# Private_CPU_DDR4.net
KiCad netlist of a schematic drawn in Altium Designer
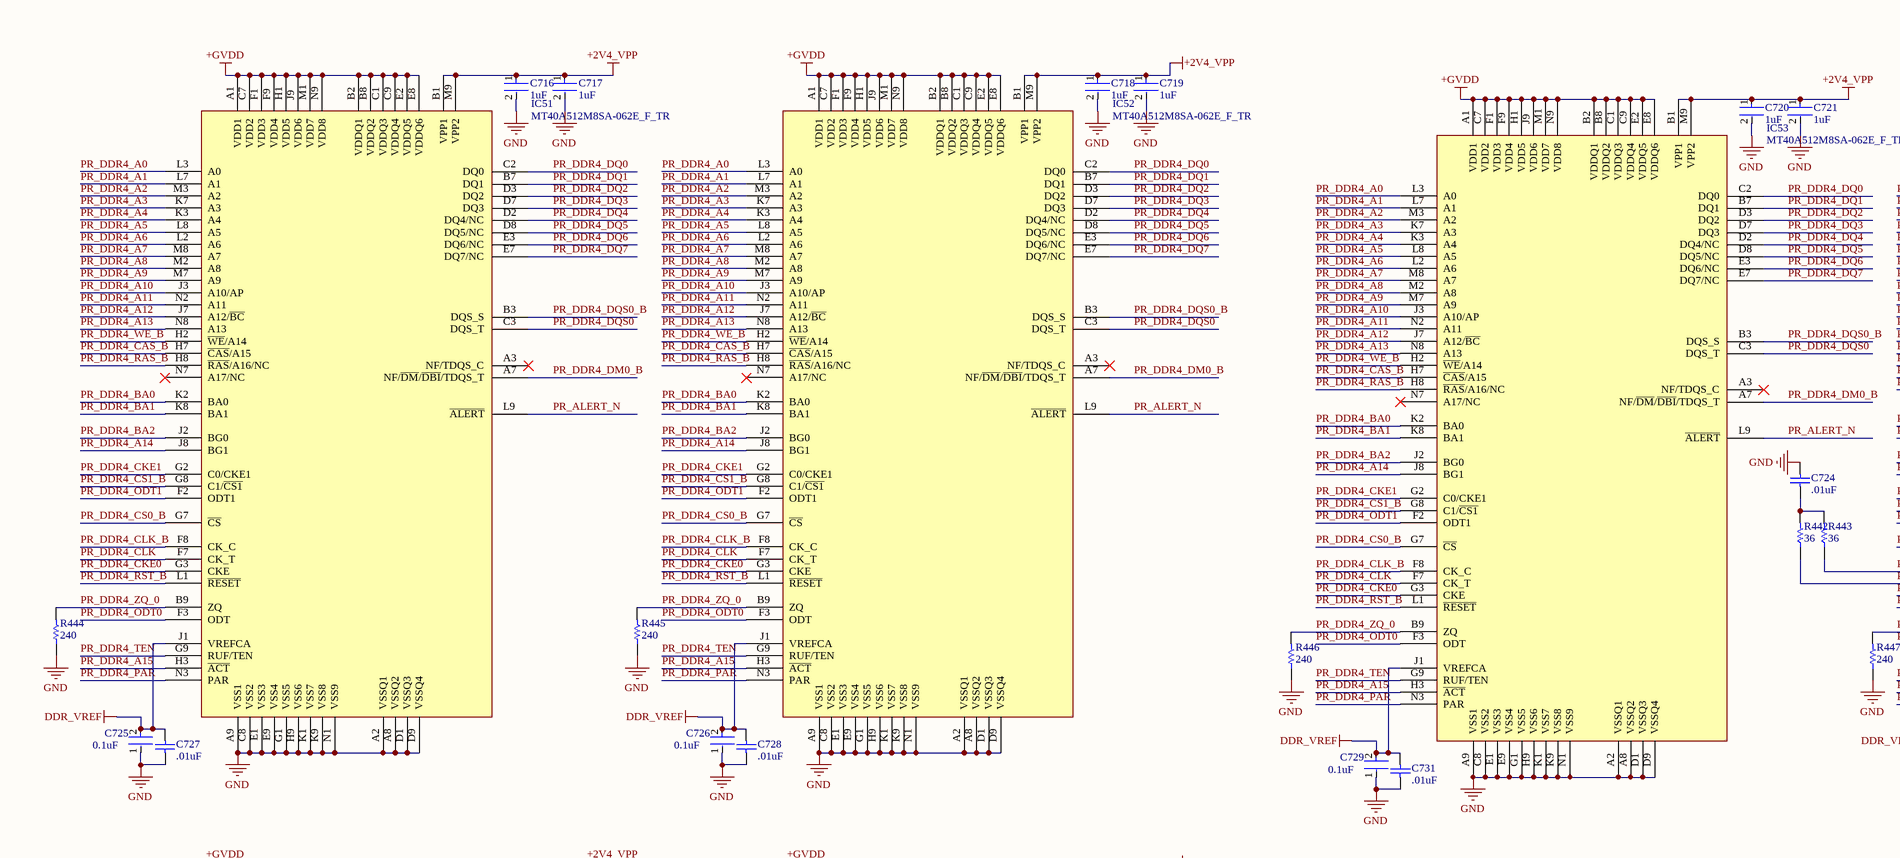
[diagram p0: Private_CPU_DDR4.SchDoc, top left]
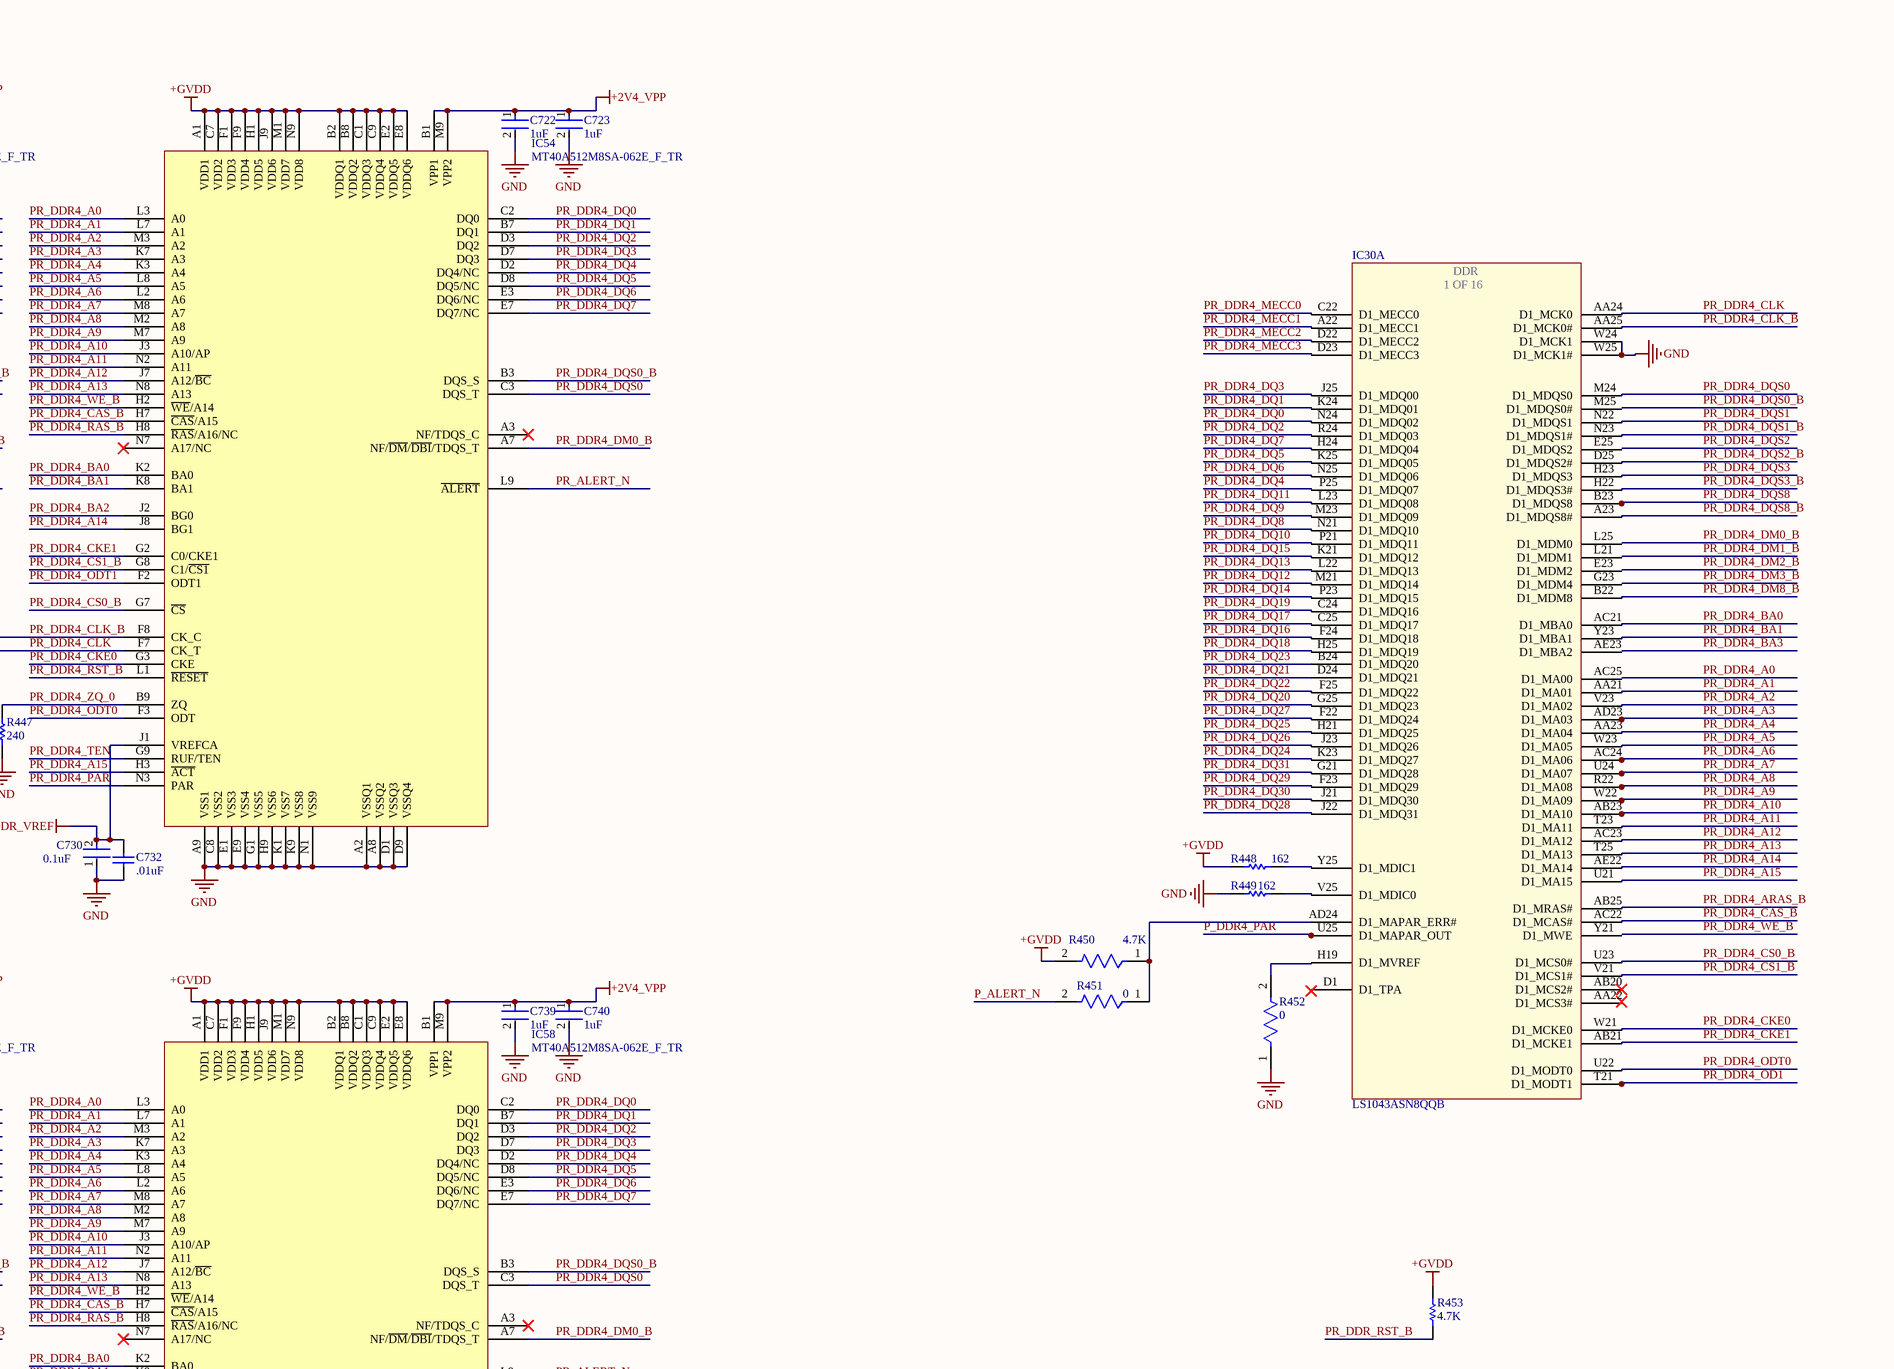
[diagram p1: Private_CPU_DDR4.SchDoc, top right]
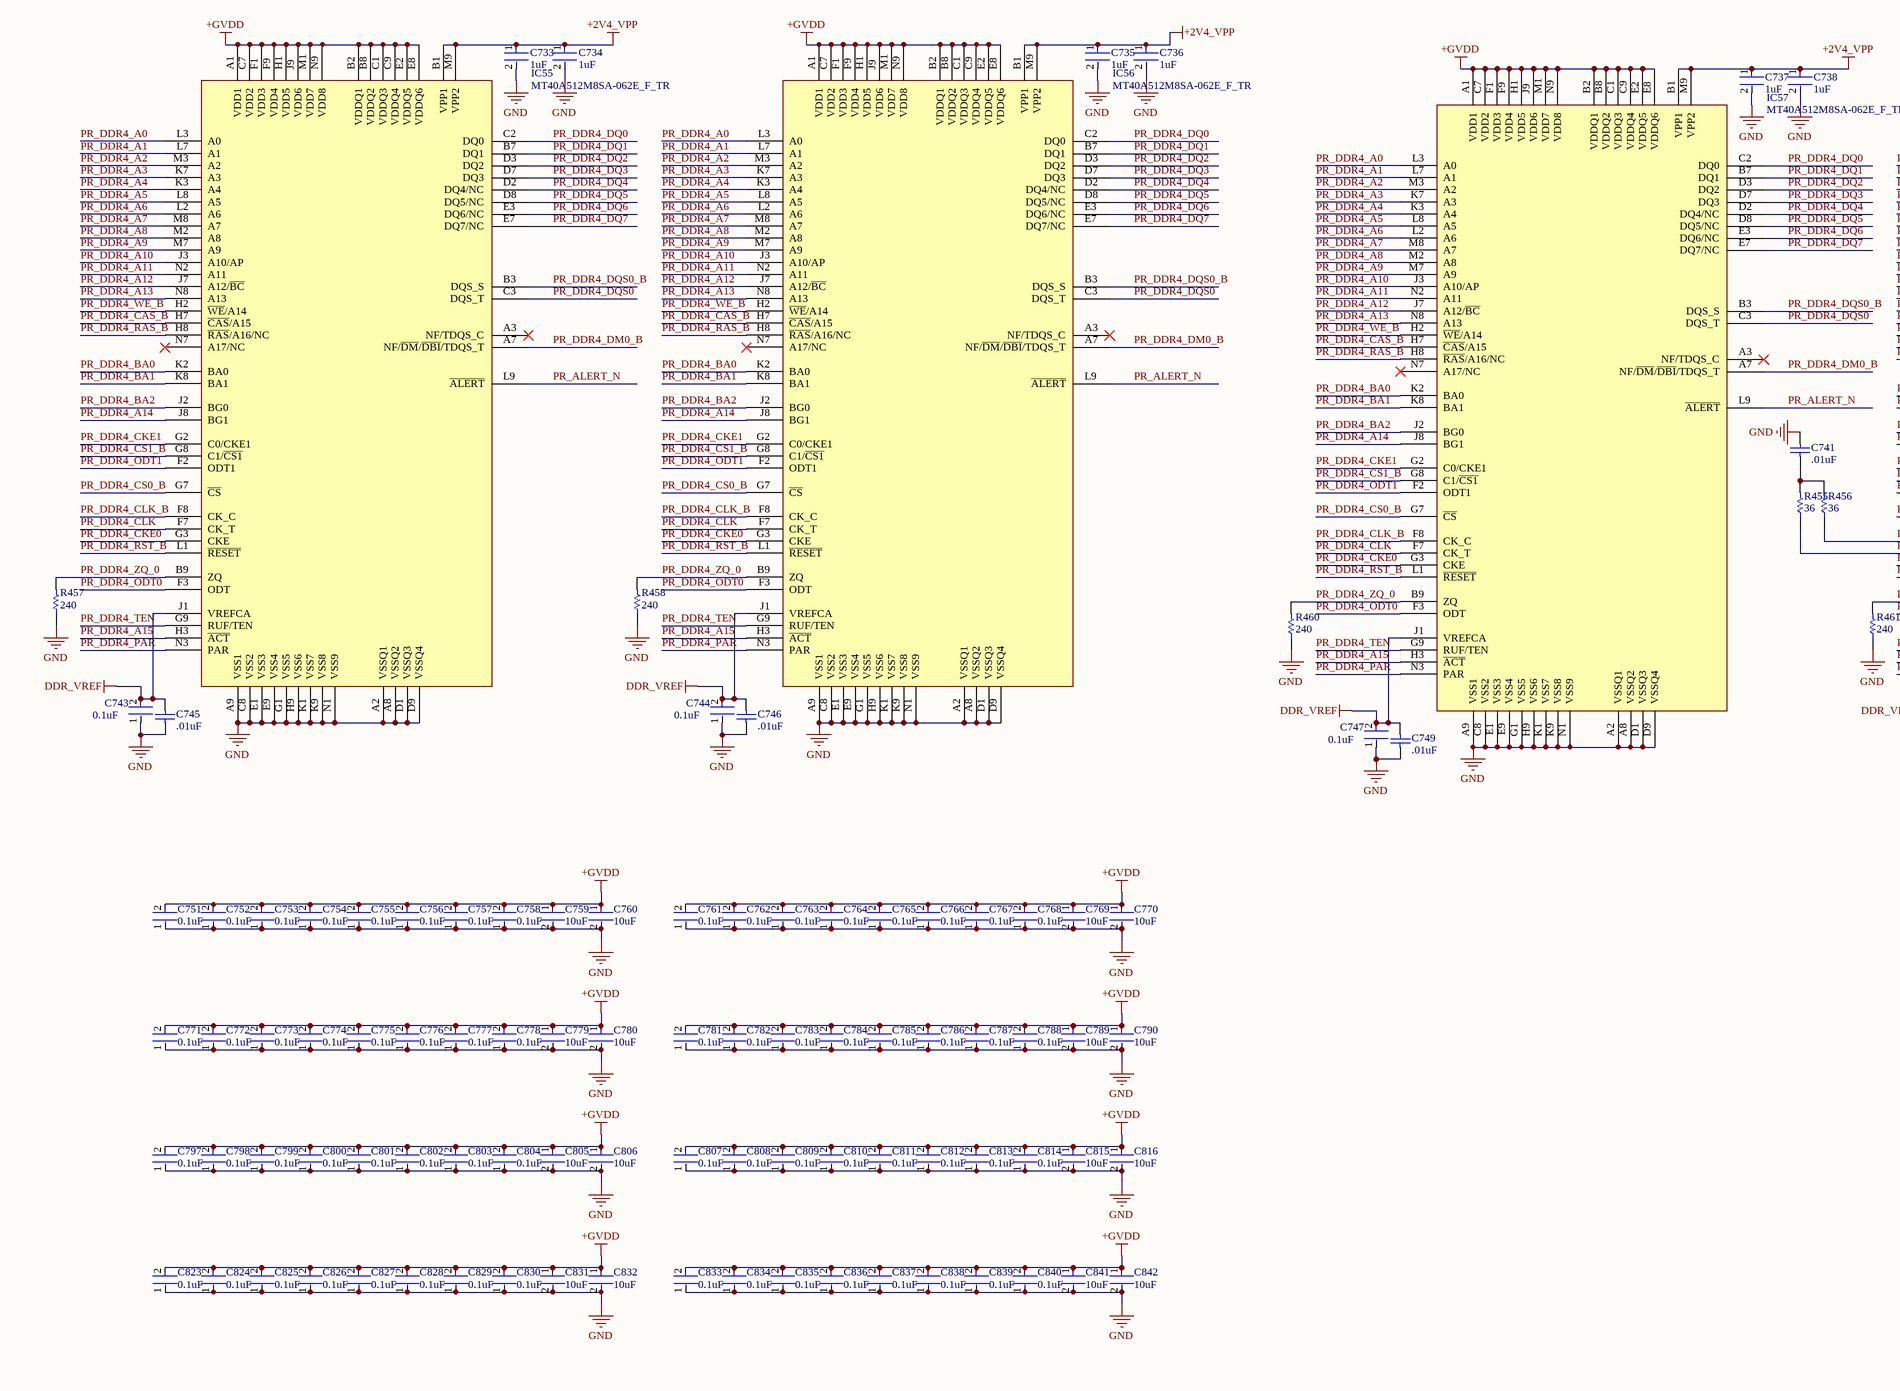
[diagram p2: Private_CPU_DDR4.SchDoc, bottom left]
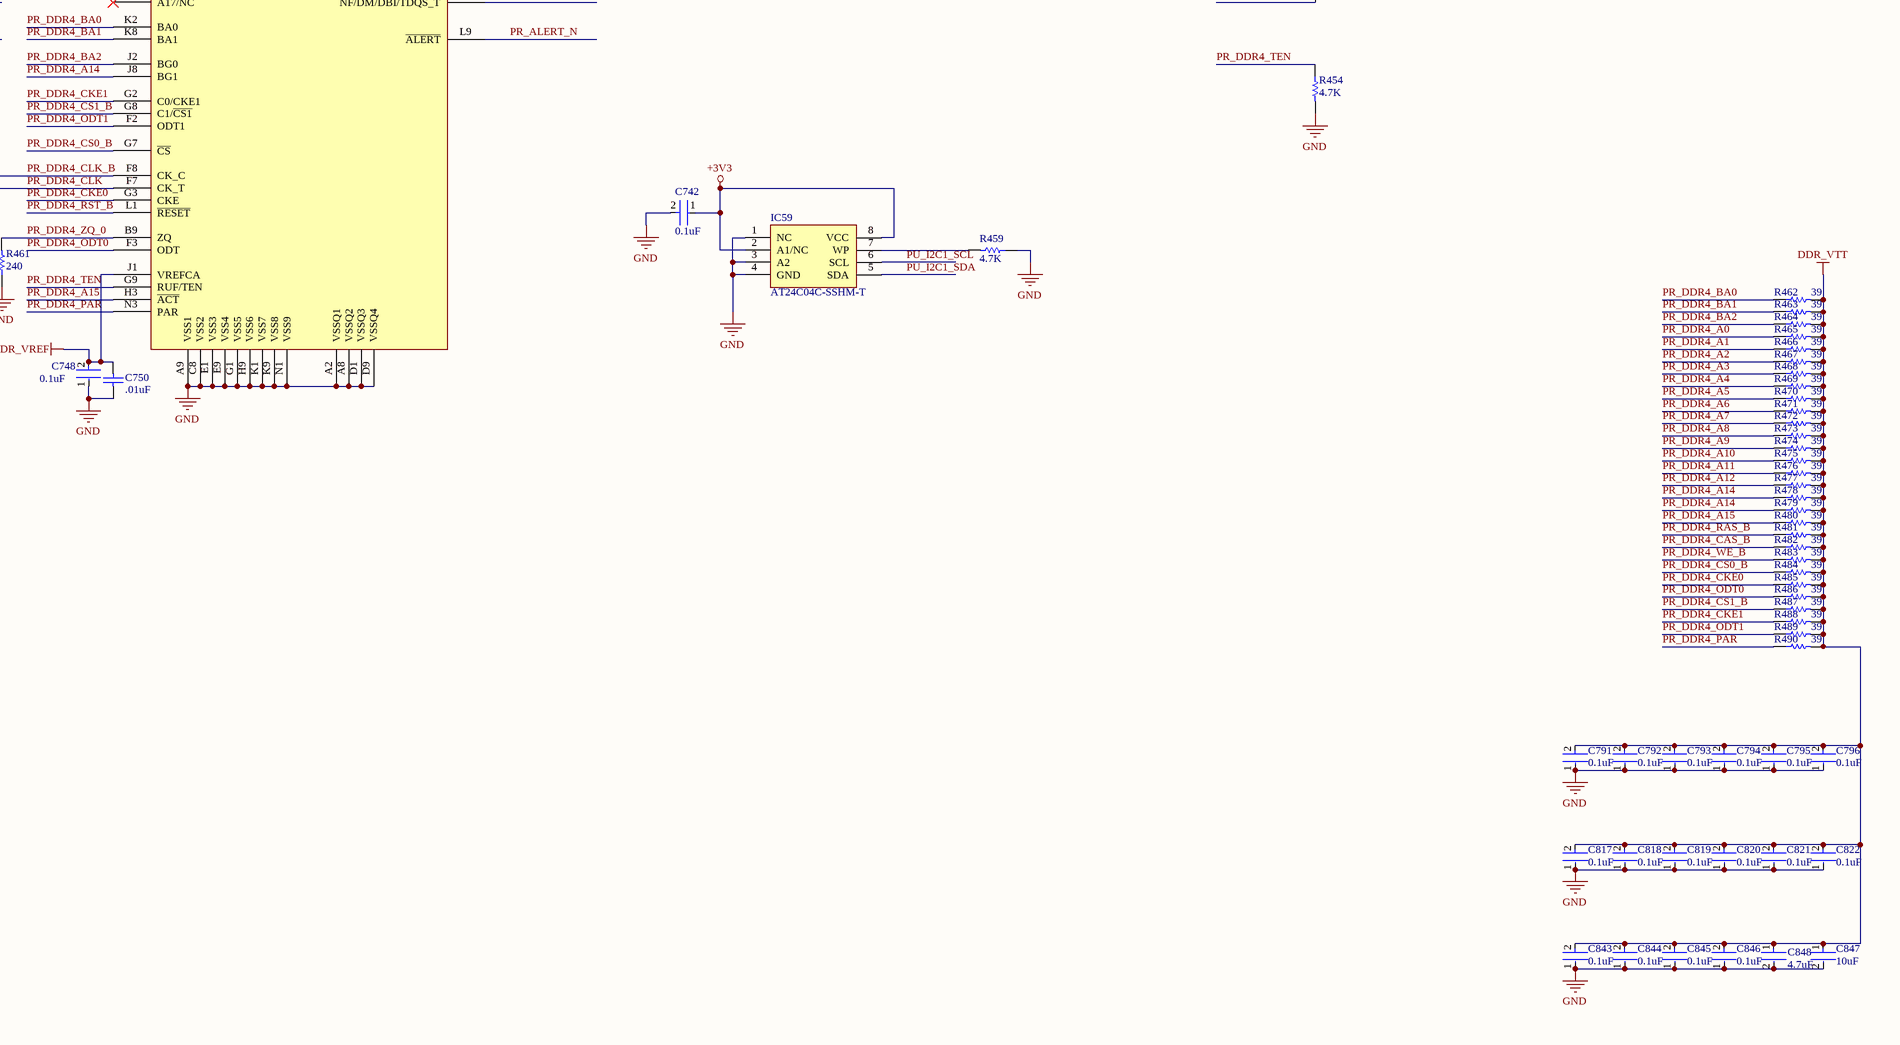
[diagram p3: Private_CPU_DDR4.SchDoc, bottom right]

(export (version "E")
  (design (tool "Eeschema 10.0.6"))
  (components
    (comp (ref "C716")
      (value "1uF")
      (footprint "FP-GRM15-0_1-MFG")
      (description "CAP CER 1UF 10V X5R 0402")
      (fields
        (field (name "OCTOPART") "https://octopart.com/grm155r61a105ke15d-murata-197442")
        (field (name "MANUFACTURER PART NUMBER") "GRM155R61A105KE15D")
      )
      (libsource (lib "Altium Content Vault") (part "02cd4be3c70576c341d710602a673aa"))
    )
    (comp (ref "C717")
      (value "1uF")
      (footprint "FP-GRM15-0_1-MFG")
      (description "CAP CER 1UF 10V X5R 0402")
      (fields
        (field (name "OCTOPART") "https://octopart.com/grm155r61a105ke15d-murata-197442")
        (field (name "MANUFACTURER PART NUMBER") "GRM155R61A105KE15D")
      )
      (libsource (lib "Altium Content Vault") (part "02cd4be3c70576c341d710602a673aa"))
    )
    (comp (ref "C718")
      (value "1uF")
      (footprint "FP-GRM15-0_1-MFG")
      (description "CAP CER 1UF 10V X5R 0402")
      (fields
        (field (name "OCTOPART") "https://octopart.com/grm155r61a105ke15d-murata-197442")
        (field (name "MANUFACTURER PART NUMBER") "GRM155R61A105KE15D")
      )
      (libsource (lib "Altium Content Vault") (part "02cd4be3c70576c341d710602a673aa"))
    )
    (comp (ref "C719")
      (value "1uF")
      (footprint "FP-GRM15-0_1-MFG")
      (description "CAP CER 1UF 10V X5R 0402")
      (fields
        (field (name "OCTOPART") "https://octopart.com/grm155r61a105ke15d-murata-197442")
        (field (name "MANUFACTURER PART NUMBER") "GRM155R61A105KE15D")
      )
      (libsource (lib "Altium Content Vault") (part "02cd4be3c70576c341d710602a673aa"))
    )
    (comp (ref "C720")
      (value "1uF")
      (footprint "FP-GRM15-0_1-MFG")
      (description "CAP CER 1UF 10V X5R 0402")
      (fields
        (field (name "OCTOPART") "https://octopart.com/grm155r61a105ke15d-murata-197442")
        (field (name "MANUFACTURER PART NUMBER") "GRM155R61A105KE15D")
      )
      (libsource (lib "Altium Content Vault") (part "02cd4be3c70576c341d710602a673aa"))
    )
    (comp (ref "C721")
      (value "1uF")
      (footprint "FP-GRM15-0_1-MFG")
      (description "CAP CER 1UF 10V X5R 0402")
      (fields
        (field (name "OCTOPART") "https://octopart.com/grm155r61a105ke15d-murata-197442")
        (field (name "MANUFACTURER PART NUMBER") "GRM155R61A105KE15D")
      )
      (libsource (lib "Altium Content Vault") (part "02cd4be3c70576c341d710602a673aa"))
    )
    (comp (ref "C722")
      (value "1uF")
      (footprint "FP-GRM15-0_1-MFG")
      (description "CAP CER 1UF 10V X5R 0402")
      (fields
        (field (name "OCTOPART") "https://octopart.com/grm155r61a105ke15d-murata-197442")
        (field (name "MANUFACTURER PART NUMBER") "GRM155R61A105KE15D")
      )
      (libsource (lib "Altium Content Vault") (part "02cd4be3c70576c341d710602a673aa"))
    )
    (comp (ref "C723")
      (value "1uF")
      (footprint "FP-GRM15-0_1-MFG")
      (description "CAP CER 1UF 10V X5R 0402")
      (fields
        (field (name "OCTOPART") "https://octopart.com/grm155r61a105ke15d-murata-197442")
        (field (name "MANUFACTURER PART NUMBER") "GRM155R61A105KE15D")
      )
      (libsource (lib "Altium Content Vault") (part "02cd4be3c70576c341d710602a673aa"))
    )
    (comp (ref "C724")
      (value ".01uF")
      (footprint "CAPC1005X56X25LL10T15")
      (fields
        (field (name "MANUFACTURER") "AVX Interconnect / Elco")
        (field (name "PART NUMBER") "0402YC103JAT2A")
      )
      (libsource (lib "Altium Content Vault") (part "CAP"))
    )
    (comp (ref "C725")
      (value "0.1uF")
      (footprint "FP-GRM15-MFG")
      (description "CAP CER 0.1UF 16V X7R 0402")
      (fields (field (name "MANUFACTURER PART NUMBER") "GRM155R71C104KA88D") (field (name "TOLERANCE") "10%"))
      (libsource (lib "Altium Content Vault") (part "236180d848d6139a670b325ea6854c9"))
    )
    (comp (ref "C726")
      (value "0.1uF")
      (footprint "FP-GRM15-MFG")
      (description "CAP CER 0.1UF 16V X7R 0402")
      (fields (field (name "MANUFACTURER PART NUMBER") "GRM155R71C104KA88D") (field (name "TOLERANCE") "10%"))
      (libsource (lib "Altium Content Vault") (part "236180d848d6139a670b325ea6854c9"))
    )
    (comp (ref "C727")
      (value ".01uF")
      (footprint "CAPC1005X56X25LL10T15")
      (fields
        (field (name "MANUFACTURER") "AVX Interconnect / Elco")
        (field (name "PART NUMBER") "0402YC103JAT2A")
      )
      (libsource (lib "Altium Content Vault") (part "CAP"))
    )
    (comp (ref "C728")
      (value ".01uF")
      (footprint "CAPC1005X56X25LL10T15")
      (fields
        (field (name "MANUFACTURER") "AVX Interconnect / Elco")
        (field (name "PART NUMBER") "0402YC103JAT2A")
      )
      (libsource (lib "Altium Content Vault") (part "CAP"))
    )
    (comp (ref "C729")
      (value "0.1uF")
      (footprint "FP-GRM15-MFG")
      (description "CAP CER 0.1UF 16V X7R 0402")
      (fields (field (name "MANUFACTURER PART NUMBER") "GRM155R71C104KA88D") (field (name "TOLERANCE") "10%"))
      (libsource (lib "Altium Content Vault") (part "236180d848d6139a670b325ea6854c9"))
    )
    (comp (ref "C730")
      (value "0.1uF")
      (footprint "FP-GRM15-MFG")
      (description "CAP CER 0.1UF 16V X7R 0402")
      (fields (field (name "MANUFACTURER PART NUMBER") "GRM155R71C104KA88D") (field (name "TOLERANCE") "10%"))
      (libsource (lib "Altium Content Vault") (part "236180d848d6139a670b325ea6854c9"))
    )
    (comp (ref "C731")
      (value ".01uF")
      (footprint "CAPC1005X56X25LL10T15")
      (fields
        (field (name "MANUFACTURER") "AVX Interconnect / Elco")
        (field (name "PART NUMBER") "0402YC103JAT2A")
      )
      (libsource (lib "Altium Content Vault") (part "CAP"))
    )
    (comp (ref "C732")
      (value ".01uF")
      (footprint "CAPC1005X56X25LL10T15")
      (fields
        (field (name "MANUFACTURER") "AVX Interconnect / Elco")
        (field (name "PART NUMBER") "0402YC103JAT2A")
      )
      (libsource (lib "Altium Content Vault") (part "CAP"))
    )
    (comp (ref "C733")
      (value "1uF")
      (footprint "FP-GRM15-0_1-MFG")
      (description "CAP CER 1UF 10V X5R 0402")
      (fields
        (field (name "OCTOPART") "https://octopart.com/grm155r61a105ke15d-murata-197442")
        (field (name "MANUFACTURER PART NUMBER") "GRM155R61A105KE15D")
      )
      (libsource (lib "Altium Content Vault") (part "02cd4be3c70576c341d710602a673aa"))
    )
    (comp (ref "C734")
      (value "1uF")
      (footprint "FP-GRM15-0_1-MFG")
      (description "CAP CER 1UF 10V X5R 0402")
      (fields
        (field (name "OCTOPART") "https://octopart.com/grm155r61a105ke15d-murata-197442")
        (field (name "MANUFACTURER PART NUMBER") "GRM155R61A105KE15D")
      )
      (libsource (lib "Altium Content Vault") (part "02cd4be3c70576c341d710602a673aa"))
    )
    (comp (ref "C735")
      (value "1uF")
      (footprint "FP-GRM15-0_1-MFG")
      (description "CAP CER 1UF 10V X5R 0402")
      (fields
        (field (name "OCTOPART") "https://octopart.com/grm155r61a105ke15d-murata-197442")
        (field (name "MANUFACTURER PART NUMBER") "GRM155R61A105KE15D")
      )
      (libsource (lib "Altium Content Vault") (part "02cd4be3c70576c341d710602a673aa"))
    )
    (comp (ref "C736")
      (value "1uF")
      (footprint "FP-GRM15-0_1-MFG")
      (description "CAP CER 1UF 10V X5R 0402")
      (fields
        (field (name "OCTOPART") "https://octopart.com/grm155r61a105ke15d-murata-197442")
        (field (name "MANUFACTURER PART NUMBER") "GRM155R61A105KE15D")
      )
      (libsource (lib "Altium Content Vault") (part "02cd4be3c70576c341d710602a673aa"))
    )
    (comp (ref "C737")
      (value "1uF")
      (footprint "FP-GRM15-0_1-MFG")
      (description "CAP CER 1UF 10V X5R 0402")
      (fields
        (field (name "OCTOPART") "https://octopart.com/grm155r61a105ke15d-murata-197442")
        (field (name "MANUFACTURER PART NUMBER") "GRM155R61A105KE15D")
      )
      (libsource (lib "Altium Content Vault") (part "02cd4be3c70576c341d710602a673aa"))
    )
    (comp (ref "C738")
      (value "1uF")
      (footprint "FP-GRM15-0_1-MFG")
      (description "CAP CER 1UF 10V X5R 0402")
      (fields
        (field (name "OCTOPART") "https://octopart.com/grm155r61a105ke15d-murata-197442")
        (field (name "MANUFACTURER PART NUMBER") "GRM155R61A105KE15D")
      )
      (libsource (lib "Altium Content Vault") (part "02cd4be3c70576c341d710602a673aa"))
    )
    (comp (ref "C739")
      (value "1uF")
      (footprint "FP-GRM15-0_1-MFG")
      (description "CAP CER 1UF 10V X5R 0402")
      (fields
        (field (name "OCTOPART") "https://octopart.com/grm155r61a105ke15d-murata-197442")
        (field (name "MANUFACTURER PART NUMBER") "GRM155R61A105KE15D")
      )
      (libsource (lib "Altium Content Vault") (part "02cd4be3c70576c341d710602a673aa"))
    )
    (comp (ref "C740")
      (value "1uF")
      (footprint "FP-GRM15-0_1-MFG")
      (description "CAP CER 1UF 10V X5R 0402")
      (fields
        (field (name "OCTOPART") "https://octopart.com/grm155r61a105ke15d-murata-197442")
        (field (name "MANUFACTURER PART NUMBER") "GRM155R61A105KE15D")
      )
      (libsource (lib "Altium Content Vault") (part "02cd4be3c70576c341d710602a673aa"))
    )
    (comp (ref "C741")
      (value ".01uF")
      (footprint "CAPC1005X56X25LL10T15")
      (fields
        (field (name "MANUFACTURER") "AVX Interconnect / Elco")
        (field (name "PART NUMBER") "0402YC103JAT2A")
      )
      (libsource (lib "Altium Content Vault") (part "CAP"))
    )
    (comp (ref "C742")
      (value "0.1uF")
      (footprint "FP-GRM15-MFG")
      (description "CAP CER 0.1UF 16V X7R 0402")
      (fields (field (name "MANUFACTURER PART NUMBER") "GRM155R71C104KA88D") (field (name "TOLERANCE") "10%"))
      (libsource (lib "Altium Content Vault") (part "236180d848d6139a670b325ea6854c9"))
    )
    (comp (ref "C743")
      (value "0.1uF")
      (footprint "FP-GRM15-MFG")
      (description "CAP CER 0.1UF 16V X7R 0402")
      (fields (field (name "MANUFACTURER PART NUMBER") "GRM155R71C104KA88D") (field (name "TOLERANCE") "10%"))
      (libsource (lib "Altium Content Vault") (part "236180d848d6139a670b325ea6854c9"))
    )
    (comp (ref "C744")
      (value "0.1uF")
      (footprint "FP-GRM15-MFG")
      (description "CAP CER 0.1UF 16V X7R 0402")
      (fields (field (name "MANUFACTURER PART NUMBER") "GRM155R71C104KA88D") (field (name "TOLERANCE") "10%"))
      (libsource (lib "Altium Content Vault") (part "236180d848d6139a670b325ea6854c9"))
    )
    (comp (ref "C745")
      (value ".01uF")
      (footprint "CAPC1005X56X25LL10T15")
      (fields
        (field (name "MANUFACTURER") "AVX Interconnect / Elco")
        (field (name "PART NUMBER") "0402YC103JAT2A")
      )
      (libsource (lib "Altium Content Vault") (part "CAP"))
    )
    (comp (ref "C746")
      (value ".01uF")
      (footprint "CAPC1005X56X25LL10T15")
      (fields
        (field (name "MANUFACTURER") "AVX Interconnect / Elco")
        (field (name "PART NUMBER") "0402YC103JAT2A")
      )
      (libsource (lib "Altium Content Vault") (part "CAP"))
    )
    (comp (ref "C747")
      (value "0.1uF")
      (footprint "FP-GRM15-MFG")
      (description "CAP CER 0.1UF 16V X7R 0402")
      (fields (field (name "MANUFACTURER PART NUMBER") "GRM155R71C104KA88D") (field (name "TOLERANCE") "10%"))
      (libsource (lib "Altium Content Vault") (part "236180d848d6139a670b325ea6854c9"))
    )
    (comp (ref "C748")
      (value "0.1uF")
      (footprint "FP-GRM15-MFG")
      (description "CAP CER 0.1UF 16V X7R 0402")
      (fields (field (name "MANUFACTURER PART NUMBER") "GRM155R71C104KA88D") (field (name "TOLERANCE") "10%"))
      (libsource (lib "Altium Content Vault") (part "236180d848d6139a670b325ea6854c9"))
    )
    (comp (ref "C749")
      (value ".01uF")
      (footprint "CAPC1005X56X25LL10T15")
      (fields
        (field (name "MANUFACTURER") "AVX Interconnect / Elco")
        (field (name "PART NUMBER") "0402YC103JAT2A")
      )
      (libsource (lib "Altium Content Vault") (part "CAP"))
    )
    (comp (ref "C750")
      (value ".01uF")
      (footprint "CAPC1005X56X25LL10T15")
      (fields
        (field (name "MANUFACTURER") "AVX Interconnect / Elco")
        (field (name "PART NUMBER") "0402YC103JAT2A")
      )
      (libsource (lib "Altium Content Vault") (part "CAP"))
    )
    (comp (ref "C751")
      (value "0.1uF")
      (footprint "FP-GRM15-MFG")
      (description "CAP CER 0.1UF 16V X7R 0402")
      (fields (field (name "MANUFACTURER PART NUMBER") "GRM155R71C104KA88D") (field (name "TOLERANCE") "10%"))
      (libsource (lib "Altium Content Vault") (part "236180d848d6139a670b325ea6854c9"))
    )
    (comp (ref "C752")
      (value "0.1uF")
      (footprint "FP-GRM15-MFG")
      (description "CAP CER 0.1UF 16V X7R 0402")
      (fields (field (name "MANUFACTURER PART NUMBER") "GRM155R71C104KA88D") (field (name "TOLERANCE") "10%"))
      (libsource (lib "Altium Content Vault") (part "236180d848d6139a670b325ea6854c9"))
    )
    (comp (ref "C753")
      (value "0.1uF")
      (footprint "FP-GRM15-MFG")
      (description "CAP CER 0.1UF 16V X7R 0402")
      (fields (field (name "MANUFACTURER PART NUMBER") "GRM155R71C104KA88D") (field (name "TOLERANCE") "10%"))
      (libsource (lib "Altium Content Vault") (part "236180d848d6139a670b325ea6854c9"))
    )
    (comp (ref "C754")
      (value "0.1uF")
      (footprint "FP-GRM15-MFG")
      (description "CAP CER 0.1UF 16V X7R 0402")
      (fields (field (name "MANUFACTURER PART NUMBER") "GRM155R71C104KA88D") (field (name "TOLERANCE") "10%"))
      (libsource (lib "Altium Content Vault") (part "236180d848d6139a670b325ea6854c9"))
    )
    (comp (ref "C755")
      (value "0.1uF")
      (footprint "FP-GRM15-MFG")
      (description "CAP CER 0.1UF 16V X7R 0402")
      (fields (field (name "MANUFACTURER PART NUMBER") "GRM155R71C104KA88D") (field (name "TOLERANCE") "10%"))
      (libsource (lib "Altium Content Vault") (part "236180d848d6139a670b325ea6854c9"))
    )
    (comp (ref "C756")
      (value "0.1uF")
      (footprint "FP-GRM15-MFG")
      (description "CAP CER 0.1UF 16V X7R 0402")
      (fields (field (name "MANUFACTURER PART NUMBER") "GRM155R71C104KA88D") (field (name "TOLERANCE") "10%"))
      (libsource (lib "Altium Content Vault") (part "236180d848d6139a670b325ea6854c9"))
    )
    (comp (ref "C757")
      (value "0.1uF")
      (footprint "FP-GRM15-MFG")
      (description "CAP CER 0.1UF 16V X7R 0402")
      (fields (field (name "MANUFACTURER PART NUMBER") "GRM155R71C104KA88D") (field (name "TOLERANCE") "10%"))
      (libsource (lib "Altium Content Vault") (part "236180d848d6139a670b325ea6854c9"))
    )
    (comp (ref "C758")
      (value "0.1uF")
      (footprint "FP-GRM15-MFG")
      (description "CAP CER 0.1UF 16V X7R 0402")
      (fields (field (name "MANUFACTURER PART NUMBER") "GRM155R71C104KA88D") (field (name "TOLERANCE") "10%"))
      (libsource (lib "Altium Content Vault") (part "236180d848d6139a670b325ea6854c9"))
    )
    (comp (ref "C759")
      (value "10uF")
      (footprint "FP-GRM21B-0_1-IPC_C")
      (description "Chip Multilayer Ceramic Capacitors for General Purpose, 0805, 10uF, X5R, 15%, 10%, 16V")
      (fields (field (name "TOLERANCE") "10%") (field (name "VOLTAGE") "16V"))
      (libsource (lib "Altium Content Vault") (part "b4654b650e69147ec39a6b967a45e02"))
    )
    (comp (ref "C760")
      (value "10uF")
      (footprint "FP-GRM21B-0_1-IPC_C")
      (description "Chip Multilayer Ceramic Capacitors for General Purpose, 0805, 10uF, X5R, 15%, 10%, 16V")
      (fields (field (name "TOLERANCE") "10%") (field (name "VOLTAGE") "16V"))
      (libsource (lib "Altium Content Vault") (part "b4654b650e69147ec39a6b967a45e02"))
    )
    (comp (ref "C761")
      (value "0.1uF")
      (footprint "FP-GRM15-MFG")
      (description "CAP CER 0.1UF 16V X7R 0402")
      (fields (field (name "MANUFACTURER PART NUMBER") "GRM155R71C104KA88D") (field (name "TOLERANCE") "10%"))
      (libsource (lib "Altium Content Vault") (part "236180d848d6139a670b325ea6854c9"))
    )
    (comp (ref "C762")
      (value "0.1uF")
      (footprint "FP-GRM15-MFG")
      (description "CAP CER 0.1UF 16V X7R 0402")
      (fields (field (name "MANUFACTURER PART NUMBER") "GRM155R71C104KA88D") (field (name "TOLERANCE") "10%"))
      (libsource (lib "Altium Content Vault") (part "236180d848d6139a670b325ea6854c9"))
    )
    (comp (ref "C763")
      (value "0.1uF")
      (footprint "FP-GRM15-MFG")
      (description "CAP CER 0.1UF 16V X7R 0402")
      (fields (field (name "MANUFACTURER PART NUMBER") "GRM155R71C104KA88D") (field (name "TOLERANCE") "10%"))
      (libsource (lib "Altium Content Vault") (part "236180d848d6139a670b325ea6854c9"))
    )
    (comp (ref "C764")
      (value "0.1uF")
      (footprint "FP-GRM15-MFG")
      (description "CAP CER 0.1UF 16V X7R 0402")
      (fields (field (name "MANUFACTURER PART NUMBER") "GRM155R71C104KA88D") (field (name "TOLERANCE") "10%"))
      (libsource (lib "Altium Content Vault") (part "236180d848d6139a670b325ea6854c9"))
    )
    (comp (ref "C765")
      (value "0.1uF")
      (footprint "FP-GRM15-MFG")
      (description "CAP CER 0.1UF 16V X7R 0402")
      (fields (field (name "MANUFACTURER PART NUMBER") "GRM155R71C104KA88D") (field (name "TOLERANCE") "10%"))
      (libsource (lib "Altium Content Vault") (part "236180d848d6139a670b325ea6854c9"))
    )
    (comp (ref "C766")
      (value "0.1uF")
      (footprint "FP-GRM15-MFG")
      (description "CAP CER 0.1UF 16V X7R 0402")
      (fields (field (name "MANUFACTURER PART NUMBER") "GRM155R71C104KA88D") (field (name "TOLERANCE") "10%"))
      (libsource (lib "Altium Content Vault") (part "236180d848d6139a670b325ea6854c9"))
    )
    (comp (ref "C767")
      (value "0.1uF")
      (footprint "FP-GRM15-MFG")
      (description "CAP CER 0.1UF 16V X7R 0402")
      (fields (field (name "MANUFACTURER PART NUMBER") "GRM155R71C104KA88D") (field (name "TOLERANCE") "10%"))
      (libsource (lib "Altium Content Vault") (part "236180d848d6139a670b325ea6854c9"))
    )
    (comp (ref "C768")
      (value "0.1uF")
      (footprint "FP-GRM15-MFG")
      (description "CAP CER 0.1UF 16V X7R 0402")
      (fields (field (name "MANUFACTURER PART NUMBER") "GRM155R71C104KA88D") (field (name "TOLERANCE") "10%"))
      (libsource (lib "Altium Content Vault") (part "236180d848d6139a670b325ea6854c9"))
    )
    (comp (ref "C769")
      (value "10uF")
      (footprint "FP-GRM21B-0_1-IPC_C")
      (description "Chip Multilayer Ceramic Capacitors for General Purpose, 0805, 10uF, X5R, 15%, 10%, 16V")
      (fields (field (name "TOLERANCE") "10%") (field (name "VOLTAGE") "16V"))
      (libsource (lib "Altium Content Vault") (part "b4654b650e69147ec39a6b967a45e02"))
    )
    (comp (ref "C770")
      (value "10uF")
      (footprint "FP-GRM21B-0_1-IPC_C")
      (description "Chip Multilayer Ceramic Capacitors for General Purpose, 0805, 10uF, X5R, 15%, 10%, 16V")
      (fields (field (name "TOLERANCE") "10%") (field (name "VOLTAGE") "16V"))
      (libsource (lib "Altium Content Vault") (part "b4654b650e69147ec39a6b967a45e02"))
    )
    (comp (ref "C771")
      (value "0.1uF")
      (footprint "FP-GRM15-MFG")
      (description "CAP CER 0.1UF 16V X7R 0402")
      (fields (field (name "MANUFACTURER PART NUMBER") "GRM155R71C104KA88D") (field (name "TOLERANCE") "10%"))
      (libsource (lib "Altium Content Vault") (part "236180d848d6139a670b325ea6854c9"))
    )
    (comp (ref "C772")
      (value "0.1uF")
      (footprint "FP-GRM15-MFG")
      (description "CAP CER 0.1UF 16V X7R 0402")
      (fields (field (name "MANUFACTURER PART NUMBER") "GRM155R71C104KA88D") (field (name "TOLERANCE") "10%"))
      (libsource (lib "Altium Content Vault") (part "236180d848d6139a670b325ea6854c9"))
    )
    (comp (ref "C773")
      (value "0.1uF")
      (footprint "FP-GRM15-MFG")
      (description "CAP CER 0.1UF 16V X7R 0402")
      (fields (field (name "MANUFACTURER PART NUMBER") "GRM155R71C104KA88D") (field (name "TOLERANCE") "10%"))
      (libsource (lib "Altium Content Vault") (part "236180d848d6139a670b325ea6854c9"))
    )
    (comp (ref "C774")
      (value "0.1uF")
      (footprint "FP-GRM15-MFG")
      (description "CAP CER 0.1UF 16V X7R 0402")
      (fields (field (name "MANUFACTURER PART NUMBER") "GRM155R71C104KA88D") (field (name "TOLERANCE") "10%"))
      (libsource (lib "Altium Content Vault") (part "236180d848d6139a670b325ea6854c9"))
    )
    (comp (ref "C775")
      (value "0.1uF")
      (footprint "FP-GRM15-MFG")
      (description "CAP CER 0.1UF 16V X7R 0402")
      (fields (field (name "MANUFACTURER PART NUMBER") "GRM155R71C104KA88D") (field (name "TOLERANCE") "10%"))
      (libsource (lib "Altium Content Vault") (part "236180d848d6139a670b325ea6854c9"))
    )
    (comp (ref "C776")
      (value "0.1uF")
      (footprint "FP-GRM15-MFG")
      (description "CAP CER 0.1UF 16V X7R 0402")
      (fields (field (name "MANUFACTURER PART NUMBER") "GRM155R71C104KA88D") (field (name "TOLERANCE") "10%"))
      (libsource (lib "Altium Content Vault") (part "236180d848d6139a670b325ea6854c9"))
    )
    (comp (ref "C777")
      (value "0.1uF")
      (footprint "FP-GRM15-MFG")
      (description "CAP CER 0.1UF 16V X7R 0402")
      (fields (field (name "MANUFACTURER PART NUMBER") "GRM155R71C104KA88D") (field (name "TOLERANCE") "10%"))
      (libsource (lib "Altium Content Vault") (part "236180d848d6139a670b325ea6854c9"))
    )
    (comp (ref "C778")
      (value "0.1uF")
      (footprint "FP-GRM15-MFG")
      (description "CAP CER 0.1UF 16V X7R 0402")
      (fields (field (name "MANUFACTURER PART NUMBER") "GRM155R71C104KA88D") (field (name "TOLERANCE") "10%"))
      (libsource (lib "Altium Content Vault") (part "236180d848d6139a670b325ea6854c9"))
    )
    (comp (ref "C779")
      (value "10uF")
      (footprint "FP-GRM21B-0_1-IPC_C")
      (description "Chip Multilayer Ceramic Capacitors for General Purpose, 0805, 10uF, X5R, 15%, 10%, 16V")
      (fields (field (name "TOLERANCE") "10%") (field (name "VOLTAGE") "16V"))
      (libsource (lib "Altium Content Vault") (part "b4654b650e69147ec39a6b967a45e02"))
    )
    (comp (ref "C780")
      (value "10uF")
      (footprint "FP-GRM21B-0_1-IPC_C")
      (description "Chip Multilayer Ceramic Capacitors for General Purpose, 0805, 10uF, X5R, 15%, 10%, 16V")
      (fields (field (name "TOLERANCE") "10%") (field (name "VOLTAGE") "16V"))
      (libsource (lib "Altium Content Vault") (part "b4654b650e69147ec39a6b967a45e02"))
    )
    (comp (ref "C781")
      (value "0.1uF")
      (footprint "FP-GRM15-MFG")
      (description "CAP CER 0.1UF 16V X7R 0402")
      (fields (field (name "MANUFACTURER PART NUMBER") "GRM155R71C104KA88D") (field (name "TOLERANCE") "10%"))
      (libsource (lib "Altium Content Vault") (part "236180d848d6139a670b325ea6854c9"))
    )
    (comp (ref "C782")
      (value "0.1uF")
      (footprint "FP-GRM15-MFG")
      (description "CAP CER 0.1UF 16V X7R 0402")
      (fields (field (name "MANUFACTURER PART NUMBER") "GRM155R71C104KA88D") (field (name "TOLERANCE") "10%"))
      (libsource (lib "Altium Content Vault") (part "236180d848d6139a670b325ea6854c9"))
    )
    (comp (ref "C783")
      (value "0.1uF")
      (footprint "FP-GRM15-MFG")
      (description "CAP CER 0.1UF 16V X7R 0402")
      (fields (field (name "MANUFACTURER PART NUMBER") "GRM155R71C104KA88D") (field (name "TOLERANCE") "10%"))
      (libsource (lib "Altium Content Vault") (part "236180d848d6139a670b325ea6854c9"))
    )
    (comp (ref "C784")
      (value "0.1uF")
      (footprint "FP-GRM15-MFG")
      (description "CAP CER 0.1UF 16V X7R 0402")
      (fields (field (name "MANUFACTURER PART NUMBER") "GRM155R71C104KA88D") (field (name "TOLERANCE") "10%"))
      (libsource (lib "Altium Content Vault") (part "236180d848d6139a670b325ea6854c9"))
    )
    (comp (ref "C785")
      (value "0.1uF")
      (footprint "FP-GRM15-MFG")
      (description "CAP CER 0.1UF 16V X7R 0402")
      (fields (field (name "MANUFACTURER PART NUMBER") "GRM155R71C104KA88D") (field (name "TOLERANCE") "10%"))
      (libsource (lib "Altium Content Vault") (part "236180d848d6139a670b325ea6854c9"))
    )
    (comp (ref "C786")
      (value "0.1uF")
      (footprint "FP-GRM15-MFG")
      (description "CAP CER 0.1UF 16V X7R 0402")
      (fields (field (name "MANUFACTURER PART NUMBER") "GRM155R71C104KA88D") (field (name "TOLERANCE") "10%"))
      (libsource (lib "Altium Content Vault") (part "236180d848d6139a670b325ea6854c9"))
    )
    (comp (ref "C787")
      (value "0.1uF")
      (footprint "FP-GRM15-MFG")
      (description "CAP CER 0.1UF 16V X7R 0402")
      (fields (field (name "MANUFACTURER PART NUMBER") "GRM155R71C104KA88D") (field (name "TOLERANCE") "10%"))
      (libsource (lib "Altium Content Vault") (part "236180d848d6139a670b325ea6854c9"))
    )
    (comp (ref "C788")
      (value "0.1uF")
      (footprint "FP-GRM15-MFG")
      (description "CAP CER 0.1UF 16V X7R 0402")
      (fields (field (name "MANUFACTURER PART NUMBER") "GRM155R71C104KA88D") (field (name "TOLERANCE") "10%"))
      (libsource (lib "Altium Content Vault") (part "236180d848d6139a670b325ea6854c9"))
    )
    (comp (ref "C789")
      (value "10uF")
      (footprint "FP-GRM21B-0_1-IPC_C")
      (description "Chip Multilayer Ceramic Capacitors for General Purpose, 0805, 10uF, X5R, 15%, 10%, 16V")
      (fields (field (name "TOLERANCE") "10%") (field (name "VOLTAGE") "16V"))
      (libsource (lib "Altium Content Vault") (part "b4654b650e69147ec39a6b967a45e02"))
    )
    (comp (ref "C790")
      (value "10uF")
      (footprint "FP-GRM21B-0_1-IPC_C")
      (description "Chip Multilayer Ceramic Capacitors for General Purpose, 0805, 10uF, X5R, 15%, 10%, 16V")
      (fields (field (name "TOLERANCE") "10%") (field (name "VOLTAGE") "16V"))
      (libsource (lib "Altium Content Vault") (part "b4654b650e69147ec39a6b967a45e02"))
    )
    (comp (ref "C791")
      (value "0.1uF")
      (footprint "FP-GRM15-MFG")
      (description "CAP CER 0.1UF 16V X7R 0402")
      (fields (field (name "MANUFACTURER PART NUMBER") "GRM155R71C104KA88D") (field (name "TOLERANCE") "10%"))
      (libsource (lib "Altium Content Vault") (part "236180d848d6139a670b325ea6854c9"))
    )
    (comp (ref "C792")
      (value "0.1uF")
      (footprint "FP-GRM15-MFG")
      (description "CAP CER 0.1UF 16V X7R 0402")
      (fields (field (name "MANUFACTURER PART NUMBER") "GRM155R71C104KA88D") (field (name "TOLERANCE") "10%"))
      (libsource (lib "Altium Content Vault") (part "236180d848d6139a670b325ea6854c9"))
    )
    (comp (ref "C793")
      (value "0.1uF")
      (footprint "FP-GRM15-MFG")
      (description "CAP CER 0.1UF 16V X7R 0402")
      (fields (field (name "MANUFACTURER PART NUMBER") "GRM155R71C104KA88D") (field (name "TOLERANCE") "10%"))
      (libsource (lib "Altium Content Vault") (part "236180d848d6139a670b325ea6854c9"))
    )
    (comp (ref "C794")
      (value "0.1uF")
      (footprint "FP-GRM15-MFG")
      (description "CAP CER 0.1UF 16V X7R 0402")
      (fields (field (name "MANUFACTURER PART NUMBER") "GRM155R71C104KA88D") (field (name "TOLERANCE") "10%"))
      (libsource (lib "Altium Content Vault") (part "236180d848d6139a670b325ea6854c9"))
    )
    (comp (ref "C795")
      (value "0.1uF")
      (footprint "FP-GRM15-MFG")
      (description "CAP CER 0.1UF 16V X7R 0402")
      (fields (field (name "MANUFACTURER PART NUMBER") "GRM155R71C104KA88D") (field (name "TOLERANCE") "10%"))
      (libsource (lib "Altium Content Vault") (part "236180d848d6139a670b325ea6854c9"))
    )
    (comp (ref "C796")
      (value "0.1uF")
      (footprint "FP-GRM15-MFG")
      (description "CAP CER 0.1UF 16V X7R 0402")
      (fields (field (name "MANUFACTURER PART NUMBER") "GRM155R71C104KA88D") (field (name "TOLERANCE") "10%"))
      (libsource (lib "Altium Content Vault") (part "236180d848d6139a670b325ea6854c9"))
    )
    (comp (ref "C797")
      (value "0.1uF")
      (footprint "FP-GRM15-MFG")
      (description "CAP CER 0.1UF 16V X7R 0402")
      (fields (field (name "MANUFACTURER PART NUMBER") "GRM155R71C104KA88D") (field (name "TOLERANCE") "10%"))
      (libsource (lib "Altium Content Vault") (part "236180d848d6139a670b325ea6854c9"))
    )
    (comp (ref "C798")
      (value "0.1uF")
      (footprint "FP-GRM15-MFG")
      (description "CAP CER 0.1UF 16V X7R 0402")
      (fields (field (name "MANUFACTURER PART NUMBER") "GRM155R71C104KA88D") (field (name "TOLERANCE") "10%"))
      (libsource (lib "Altium Content Vault") (part "236180d848d6139a670b325ea6854c9"))
    )
    (comp (ref "C799")
      (value "0.1uF")
      (footprint "FP-GRM15-MFG")
      (description "CAP CER 0.1UF 16V X7R 0402")
      (fields (field (name "MANUFACTURER PART NUMBER") "GRM155R71C104KA88D") (field (name "TOLERANCE") "10%"))
      (libsource (lib "Altium Content Vault") (part "236180d848d6139a670b325ea6854c9"))
    )
    (comp (ref "C800")
      (value "0.1uF")
      (footprint "FP-GRM15-MFG")
      (description "CAP CER 0.1UF 16V X7R 0402")
      (fields (field (name "MANUFACTURER PART NUMBER") "GRM155R71C104KA88D") (field (name "TOLERANCE") "10%"))
      (libsource (lib "Altium Content Vault") (part "236180d848d6139a670b325ea6854c9"))
    )
    (comp (ref "C801")
      (value "0.1uF")
      (footprint "FP-GRM15-MFG")
      (description "CAP CER 0.1UF 16V X7R 0402")
      (fields (field (name "MANUFACTURER PART NUMBER") "GRM155R71C104KA88D") (field (name "TOLERANCE") "10%"))
      (libsource (lib "Altium Content Vault") (part "236180d848d6139a670b325ea6854c9"))
    )
    (comp (ref "C802")
      (value "0.1uF")
      (footprint "FP-GRM15-MFG")
      (description "CAP CER 0.1UF 16V X7R 0402")
      (fields (field (name "MANUFACTURER PART NUMBER") "GRM155R71C104KA88D") (field (name "TOLERANCE") "10%"))
      (libsource (lib "Altium Content Vault") (part "236180d848d6139a670b325ea6854c9"))
    )
    (comp (ref "C803")
      (value "0.1uF")
      (footprint "FP-GRM15-MFG")
      (description "CAP CER 0.1UF 16V X7R 0402")
      (fields (field (name "MANUFACTURER PART NUMBER") "GRM155R71C104KA88D") (field (name "TOLERANCE") "10%"))
      (libsource (lib "Altium Content Vault") (part "236180d848d6139a670b325ea6854c9"))
    )
    (comp (ref "C804")
      (value "0.1uF")
      (footprint "FP-GRM15-MFG")
      (description "CAP CER 0.1UF 16V X7R 0402")
      (fields (field (name "MANUFACTURER PART NUMBER") "GRM155R71C104KA88D") (field (name "TOLERANCE") "10%"))
      (libsource (lib "Altium Content Vault") (part "236180d848d6139a670b325ea6854c9"))
    )
    (comp (ref "C805")
      (value "10uF")
      (footprint "FP-GRM21B-0_1-IPC_C")
      (description "Chip Multilayer Ceramic Capacitors for General Purpose, 0805, 10uF, X5R, 15%, 10%, 16V")
      (fields (field (name "TOLERANCE") "10%") (field (name "VOLTAGE") "16V"))
      (libsource (lib "Altium Content Vault") (part "b4654b650e69147ec39a6b967a45e02"))
    )
    (comp (ref "C806")
      (value "10uF")
      (footprint "FP-GRM21B-0_1-IPC_C")
      (description "Chip Multilayer Ceramic Capacitors for General Purpose, 0805, 10uF, X5R, 15%, 10%, 16V")
      (fields (field (name "TOLERANCE") "10%") (field (name "VOLTAGE") "16V"))
      (libsource (lib "Altium Content Vault") (part "b4654b650e69147ec39a6b967a45e02"))
    )
    (comp (ref "C807")
      (value "0.1uF")
      (footprint "FP-GRM15-MFG")
      (description "CAP CER 0.1UF 16V X7R 0402")
      (fields (field (name "MANUFACTURER PART NUMBER") "GRM155R71C104KA88D") (field (name "TOLERANCE") "10%"))
      (libsource (lib "Altium Content Vault") (part "236180d848d6139a670b325ea6854c9"))
    )
    (comp (ref "C808")
      (value "0.1uF")
      (footprint "FP-GRM15-MFG")
      (description "CAP CER 0.1UF 16V X7R 0402")
      (fields (field (name "MANUFACTURER PART NUMBER") "GRM155R71C104KA88D") (field (name "TOLERANCE") "10%"))
      (libsource (lib "Altium Content Vault") (part "236180d848d6139a670b325ea6854c9"))
    )
    (comp (ref "C809")
      (value "0.1uF")
      (footprint "FP-GRM15-MFG")
      (description "CAP CER 0.1UF 16V X7R 0402")
      (fields (field (name "MANUFACTURER PART NUMBER") "GRM155R71C104KA88D") (field (name "TOLERANCE") "10%"))
      (libsource (lib "Altium Content Vault") (part "236180d848d6139a670b325ea6854c9"))
    )
    (comp (ref "C810")
      (value "0.1uF")
      (footprint "FP-GRM15-MFG")
      (description "CAP CER 0.1UF 16V X7R 0402")
      (fields (field (name "MANUFACTURER PART NUMBER") "GRM155R71C104KA88D") (field (name "TOLERANCE") "10%"))
      (libsource (lib "Altium Content Vault") (part "236180d848d6139a670b325ea6854c9"))
    )
    (comp (ref "C811")
      (value "0.1uF")
      (footprint "FP-GRM15-MFG")
      (description "CAP CER 0.1UF 16V X7R 0402")
      (fields (field (name "MANUFACTURER PART NUMBER") "GRM155R71C104KA88D") (field (name "TOLERANCE") "10%"))
      (libsource (lib "Altium Content Vault") (part "236180d848d6139a670b325ea6854c9"))
    )
    (comp (ref "C812")
      (value "0.1uF")
      (footprint "FP-GRM15-MFG")
      (description "CAP CER 0.1UF 16V X7R 0402")
      (fields (field (name "MANUFACTURER PART NUMBER") "GRM155R71C104KA88D") (field (name "TOLERANCE") "10%"))
      (libsource (lib "Altium Content Vault") (part "236180d848d6139a670b325ea6854c9"))
    )
    (comp (ref "C813")
      (value "0.1uF")
      (footprint "FP-GRM15-MFG")
      (description "CAP CER 0.1UF 16V X7R 0402")
      (fields (field (name "MANUFACTURER PART NUMBER") "GRM155R71C104KA88D") (field (name "TOLERANCE") "10%"))
      (libsource (lib "Altium Content Vault") (part "236180d848d6139a670b325ea6854c9"))
    )
    (comp (ref "C814")
      (value "0.1uF")
      (footprint "FP-GRM15-MFG")
      (description "CAP CER 0.1UF 16V X7R 0402")
      (fields (field (name "MANUFACTURER PART NUMBER") "GRM155R71C104KA88D") (field (name "TOLERANCE") "10%"))
      (libsource (lib "Altium Content Vault") (part "236180d848d6139a670b325ea6854c9"))
    )
    (comp (ref "C815")
      (value "10uF")
      (footprint "FP-GRM21B-0_1-IPC_C")
      (description "Chip Multilayer Ceramic Capacitors for General Purpose, 0805, 10uF, X5R, 15%, 10%, 16V")
      (fields (field (name "TOLERANCE") "10%") (field (name "VOLTAGE") "16V"))
      (libsource (lib "Altium Content Vault") (part "b4654b650e69147ec39a6b967a45e02"))
    )
    (comp (ref "C816")
      (value "10uF")
      (footprint "FP-GRM21B-0_1-IPC_C")
      (description "Chip Multilayer Ceramic Capacitors for General Purpose, 0805, 10uF, X5R, 15%, 10%, 16V")
      (fields (field (name "TOLERANCE") "10%") (field (name "VOLTAGE") "16V"))
      (libsource (lib "Altium Content Vault") (part "b4654b650e69147ec39a6b967a45e02"))
    )
    (comp (ref "C817")
      (value "0.1uF")
      (footprint "FP-GRM15-MFG")
      (description "CAP CER 0.1UF 16V X7R 0402")
      (fields (field (name "MANUFACTURER PART NUMBER") "GRM155R71C104KA88D") (field (name "TOLERANCE") "10%"))
      (libsource (lib "Altium Content Vault") (part "236180d848d6139a670b325ea6854c9"))
    )
    (comp (ref "C818")
      (value "0.1uF")
      (footprint "FP-GRM15-MFG")
      (description "CAP CER 0.1UF 16V X7R 0402")
      (fields (field (name "MANUFACTURER PART NUMBER") "GRM155R71C104KA88D") (field (name "TOLERANCE") "10%"))
      (libsource (lib "Altium Content Vault") (part "236180d848d6139a670b325ea6854c9"))
    )
    (comp (ref "C819")
      (value "0.1uF")
      (footprint "FP-GRM15-MFG")
      (description "CAP CER 0.1UF 16V X7R 0402")
      (fields (field (name "MANUFACTURER PART NUMBER") "GRM155R71C104KA88D") (field (name "TOLERANCE") "10%"))
      (libsource (lib "Altium Content Vault") (part "236180d848d6139a670b325ea6854c9"))
    )
    (comp (ref "C820")
      (value "0.1uF")
      (footprint "FP-GRM15-MFG")
      (description "CAP CER 0.1UF 16V X7R 0402")
      (fields (field (name "MANUFACTURER PART NUMBER") "GRM155R71C104KA88D") (field (name "TOLERANCE") "10%"))
      (libsource (lib "Altium Content Vault") (part "236180d848d6139a670b325ea6854c9"))
    )
    (comp (ref "C821")
      (value "0.1uF")
      (footprint "FP-GRM15-MFG")
      (description "CAP CER 0.1UF 16V X7R 0402")
      (fields (field (name "MANUFACTURER PART NUMBER") "GRM155R71C104KA88D") (field (name "TOLERANCE") "10%"))
      (libsource (lib "Altium Content Vault") (part "236180d848d6139a670b325ea6854c9"))
    )
    (comp (ref "C822")
      (value "0.1uF")
      (footprint "FP-GRM15-MFG")
      (description "CAP CER 0.1UF 16V X7R 0402")
      (fields (field (name "MANUFACTURER PART NUMBER") "GRM155R71C104KA88D") (field (name "TOLERANCE") "10%"))
      (libsource (lib "Altium Content Vault") (part "236180d848d6139a670b325ea6854c9"))
    )
    (comp (ref "C823")
      (value "0.1uF")
      (footprint "FP-GRM15-MFG")
      (description "CAP CER 0.1UF 16V X7R 0402")
      (fields (field (name "MANUFACTURER PART NUMBER") "GRM155R71C104KA88D") (field (name "TOLERANCE") "10%"))
      (libsource (lib "Altium Content Vault") (part "236180d848d6139a670b325ea6854c9"))
    )
    (comp (ref "C824")
      (value "0.1uF")
      (footprint "FP-GRM15-MFG")
      (description "CAP CER 0.1UF 16V X7R 0402")
      (fields (field (name "MANUFACTURER PART NUMBER") "GRM155R71C104KA88D") (field (name "TOLERANCE") "10%"))
      (libsource (lib "Altium Content Vault") (part "236180d848d6139a670b325ea6854c9"))
    )
    (comp (ref "C825")
      (value "0.1uF")
      (footprint "FP-GRM15-MFG")
      (description "CAP CER 0.1UF 16V X7R 0402")
      (fields (field (name "MANUFACTURER PART NUMBER") "GRM155R71C104KA88D") (field (name "TOLERANCE") "10%"))
      (libsource (lib "Altium Content Vault") (part "236180d848d6139a670b325ea6854c9"))
    )
    (comp (ref "C826")
      (value "0.1uF")
      (footprint "FP-GRM15-MFG")
      (description "CAP CER 0.1UF 16V X7R 0402")
      (fields (field (name "MANUFACTURER PART NUMBER") "GRM155R71C104KA88D") (field (name "TOLERANCE") "10%"))
      (libsource (lib "Altium Content Vault") (part "236180d848d6139a670b325ea6854c9"))
    )
    (comp (ref "C827")
      (value "0.1uF")
      (footprint "FP-GRM15-MFG")
      (description "CAP CER 0.1UF 16V X7R 0402")
      (fields (field (name "MANUFACTURER PART NUMBER") "GRM155R71C104KA88D") (field (name "TOLERANCE") "10%"))
      (libsource (lib "Altium Content Vault") (part "236180d848d6139a670b325ea6854c9"))
    )
    (comp (ref "C828")
      (value "0.1uF")
      (footprint "FP-GRM15-MFG")
      (description "CAP CER 0.1UF 16V X7R 0402")
      (fields (field (name "MANUFACTURER PART NUMBER") "GRM155R71C104KA88D") (field (name "TOLERANCE") "10%"))
      (libsource (lib "Altium Content Vault") (part "236180d848d6139a670b325ea6854c9"))
    )
    (comp (ref "C829")
      (value "0.1uF")
      (footprint "FP-GRM15-MFG")
      (description "CAP CER 0.1UF 16V X7R 0402")
      (fields (field (name "MANUFACTURER PART NUMBER") "GRM155R71C104KA88D") (field (name "TOLERANCE") "10%"))
      (libsource (lib "Altium Content Vault") (part "236180d848d6139a670b325ea6854c9"))
    )
    (comp (ref "C830")
      (value "0.1uF")
      (footprint "FP-GRM15-MFG")
      (description "CAP CER 0.1UF 16V X7R 0402")
      (fields (field (name "MANUFACTURER PART NUMBER") "GRM155R71C104KA88D") (field (name "TOLERANCE") "10%"))
      (libsource (lib "Altium Content Vault") (part "236180d848d6139a670b325ea6854c9"))
    )
    (comp (ref "C831")
      (value "10uF")
      (footprint "FP-GRM21B-0_1-IPC_C")
      (description "Chip Multilayer Ceramic Capacitors for General Purpose, 0805, 10uF, X5R, 15%, 10%, 16V")
      (fields (field (name "TOLERANCE") "10%") (field (name "VOLTAGE") "16V"))
      (libsource (lib "Altium Content Vault") (part "b4654b650e69147ec39a6b967a45e02"))
    )
    (comp (ref "C832")
      (value "10uF")
      (footprint "FP-GRM21B-0_1-IPC_C")
      (description "Chip Multilayer Ceramic Capacitors for General Purpose, 0805, 10uF, X5R, 15%, 10%, 16V")
      (fields (field (name "TOLERANCE") "10%") (field (name "VOLTAGE") "16V"))
      (libsource (lib "Altium Content Vault") (part "b4654b650e69147ec39a6b967a45e02"))
    )
    (comp (ref "C833")
      (value "0.1uF")
      (footprint "FP-GRM15-MFG")
      (description "CAP CER 0.1UF 16V X7R 0402")
      (fields (field (name "MANUFACTURER PART NUMBER") "GRM155R71C104KA88D") (field (name "TOLERANCE") "10%"))
      (libsource (lib "Altium Content Vault") (part "236180d848d6139a670b325ea6854c9"))
    )
    (comp (ref "C834")
      (value "0.1uF")
      (footprint "FP-GRM15-MFG")
      (description "CAP CER 0.1UF 16V X7R 0402")
      (fields (field (name "MANUFACTURER PART NUMBER") "GRM155R71C104KA88D") (field (name "TOLERANCE") "10%"))
      (libsource (lib "Altium Content Vault") (part "236180d848d6139a670b325ea6854c9"))
    )
    (comp (ref "C835")
      (value "0.1uF")
      (footprint "FP-GRM15-MFG")
      (description "CAP CER 0.1UF 16V X7R 0402")
      (fields (field (name "MANUFACTURER PART NUMBER") "GRM155R71C104KA88D") (field (name "TOLERANCE") "10%"))
      (libsource (lib "Altium Content Vault") (part "236180d848d6139a670b325ea6854c9"))
    )
    (comp (ref "C836")
      (value "0.1uF")
      (footprint "FP-GRM15-MFG")
      (description "CAP CER 0.1UF 16V X7R 0402")
      (fields (field (name "MANUFACTURER PART NUMBER") "GRM155R71C104KA88D") (field (name "TOLERANCE") "10%"))
      (libsource (lib "Altium Content Vault") (part "236180d848d6139a670b325ea6854c9"))
    )
    (comp (ref "C837")
      (value "0.1uF")
      (footprint "FP-GRM15-MFG")
      (description "CAP CER 0.1UF 16V X7R 0402")
      (fields (field (name "MANUFACTURER PART NUMBER") "GRM155R71C104KA88D") (field (name "TOLERANCE") "10%"))
      (libsource (lib "Altium Content Vault") (part "236180d848d6139a670b325ea6854c9"))
    )
    (comp (ref "C838")
      (value "0.1uF")
      (footprint "FP-GRM15-MFG")
      (description "CAP CER 0.1UF 16V X7R 0402")
      (fields (field (name "MANUFACTURER PART NUMBER") "GRM155R71C104KA88D") (field (name "TOLERANCE") "10%"))
      (libsource (lib "Altium Content Vault") (part "236180d848d6139a670b325ea6854c9"))
    )
    (comp (ref "C839")
      (value "0.1uF")
      (footprint "FP-GRM15-MFG")
      (description "CAP CER 0.1UF 16V X7R 0402")
      (fields (field (name "MANUFACTURER PART NUMBER") "GRM155R71C104KA88D") (field (name "TOLERANCE") "10%"))
      (libsource (lib "Altium Content Vault") (part "236180d848d6139a670b325ea6854c9"))
    )
    (comp (ref "C840")
      (value "0.1uF")
      (footprint "FP-GRM15-MFG")
      (description "CAP CER 0.1UF 16V X7R 0402")
      (fields (field (name "MANUFACTURER PART NUMBER") "GRM155R71C104KA88D") (field (name "TOLERANCE") "10%"))
      (libsource (lib "Altium Content Vault") (part "236180d848d6139a670b325ea6854c9"))
    )
    (comp (ref "C841")
      (value "10uF")
      (footprint "FP-GRM21B-0_1-IPC_C")
      (description "Chip Multilayer Ceramic Capacitors for General Purpose, 0805, 10uF, X5R, 15%, 10%, 16V")
      (fields (field (name "TOLERANCE") "10%") (field (name "VOLTAGE") "16V"))
      (libsource (lib "Altium Content Vault") (part "b4654b650e69147ec39a6b967a45e02"))
    )
    (comp (ref "C842")
      (value "10uF")
      (footprint "FP-GRM21B-0_1-IPC_C")
      (description "Chip Multilayer Ceramic Capacitors for General Purpose, 0805, 10uF, X5R, 15%, 10%, 16V")
      (fields (field (name "TOLERANCE") "10%") (field (name "VOLTAGE") "16V"))
      (libsource (lib "Altium Content Vault") (part "b4654b650e69147ec39a6b967a45e02"))
    )
    (comp (ref "C843")
      (value "0.1uF")
      (footprint "FP-GRM15-MFG")
      (description "CAP CER 0.1UF 16V X7R 0402")
      (fields (field (name "MANUFACTURER PART NUMBER") "GRM155R71C104KA88D") (field (name "TOLERANCE") "10%"))
      (libsource (lib "Altium Content Vault") (part "236180d848d6139a670b325ea6854c9"))
    )
    (comp (ref "C844")
      (value "0.1uF")
      (footprint "FP-GRM15-MFG")
      (description "CAP CER 0.1UF 16V X7R 0402")
      (fields (field (name "MANUFACTURER PART NUMBER") "GRM155R71C104KA88D") (field (name "TOLERANCE") "10%"))
      (libsource (lib "Altium Content Vault") (part "236180d848d6139a670b325ea6854c9"))
    )
    (comp (ref "C845")
      (value "0.1uF")
      (footprint "FP-GRM15-MFG")
      (description "CAP CER 0.1UF 16V X7R 0402")
      (fields (field (name "MANUFACTURER PART NUMBER") "GRM155R71C104KA88D") (field (name "TOLERANCE") "10%"))
      (libsource (lib "Altium Content Vault") (part "236180d848d6139a670b325ea6854c9"))
    )
    (comp (ref "C846")
      (value "0.1uF")
      (footprint "FP-GRM15-MFG")
      (description "CAP CER 0.1UF 16V X7R 0402")
      (fields (field (name "MANUFACTURER PART NUMBER") "GRM155R71C104KA88D") (field (name "TOLERANCE") "10%"))
      (libsource (lib "Altium Content Vault") (part "236180d848d6139a670b325ea6854c9"))
    )
    (comp (ref "C847")
      (value "10uF")
      (footprint "FP-GRM21B-0_1-IPC_C")
      (description "Chip Multilayer Ceramic Capacitors for General Purpose, 0805, 10uF, X5R, 15%, 10%, 16V")
      (fields (field (name "TOLERANCE") "10%") (field (name "VOLTAGE") "16V"))
      (libsource (lib "Altium Content Vault") (part "b4654b650e69147ec39a6b967a45e02"))
    )
    (comp (ref "C848")
      (value "4.7uF")
      (footprint "FP-GRM155-0_1-IPC_B")
      (description "Chip Multilayer Ceramic Capacitors for General Purpose, 0402, 4.7uF, X5R, 15%, 20%, 6.3V")
      (fields (field (name "VOLTAGE") "6.3V") (field (name "TOLERANCE") "20%"))
      (libsource (lib "Altium Content Vault") (part "11868f565c42a9108669ba33697ecf6"))
    )
    (comp (ref "IC30")
      (value "LS1043ASN8QQB")
      (footprint "SamacSys:BGA780C80P28X28_2300X2300X261")
      (description "Integrated Circuit")
      (fields (field (name "MOUSER PART NUMBER") "771-LS1043ASN8QQB"))
      (libsource (lib "SamacSys") (part "LS1043ASN8QQB"))
    )
    (comp (ref "IC51")
      (value "MT40A512M8SA-062E_F_TR")
      (footprint "SamacSys:BGA78C80P9X13_750X1100X120")
      (description "Integrated Circuit")
      (fields
        (field (name "MANUFACTURER_PART_NUMBER") "MT40A512M8SA-062E:F TR")
        (field (name "MOUSER PART NUMBER") "340-402508-REEL")
      )
      (libsource (lib "SamacSys") (part "MT40A512M8SA-062E_F_TR"))
    )
    (comp (ref "IC52")
      (value "MT40A512M8SA-062E_F_TR")
      (footprint "SamacSys:BGA78C80P9X13_750X1100X120")
      (description "Integrated Circuit")
      (fields
        (field (name "MANUFACTURER_PART_NUMBER") "MT40A512M8SA-062E:F TR")
        (field (name "MOUSER PART NUMBER") "340-402508-REEL")
      )
      (libsource (lib "SamacSys") (part "MT40A512M8SA-062E_F_TR"))
    )
    (comp (ref "IC53")
      (value "MT40A512M8SA-062E_F_TR")
      (footprint "SamacSys:BGA78C80P9X13_750X1100X120")
      (description "Integrated Circuit")
      (fields
        (field (name "MANUFACTURER_PART_NUMBER") "MT40A512M8SA-062E:F TR")
        (field (name "MOUSER PART NUMBER") "340-402508-REEL")
      )
      (libsource (lib "SamacSys") (part "MT40A512M8SA-062E_F_TR"))
    )
    (comp (ref "IC54")
      (value "MT40A512M8SA-062E_F_TR")
      (footprint "SamacSys:BGA78C80P9X13_750X1100X120")
      (description "Integrated Circuit")
      (fields
        (field (name "MANUFACTURER_PART_NUMBER") "MT40A512M8SA-062E:F TR")
        (field (name "MOUSER PART NUMBER") "340-402508-REEL")
      )
      (libsource (lib "SamacSys") (part "MT40A512M8SA-062E_F_TR"))
    )
    (comp (ref "IC55")
      (value "MT40A512M8SA-062E_F_TR")
      (footprint "SamacSys:BGA78C80P9X13_750X1100X120")
      (description "Integrated Circuit")
      (fields
        (field (name "MANUFACTURER_PART_NUMBER") "MT40A512M8SA-062E:F TR")
        (field (name "MOUSER PART NUMBER") "340-402508-REEL")
      )
      (libsource (lib "SamacSys") (part "MT40A512M8SA-062E_F_TR"))
    )
    (comp (ref "IC56")
      (value "MT40A512M8SA-062E_F_TR")
      (footprint "SamacSys:BGA78C80P9X13_750X1100X120")
      (description "Integrated Circuit")
      (fields
        (field (name "MANUFACTURER_PART_NUMBER") "MT40A512M8SA-062E:F TR")
        (field (name "MOUSER PART NUMBER") "340-402508-REEL")
      )
      (libsource (lib "SamacSys") (part "MT40A512M8SA-062E_F_TR"))
    )
    (comp (ref "IC57")
      (value "MT40A512M8SA-062E_F_TR")
      (footprint "SamacSys:BGA78C80P9X13_750X1100X120")
      (description "Integrated Circuit")
      (fields
        (field (name "MANUFACTURER_PART_NUMBER") "MT40A512M8SA-062E:F TR")
        (field (name "MOUSER PART NUMBER") "340-402508-REEL")
      )
      (libsource (lib "SamacSys") (part "MT40A512M8SA-062E_F_TR"))
    )
    (comp (ref "IC58")
      (value "MT40A512M8SA-062E_F_TR")
      (footprint "SamacSys:BGA78C80P9X13_750X1100X120")
      (description "Integrated Circuit")
      (fields
        (field (name "MANUFACTURER_PART_NUMBER") "MT40A512M8SA-062E:F TR")
        (field (name "MOUSER PART NUMBER") "340-402508-REEL")
      )
      (libsource (lib "SamacSys") (part "MT40A512M8SA-062E_F_TR"))
    )
    (comp (ref "IC59")
      (value "AT24C04C-SSHM-T")
      (footprint "SamacSys:SOIC127P600X175-8N")
      (description "Integrated Circuit")
      (fields (field (name "MOUSER PART NUMBER") "556-AT24C04C-SSHM-T"))
      (libsource (lib "*") (part "AT24C04C-SSHM-T"))
    )
    (comp (ref "R442")
      (value "36")
      (footprint "RESC1005X40X25ML05T05")
      (fields (field (name "PART NUMBER") "CRCW040236R0FKED") (field (name "MANUFACTURER") "Vishay Dale"))
      (libsource (lib "Altium Content Vault") (part "RES"))
    )
    (comp (ref "R443")
      (value "36")
      (footprint "RESC1005X40X25ML05T05")
      (fields (field (name "PART NUMBER") "CRCW040236R0FKED") (field (name "MANUFACTURER") "Vishay Dale"))
      (libsource (lib "Altium Content Vault") (part "RES"))
    )
    (comp (ref "R444")
      (value "240")
      (footprint "RESC1005X40X25ML05T05")
      (fields (field (name "MANUFACTURER") "Vishay Dale") (field (name "PART NUMBER") "CRCW0402240RFKED"))
      (libsource (lib "Altium Content Vault") (part "RES"))
    )
    (comp (ref "R445")
      (value "240")
      (footprint "RESC1005X40X25ML05T05")
      (fields (field (name "MANUFACTURER") "Vishay Dale") (field (name "PART NUMBER") "CRCW0402240RFKED"))
      (libsource (lib "Altium Content Vault") (part "RES"))
    )
    (comp (ref "R446")
      (value "240")
      (footprint "RESC1005X40X25ML05T05")
      (fields (field (name "MANUFACTURER") "Vishay Dale") (field (name "PART NUMBER") "CRCW0402240RFKED"))
      (libsource (lib "Altium Content Vault") (part "RES"))
    )
    (comp (ref "R447")
      (value "240")
      (footprint "RESC1005X40X25ML05T05")
      (fields (field (name "MANUFACTURER") "Vishay Dale") (field (name "PART NUMBER") "CRCW0402240RFKED"))
      (libsource (lib "Altium Content Vault") (part "RES"))
    )
    (comp (ref "R448")
      (value "162")
      (footprint "RESC1005X40X25LL05T05")
      (fields (field (name "PART NUMBER") "CRCW0402162RFKED") (field (name "MANUFACTURER") "Vishay Dale"))
      (libsource (lib "Altium Content Vault") (part "RES"))
    )
    (comp (ref "R449")
      (value "162")
      (footprint "RESC1005X40X25LL05T05")
      (fields (field (name "PART NUMBER") "CRCW0402162RFKED") (field (name "MANUFACTURER") "Vishay Dale"))
      (libsource (lib "Altium Content Vault") (part "RES"))
    )
    (comp (ref "R450")
      (value "4.7K")
      (footprint "FP-CRCW0402-e3-IPC_B")
      (description "RES Thick Film, 4.7kΩ, 1%, 0.063W, 100ppm/°C, 0402")
      (fields (field (name "TOLERANCE") "1%"))
      (libsource (lib "Altium Content Vault") (part "1029c3af85768c4190bb7ad29bc67b5"))
    )
    (comp (ref "R451")
      (value "0")
      (footprint "FP-CRCW0402-e3-IPC_C")
      (description "RES Thick Film, 0Ω, 0.063W, 0402")
      (fields (field (name "TOLERANCE") "5%"))
      (libsource (lib "Altium Content Vault") (part "1029c3af85768c4190bb7ad29bc67b5"))
    )
    (comp (ref "R452")
      (value "0")
      (footprint "FP-CRCW0402-e3-IPC_C")
      (description "RES Thick Film, 0Ω, 0.063W, 0402")
      (fields (field (name "TOLERANCE") "5%"))
      (libsource (lib "Altium Content Vault") (part "1029c3af85768c4190bb7ad29bc67b5"))
    )
    (comp (ref "R453")
      (value "4.7K")
      (footprint "RESC1005X40X25LL05T05")
      (description "Chip Resistor, 4.7 KOhm, +/- 1%, 0.1 W, -55 to 155 degC, 0402 (1005 Metric), RoHS, Tape and Reel")
      (fields (field (name "TOLERANCE") "1%") (field (name "PARTNUMBER") "ERJ-2RKF4701X"))
      (libsource (lib "Altium Content Vault") (part "RES-2"))
    )
    (comp (ref "R454")
      (value "4.7K")
      (footprint "RESC1005X40X25LL05T05")
      (description "Chip Resistor, 4.7 KOhm, +/- 1%, 0.1 W, -55 to 155 degC, 0402 (1005 Metric), RoHS, Tape and Reel")
      (fields (field (name "TOLERANCE") "1%") (field (name "PARTNUMBER") "ERJ-2RKF4701X"))
      (libsource (lib "Altium Content Vault") (part "RES-2"))
    )
    (comp (ref "R455")
      (value "36")
      (footprint "RESC1005X40X25ML05T05")
      (fields (field (name "PART NUMBER") "CRCW040236R0FKED") (field (name "MANUFACTURER") "Vishay Dale"))
      (libsource (lib "Altium Content Vault") (part "RES"))
    )
    (comp (ref "R456")
      (value "36")
      (footprint "RESC1005X40X25ML05T05")
      (fields (field (name "PART NUMBER") "CRCW040236R0FKED") (field (name "MANUFACTURER") "Vishay Dale"))
      (libsource (lib "Altium Content Vault") (part "RES"))
    )
    (comp (ref "R457")
      (value "240")
      (footprint "RESC1005X40X25ML05T05")
      (fields (field (name "MANUFACTURER") "Vishay Dale") (field (name "PART NUMBER") "CRCW0402240RFKED"))
      (libsource (lib "Altium Content Vault") (part "RES"))
    )
    (comp (ref "R458")
      (value "240")
      (footprint "RESC1005X40X25ML05T05")
      (fields (field (name "MANUFACTURER") "Vishay Dale") (field (name "PART NUMBER") "CRCW0402240RFKED"))
      (libsource (lib "Altium Content Vault") (part "RES"))
    )
    (comp (ref "R459")
      (value "4.7K")
      (footprint "RESC1005X40X25LL05T05")
      (description "Chip Resistor, 4.7 KOhm, +/- 1%, 0.1 W, -55 to 155 degC, 0402 (1005 Metric), RoHS, Tape and Reel")
      (fields (field (name "TOLERANCE") "1%") (field (name "PARTNUMBER") "ERJ-2RKF4701X"))
      (libsource (lib "Altium Content Vault") (part "RES-2"))
    )
    (comp (ref "R460")
      (value "240")
      (footprint "RESC1005X40X25ML05T05")
      (fields (field (name "MANUFACTURER") "Vishay Dale") (field (name "PART NUMBER") "CRCW0402240RFKED"))
      (libsource (lib "Altium Content Vault") (part "RES"))
    )
    (comp (ref "R461")
      (value "240")
      (footprint "RESC1005X40X25ML05T05")
      (fields (field (name "MANUFACTURER") "Vishay Dale") (field (name "PART NUMBER") "CRCW0402240RFKED"))
      (libsource (lib "Altium Content Vault") (part "RES"))
    )
    (comp (ref "R462")
      (value "39")
      (footprint "RESC1005X40X25LL05T05")
      (fields (field (name "PART NUMBER") "ERJ2RKF39R0X") (field (name "MANUFACTURER") "Panasonic"))
      (libsource (lib "Altium Content Vault") (part "RES"))
    )
    (comp (ref "R463")
      (value "39")
      (footprint "RESC1005X40X25LL05T05")
      (fields (field (name "PART NUMBER") "ERJ2RKF39R0X") (field (name "MANUFACTURER") "Panasonic"))
      (libsource (lib "Altium Content Vault") (part "RES"))
    )
    (comp (ref "R464")
      (value "39")
      (footprint "RESC1005X40X25LL05T05")
      (fields (field (name "PART NUMBER") "ERJ2RKF39R0X") (field (name "MANUFACTURER") "Panasonic"))
      (libsource (lib "Altium Content Vault") (part "RES"))
    )
    (comp (ref "R465")
      (value "39")
      (footprint "RESC1005X40X25LL05T05")
      (fields (field (name "PART NUMBER") "ERJ2RKF39R0X") (field (name "MANUFACTURER") "Panasonic"))
      (libsource (lib "Altium Content Vault") (part "RES"))
    )
    (comp (ref "R466")
      (value "39")
      (footprint "RESC1005X40X25LL05T05")
      (fields (field (name "PART NUMBER") "ERJ2RKF39R0X") (field (name "MANUFACTURER") "Panasonic"))
      (libsource (lib "Altium Content Vault") (part "RES"))
    )
    (comp (ref "R467")
      (value "39")
      (footprint "RESC1005X40X25LL05T05")
      (fields (field (name "PART NUMBER") "ERJ2RKF39R0X") (field (name "MANUFACTURER") "Panasonic"))
      (libsource (lib "Altium Content Vault") (part "RES"))
    )
    (comp (ref "R468")
      (value "39")
      (footprint "RESC1005X40X25LL05T05")
      (fields (field (name "PART NUMBER") "ERJ2RKF39R0X") (field (name "MANUFACTURER") "Panasonic"))
      (libsource (lib "Altium Content Vault") (part "RES"))
    )
    (comp (ref "R469")
      (value "39")
      (footprint "RESC1005X40X25LL05T05")
      (fields (field (name "PART NUMBER") "ERJ2RKF39R0X") (field (name "MANUFACTURER") "Panasonic"))
      (libsource (lib "Altium Content Vault") (part "RES"))
    )
    (comp (ref "R470")
      (value "39")
      (footprint "RESC1005X40X25LL05T05")
      (fields (field (name "PART NUMBER") "ERJ2RKF39R0X") (field (name "MANUFACTURER") "Panasonic"))
      (libsource (lib "Altium Content Vault") (part "RES"))
    )
    (comp (ref "R471")
      (value "39")
      (footprint "RESC1005X40X25LL05T05")
      (fields (field (name "PART NUMBER") "ERJ2RKF39R0X") (field (name "MANUFACTURER") "Panasonic"))
      (libsource (lib "Altium Content Vault") (part "RES"))
    )
    (comp (ref "R472")
      (value "39")
      (footprint "RESC1005X40X25LL05T05")
      (fields (field (name "PART NUMBER") "ERJ2RKF39R0X") (field (name "MANUFACTURER") "Panasonic"))
      (libsource (lib "Altium Content Vault") (part "RES"))
    )
    (comp (ref "R473")
      (value "39")
      (footprint "RESC1005X40X25LL05T05")
      (fields (field (name "PART NUMBER") "ERJ2RKF39R0X") (field (name "MANUFACTURER") "Panasonic"))
      (libsource (lib "Altium Content Vault") (part "RES"))
    )
    (comp (ref "R474")
      (value "39")
      (footprint "RESC1005X40X25LL05T05")
      (fields (field (name "PART NUMBER") "ERJ2RKF39R0X") (field (name "MANUFACTURER") "Panasonic"))
      (libsource (lib "Altium Content Vault") (part "RES"))
    )
    (comp (ref "R475")
      (value "39")
      (footprint "RESC1005X40X25LL05T05")
      (fields (field (name "PART NUMBER") "ERJ2RKF39R0X") (field (name "MANUFACTURER") "Panasonic"))
      (libsource (lib "Altium Content Vault") (part "RES"))
    )
    (comp (ref "R476")
      (value "39")
      (footprint "RESC1005X40X25LL05T05")
      (fields (field (name "PART NUMBER") "ERJ2RKF39R0X") (field (name "MANUFACTURER") "Panasonic"))
      (libsource (lib "Altium Content Vault") (part "RES"))
    )
    (comp (ref "R477")
      (value "39")
      (footprint "RESC1005X40X25LL05T05")
      (fields (field (name "PART NUMBER") "ERJ2RKF39R0X") (field (name "MANUFACTURER") "Panasonic"))
      (libsource (lib "Altium Content Vault") (part "RES"))
    )
    (comp (ref "R478")
      (value "39")
      (footprint "RESC1005X40X25LL05T05")
      (fields (field (name "PART NUMBER") "ERJ2RKF39R0X") (field (name "MANUFACTURER") "Panasonic"))
      (libsource (lib "Altium Content Vault") (part "RES"))
    )
    (comp (ref "R479")
      (value "39")
      (footprint "RESC1005X40X25LL05T05")
      (fields (field (name "PART NUMBER") "ERJ2RKF39R0X") (field (name "MANUFACTURER") "Panasonic"))
      (libsource (lib "Altium Content Vault") (part "RES"))
    )
    (comp (ref "R480")
      (value "39")
      (footprint "RESC1005X40X25LL05T05")
      (fields (field (name "PART NUMBER") "ERJ2RKF39R0X") (field (name "MANUFACTURER") "Panasonic"))
      (libsource (lib "Altium Content Vault") (part "RES"))
    )
    (comp (ref "R481")
      (value "39")
      (footprint "RESC1005X40X25LL05T05")
      (fields (field (name "PART NUMBER") "ERJ2RKF39R0X") (field (name "MANUFACTURER") "Panasonic"))
      (libsource (lib "Altium Content Vault") (part "RES"))
    )
    (comp (ref "R482")
      (value "39")
      (footprint "RESC1005X40X25LL05T05")
      (fields (field (name "PART NUMBER") "ERJ2RKF39R0X") (field (name "MANUFACTURER") "Panasonic"))
      (libsource (lib "Altium Content Vault") (part "RES"))
    )
    (comp (ref "R483")
      (value "39")
      (footprint "RESC1005X40X25LL05T05")
      (fields (field (name "PART NUMBER") "ERJ2RKF39R0X") (field (name "MANUFACTURER") "Panasonic"))
      (libsource (lib "Altium Content Vault") (part "RES"))
    )
    (comp (ref "R484")
      (value "39")
      (footprint "RESC1005X40X25LL05T05")
      (fields (field (name "PART NUMBER") "ERJ2RKF39R0X") (field (name "MANUFACTURER") "Panasonic"))
      (libsource (lib "Altium Content Vault") (part "RES"))
    )
    (comp (ref "R485")
      (value "39")
      (footprint "RESC1005X40X25LL05T05")
      (fields (field (name "PART NUMBER") "ERJ2RKF39R0X") (field (name "MANUFACTURER") "Panasonic"))
      (libsource (lib "Altium Content Vault") (part "RES"))
    )
    (comp (ref "R486")
      (value "39")
      (footprint "RESC1005X40X25LL05T05")
      (fields (field (name "PART NUMBER") "ERJ2RKF39R0X") (field (name "MANUFACTURER") "Panasonic"))
      (libsource (lib "Altium Content Vault") (part "RES"))
    )
    (comp (ref "R487")
      (value "39")
      (footprint "RESC1005X40X25LL05T05")
      (fields (field (name "PART NUMBER") "ERJ2RKF39R0X") (field (name "MANUFACTURER") "Panasonic"))
      (libsource (lib "Altium Content Vault") (part "RES"))
    )
    (comp (ref "R488")
      (value "39")
      (footprint "RESC1005X40X25LL05T05")
      (fields (field (name "PART NUMBER") "ERJ2RKF39R0X") (field (name "MANUFACTURER") "Panasonic"))
      (libsource (lib "Altium Content Vault") (part "RES"))
    )
    (comp (ref "R489")
      (value "39")
      (footprint "RESC1005X40X25LL05T05")
      (fields (field (name "PART NUMBER") "ERJ2RKF39R0X") (field (name "MANUFACTURER") "Panasonic"))
      (libsource (lib "Altium Content Vault") (part "RES"))
    )
    (comp (ref "R490")
      (value "39")
      (footprint "RESC1005X40X25LL05T05")
      (fields (field (name "PART NUMBER") "ERJ2RKF39R0X") (field (name "MANUFACTURER") "Panasonic"))
      (libsource (lib "Altium Content Vault") (part "RES"))
    )
  )
  (nets
    (net (code "1") (name "+2V4_VPP") (class "Default")
      (node (ref "C716") (pin "1") (pinfunction "1_1") (pintype "passive"))
      (node (ref "C717") (pin "1") (pinfunction "1_1") (pintype "passive"))
      (node (ref "C718") (pin "1") (pinfunction "1_1") (pintype "passive"))
      (node (ref "C719") (pin "1") (pinfunction "1_1") (pintype "passive"))
      (node (ref "C720") (pin "1") (pinfunction "1_1") (pintype "passive"))
      (node (ref "C721") (pin "1") (pinfunction "1_1") (pintype "passive"))
      (node (ref "C722") (pin "1") (pinfunction "1_1") (pintype "passive"))
      (node (ref "C723") (pin "1") (pinfunction "1_1") (pintype "passive"))
      (node (ref "C733") (pin "1") (pinfunction "1_1") (pintype "passive"))
      (node (ref "C734") (pin "1") (pinfunction "1_1") (pintype "passive"))
      (node (ref "C735") (pin "1") (pinfunction "1_1") (pintype "passive"))
      (node (ref "C736") (pin "1") (pinfunction "1_1") (pintype "passive"))
      (node (ref "C737") (pin "1") (pinfunction "1_1") (pintype "passive"))
      (node (ref "C738") (pin "1") (pinfunction "1_1") (pintype "passive"))
      (node (ref "C739") (pin "1") (pinfunction "1_1") (pintype "passive"))
      (node (ref "C740") (pin "1") (pinfunction "1_1") (pintype "passive"))
      (node (ref "IC51") (pin "B1") (pinfunction "VPP1_B1") (pintype "passive"))
      (node (ref "IC51") (pin "M9") (pinfunction "VPP2_M9") (pintype "passive"))
      (node (ref "IC52") (pin "B1") (pinfunction "VPP1_B1") (pintype "passive"))
      (node (ref "IC52") (pin "M9") (pinfunction "VPP2_M9") (pintype "passive"))
      (node (ref "IC53") (pin "B1") (pinfunction "VPP1_B1") (pintype "passive"))
      (node (ref "IC53") (pin "M9") (pinfunction "VPP2_M9") (pintype "passive"))
      (node (ref "IC54") (pin "B1") (pinfunction "VPP1_B1") (pintype "passive"))
      (node (ref "IC54") (pin "M9") (pinfunction "VPP2_M9") (pintype "passive"))
      (node (ref "IC55") (pin "B1") (pinfunction "VPP1_B1") (pintype "passive"))
      (node (ref "IC55") (pin "M9") (pinfunction "VPP2_M9") (pintype "passive"))
      (node (ref "IC56") (pin "B1") (pinfunction "VPP1_B1") (pintype "passive"))
      (node (ref "IC56") (pin "M9") (pinfunction "VPP2_M9") (pintype "passive"))
      (node (ref "IC57") (pin "B1") (pinfunction "VPP1_B1") (pintype "passive"))
      (node (ref "IC57") (pin "M9") (pinfunction "VPP2_M9") (pintype "passive"))
      (node (ref "IC58") (pin "B1") (pinfunction "VPP1_B1") (pintype "passive"))
      (node (ref "IC58") (pin "M9") (pinfunction "VPP2_M9") (pintype "passive"))
    )
    (net (code "2") (name "+3V3") (class "Default")
      (node (ref "C742") (pin "1") (pinfunction "1_1") (pintype "passive"))
      (node (ref "IC59") (pin "2") (pinfunction "A1/NC_2") (pintype "passive"))
      (node (ref "IC59") (pin "8") (pinfunction "VCC_8") (pintype "passive"))
    )
    (net (code "3") (name "+GVDD") (class "Default")
      (node (ref "C751") (pin "2") (pinfunction "2_2") (pintype "passive"))
      (node (ref "C752") (pin "2") (pinfunction "2_2") (pintype "passive"))
      (node (ref "C753") (pin "2") (pinfunction "2_2") (pintype "passive"))
      (node (ref "C754") (pin "2") (pinfunction "2_2") (pintype "passive"))
      (node (ref "C755") (pin "2") (pinfunction "2_2") (pintype "passive"))
      (node (ref "C756") (pin "2") (pinfunction "2_2") (pintype "passive"))
      (node (ref "C757") (pin "2") (pinfunction "2_2") (pintype "passive"))
      (node (ref "C758") (pin "2") (pinfunction "2_2") (pintype "passive"))
      (node (ref "C759") (pin "1") (pinfunction "1_1") (pintype "passive"))
      (node (ref "C760") (pin "1") (pinfunction "1_1") (pintype "passive"))
      (node (ref "C761") (pin "2") (pinfunction "2_2") (pintype "passive"))
      (node (ref "C762") (pin "2") (pinfunction "2_2") (pintype "passive"))
      (node (ref "C763") (pin "2") (pinfunction "2_2") (pintype "passive"))
      (node (ref "C764") (pin "2") (pinfunction "2_2") (pintype "passive"))
      (node (ref "C765") (pin "2") (pinfunction "2_2") (pintype "passive"))
      (node (ref "C766") (pin "2") (pinfunction "2_2") (pintype "passive"))
      (node (ref "C767") (pin "2") (pinfunction "2_2") (pintype "passive"))
      (node (ref "C768") (pin "2") (pinfunction "2_2") (pintype "passive"))
      (node (ref "C769") (pin "1") (pinfunction "1_1") (pintype "passive"))
      (node (ref "C770") (pin "1") (pinfunction "1_1") (pintype "passive"))
      (node (ref "C771") (pin "2") (pinfunction "2_2") (pintype "passive"))
      (node (ref "C772") (pin "2") (pinfunction "2_2") (pintype "passive"))
      (node (ref "C773") (pin "2") (pinfunction "2_2") (pintype "passive"))
      (node (ref "C774") (pin "2") (pinfunction "2_2") (pintype "passive"))
      (node (ref "C775") (pin "2") (pinfunction "2_2") (pintype "passive"))
      (node (ref "C776") (pin "2") (pinfunction "2_2") (pintype "passive"))
      (node (ref "C777") (pin "2") (pinfunction "2_2") (pintype "passive"))
      (node (ref "C778") (pin "2") (pinfunction "2_2") (pintype "passive"))
      (node (ref "C779") (pin "1") (pinfunction "1_1") (pintype "passive"))
      (node (ref "C780") (pin "1") (pinfunction "1_1") (pintype "passive"))
      (node (ref "C781") (pin "2") (pinfunction "2_2") (pintype "passive"))
      (node (ref "C782") (pin "2") (pinfunction "2_2") (pintype "passive"))
      (node (ref "C783") (pin "2") (pinfunction "2_2") (pintype "passive"))
      (node (ref "C784") (pin "2") (pinfunction "2_2") (pintype "passive"))
      (node (ref "C785") (pin "2") (pinfunction "2_2") (pintype "passive"))
      (node (ref "C786") (pin "2") (pinfunction "2_2") (pintype "passive"))
      (node (ref "C787") (pin "2") (pinfunction "2_2") (pintype "passive"))
      (node (ref "C788") (pin "2") (pinfunction "2_2") (pintype "passive"))
      (node (ref "C789") (pin "1") (pinfunction "1_1") (pintype "passive"))
      (node (ref "C790") (pin "1") (pinfunction "1_1") (pintype "passive"))
      (node (ref "C797") (pin "2") (pinfunction "2_2") (pintype "passive"))
      (node (ref "C798") (pin "2") (pinfunction "2_2") (pintype "passive"))
      (node (ref "C799") (pin "2") (pinfunction "2_2") (pintype "passive"))
      (node (ref "C800") (pin "2") (pinfunction "2_2") (pintype "passive"))
      (node (ref "C801") (pin "2") (pinfunction "2_2") (pintype "passive"))
      (node (ref "C802") (pin "2") (pinfunction "2_2") (pintype "passive"))
      (node (ref "C803") (pin "2") (pinfunction "2_2") (pintype "passive"))
      (node (ref "C804") (pin "2") (pinfunction "2_2") (pintype "passive"))
      (node (ref "C805") (pin "1") (pinfunction "1_1") (pintype "passive"))
      (node (ref "C806") (pin "1") (pinfunction "1_1") (pintype "passive"))
      (node (ref "C807") (pin "2") (pinfunction "2_2") (pintype "passive"))
      (node (ref "C808") (pin "2") (pinfunction "2_2") (pintype "passive"))
      (node (ref "C809") (pin "2") (pinfunction "2_2") (pintype "passive"))
      (node (ref "C810") (pin "2") (pinfunction "2_2") (pintype "passive"))
      (node (ref "C811") (pin "2") (pinfunction "2_2") (pintype "passive"))
      (node (ref "C812") (pin "2") (pinfunction "2_2") (pintype "passive"))
      (node (ref "C813") (pin "2") (pinfunction "2_2") (pintype "passive"))
      (node (ref "C814") (pin "2") (pinfunction "2_2") (pintype "passive"))
      (node (ref "C815") (pin "1") (pinfunction "1_1") (pintype "passive"))
      (node (ref "C816") (pin "1") (pinfunction "1_1") (pintype "passive"))
      (node (ref "C823") (pin "2") (pinfunction "2_2") (pintype "passive"))
      (node (ref "C824") (pin "2") (pinfunction "2_2") (pintype "passive"))
      (node (ref "C825") (pin "2") (pinfunction "2_2") (pintype "passive"))
      (node (ref "C826") (pin "2") (pinfunction "2_2") (pintype "passive"))
      (node (ref "C827") (pin "2") (pinfunction "2_2") (pintype "passive"))
      (node (ref "C828") (pin "2") (pinfunction "2_2") (pintype "passive"))
      (node (ref "C829") (pin "2") (pinfunction "2_2") (pintype "passive"))
      (node (ref "C830") (pin "2") (pinfunction "2_2") (pintype "passive"))
      (node (ref "C831") (pin "1") (pinfunction "1_1") (pintype "passive"))
      (node (ref "C832") (pin "1") (pinfunction "1_1") (pintype "passive"))
      (node (ref "C833") (pin "2") (pinfunction "2_2") (pintype "passive"))
      (node (ref "C834") (pin "2") (pinfunction "2_2") (pintype "passive"))
      (node (ref "C835") (pin "2") (pinfunction "2_2") (pintype "passive"))
      (node (ref "C836") (pin "2") (pinfunction "2_2") (pintype "passive"))
      (node (ref "C837") (pin "2") (pinfunction "2_2") (pintype "passive"))
      (node (ref "C838") (pin "2") (pinfunction "2_2") (pintype "passive"))
      (node (ref "C839") (pin "2") (pinfunction "2_2") (pintype "passive"))
      (node (ref "C840") (pin "2") (pinfunction "2_2") (pintype "passive"))
      (node (ref "C841") (pin "1") (pinfunction "1_1") (pintype "passive"))
      (node (ref "C842") (pin "1") (pinfunction "1_1") (pintype "passive"))
      (node (ref "IC51") (pin "A1") (pinfunction "VDD1_A1") (pintype "passive"))
      (node (ref "IC51") (pin "B2") (pinfunction "VDDQ1_B2") (pintype "passive"))
      (node (ref "IC51") (pin "B8") (pinfunction "VDDQ2_B8") (pintype "passive"))
      (node (ref "IC51") (pin "C1") (pinfunction "VDDQ3_C1") (pintype "passive"))
      (node (ref "IC51") (pin "C7") (pinfunction "VDD2_C7") (pintype "passive"))
      (node (ref "IC51") (pin "C9") (pinfunction "VDDQ4_C9") (pintype "passive"))
      (node (ref "IC51") (pin "E2") (pinfunction "VDDQ5_E2") (pintype "passive"))
      (node (ref "IC51") (pin "E8") (pinfunction "VDDQ6_E8") (pintype "passive"))
      (node (ref "IC51") (pin "F1") (pinfunction "VDD3_F1") (pintype "passive"))
      (node (ref "IC51") (pin "F9") (pinfunction "VDD4_F9") (pintype "passive"))
      (node (ref "IC51") (pin "H1") (pinfunction "VDD5_H1") (pintype "passive"))
      (node (ref "IC51") (pin "J9") (pinfunction "VDD6_J9") (pintype "passive"))
      (node (ref "IC51") (pin "M1") (pinfunction "VDD7_M1") (pintype "passive"))
      (node (ref "IC51") (pin "N9") (pinfunction "VDD8_N9") (pintype "passive"))
      (node (ref "IC52") (pin "A1") (pinfunction "VDD1_A1") (pintype "passive"))
      (node (ref "IC52") (pin "B2") (pinfunction "VDDQ1_B2") (pintype "passive"))
      (node (ref "IC52") (pin "B8") (pinfunction "VDDQ2_B8") (pintype "passive"))
      (node (ref "IC52") (pin "C1") (pinfunction "VDDQ3_C1") (pintype "passive"))
      (node (ref "IC52") (pin "C7") (pinfunction "VDD2_C7") (pintype "passive"))
      (node (ref "IC52") (pin "C9") (pinfunction "VDDQ4_C9") (pintype "passive"))
      (node (ref "IC52") (pin "E2") (pinfunction "VDDQ5_E2") (pintype "passive"))
      (node (ref "IC52") (pin "E8") (pinfunction "VDDQ6_E8") (pintype "passive"))
      (node (ref "IC52") (pin "F1") (pinfunction "VDD3_F1") (pintype "passive"))
      (node (ref "IC52") (pin "F9") (pinfunction "VDD4_F9") (pintype "passive"))
      (node (ref "IC52") (pin "H1") (pinfunction "VDD5_H1") (pintype "passive"))
      (node (ref "IC52") (pin "J9") (pinfunction "VDD6_J9") (pintype "passive"))
      (node (ref "IC52") (pin "M1") (pinfunction "VDD7_M1") (pintype "passive"))
      (node (ref "IC52") (pin "N9") (pinfunction "VDD8_N9") (pintype "passive"))
      (node (ref "IC53") (pin "A1") (pinfunction "VDD1_A1") (pintype "passive"))
      (node (ref "IC53") (pin "B2") (pinfunction "VDDQ1_B2") (pintype "passive"))
      (node (ref "IC53") (pin "B8") (pinfunction "VDDQ2_B8") (pintype "passive"))
      (node (ref "IC53") (pin "C1") (pinfunction "VDDQ3_C1") (pintype "passive"))
      (node (ref "IC53") (pin "C7") (pinfunction "VDD2_C7") (pintype "passive"))
      (node (ref "IC53") (pin "C9") (pinfunction "VDDQ4_C9") (pintype "passive"))
      (node (ref "IC53") (pin "E2") (pinfunction "VDDQ5_E2") (pintype "passive"))
      (node (ref "IC53") (pin "E8") (pinfunction "VDDQ6_E8") (pintype "passive"))
      (node (ref "IC53") (pin "F1") (pinfunction "VDD3_F1") (pintype "passive"))
      (node (ref "IC53") (pin "F9") (pinfunction "VDD4_F9") (pintype "passive"))
      (node (ref "IC53") (pin "H1") (pinfunction "VDD5_H1") (pintype "passive"))
      (node (ref "IC53") (pin "J9") (pinfunction "VDD6_J9") (pintype "passive"))
      (node (ref "IC53") (pin "M1") (pinfunction "VDD7_M1") (pintype "passive"))
      (node (ref "IC53") (pin "N9") (pinfunction "VDD8_N9") (pintype "passive"))
      (node (ref "IC54") (pin "A1") (pinfunction "VDD1_A1") (pintype "passive"))
      (node (ref "IC54") (pin "B2") (pinfunction "VDDQ1_B2") (pintype "passive"))
      (node (ref "IC54") (pin "B8") (pinfunction "VDDQ2_B8") (pintype "passive"))
      (node (ref "IC54") (pin "C1") (pinfunction "VDDQ3_C1") (pintype "passive"))
      (node (ref "IC54") (pin "C7") (pinfunction "VDD2_C7") (pintype "passive"))
      (node (ref "IC54") (pin "C9") (pinfunction "VDDQ4_C9") (pintype "passive"))
      (node (ref "IC54") (pin "E2") (pinfunction "VDDQ5_E2") (pintype "passive"))
      (node (ref "IC54") (pin "E8") (pinfunction "VDDQ6_E8") (pintype "passive"))
      (node (ref "IC54") (pin "F1") (pinfunction "VDD3_F1") (pintype "passive"))
      (node (ref "IC54") (pin "F9") (pinfunction "VDD4_F9") (pintype "passive"))
      (node (ref "IC54") (pin "H1") (pinfunction "VDD5_H1") (pintype "passive"))
      (node (ref "IC54") (pin "J9") (pinfunction "VDD6_J9") (pintype "passive"))
      (node (ref "IC54") (pin "M1") (pinfunction "VDD7_M1") (pintype "passive"))
      (node (ref "IC54") (pin "N9") (pinfunction "VDD8_N9") (pintype "passive"))
      (node (ref "IC55") (pin "A1") (pinfunction "VDD1_A1") (pintype "passive"))
      (node (ref "IC55") (pin "B2") (pinfunction "VDDQ1_B2") (pintype "passive"))
      (node (ref "IC55") (pin "B8") (pinfunction "VDDQ2_B8") (pintype "passive"))
      (node (ref "IC55") (pin "C1") (pinfunction "VDDQ3_C1") (pintype "passive"))
      (node (ref "IC55") (pin "C7") (pinfunction "VDD2_C7") (pintype "passive"))
      (node (ref "IC55") (pin "C9") (pinfunction "VDDQ4_C9") (pintype "passive"))
      (node (ref "IC55") (pin "E2") (pinfunction "VDDQ5_E2") (pintype "passive"))
      (node (ref "IC55") (pin "E8") (pinfunction "VDDQ6_E8") (pintype "passive"))
      (node (ref "IC55") (pin "F1") (pinfunction "VDD3_F1") (pintype "passive"))
      (node (ref "IC55") (pin "F9") (pinfunction "VDD4_F9") (pintype "passive"))
      (node (ref "IC55") (pin "H1") (pinfunction "VDD5_H1") (pintype "passive"))
      (node (ref "IC55") (pin "J9") (pinfunction "VDD6_J9") (pintype "passive"))
      (node (ref "IC55") (pin "M1") (pinfunction "VDD7_M1") (pintype "passive"))
      (node (ref "IC55") (pin "N9") (pinfunction "VDD8_N9") (pintype "passive"))
      (node (ref "IC56") (pin "A1") (pinfunction "VDD1_A1") (pintype "passive"))
      (node (ref "IC56") (pin "B2") (pinfunction "VDDQ1_B2") (pintype "passive"))
      (node (ref "IC56") (pin "B8") (pinfunction "VDDQ2_B8") (pintype "passive"))
      (node (ref "IC56") (pin "C1") (pinfunction "VDDQ3_C1") (pintype "passive"))
      (node (ref "IC56") (pin "C7") (pinfunction "VDD2_C7") (pintype "passive"))
      (node (ref "IC56") (pin "C9") (pinfunction "VDDQ4_C9") (pintype "passive"))
      (node (ref "IC56") (pin "E2") (pinfunction "VDDQ5_E2") (pintype "passive"))
      (node (ref "IC56") (pin "E8") (pinfunction "VDDQ6_E8") (pintype "passive"))
      (node (ref "IC56") (pin "F1") (pinfunction "VDD3_F1") (pintype "passive"))
      (node (ref "IC56") (pin "F9") (pinfunction "VDD4_F9") (pintype "passive"))
      (node (ref "IC56") (pin "H1") (pinfunction "VDD5_H1") (pintype "passive"))
      (node (ref "IC56") (pin "J9") (pinfunction "VDD6_J9") (pintype "passive"))
      (node (ref "IC56") (pin "M1") (pinfunction "VDD7_M1") (pintype "passive"))
      (node (ref "IC56") (pin "N9") (pinfunction "VDD8_N9") (pintype "passive"))
      (node (ref "IC57") (pin "A1") (pinfunction "VDD1_A1") (pintype "passive"))
      (node (ref "IC57") (pin "B2") (pinfunction "VDDQ1_B2") (pintype "passive"))
      (node (ref "IC57") (pin "B8") (pinfunction "VDDQ2_B8") (pintype "passive"))
      (node (ref "IC57") (pin "C1") (pinfunction "VDDQ3_C1") (pintype "passive"))
      (node (ref "IC57") (pin "C7") (pinfunction "VDD2_C7") (pintype "passive"))
      (node (ref "IC57") (pin "C9") (pinfunction "VDDQ4_C9") (pintype "passive"))
      (node (ref "IC57") (pin "E2") (pinfunction "VDDQ5_E2") (pintype "passive"))
      (node (ref "IC57") (pin "E8") (pinfunction "VDDQ6_E8") (pintype "passive"))
      (node (ref "IC57") (pin "F1") (pinfunction "VDD3_F1") (pintype "passive"))
      (node (ref "IC57") (pin "F9") (pinfunction "VDD4_F9") (pintype "passive"))
      (node (ref "IC57") (pin "H1") (pinfunction "VDD5_H1") (pintype "passive"))
      (node (ref "IC57") (pin "J9") (pinfunction "VDD6_J9") (pintype "passive"))
      (node (ref "IC57") (pin "M1") (pinfunction "VDD7_M1") (pintype "passive"))
      (node (ref "IC57") (pin "N9") (pinfunction "VDD8_N9") (pintype "passive"))
      (node (ref "IC58") (pin "A1") (pinfunction "VDD1_A1") (pintype "passive"))
      (node (ref "IC58") (pin "B2") (pinfunction "VDDQ1_B2") (pintype "passive"))
      (node (ref "IC58") (pin "B8") (pinfunction "VDDQ2_B8") (pintype "passive"))
      (node (ref "IC58") (pin "C1") (pinfunction "VDDQ3_C1") (pintype "passive"))
      (node (ref "IC58") (pin "C7") (pinfunction "VDD2_C7") (pintype "passive"))
      (node (ref "IC58") (pin "C9") (pinfunction "VDDQ4_C9") (pintype "passive"))
      (node (ref "IC58") (pin "E2") (pinfunction "VDDQ5_E2") (pintype "passive"))
      (node (ref "IC58") (pin "E8") (pinfunction "VDDQ6_E8") (pintype "passive"))
      (node (ref "IC58") (pin "F1") (pinfunction "VDD3_F1") (pintype "passive"))
      (node (ref "IC58") (pin "F9") (pinfunction "VDD4_F9") (pintype "passive"))
      (node (ref "IC58") (pin "H1") (pinfunction "VDD5_H1") (pintype "passive"))
      (node (ref "IC58") (pin "J9") (pinfunction "VDD6_J9") (pintype "passive"))
      (node (ref "IC58") (pin "M1") (pinfunction "VDD7_M1") (pintype "passive"))
      (node (ref "IC58") (pin "N9") (pinfunction "VDD8_N9") (pintype "passive"))
      (node (ref "R448") (pin "1") (pinfunction "1_1") (pintype "passive"))
      (node (ref "R450") (pin "2") (pinfunction "2_2") (pintype "passive"))
      (node (ref "R453") (pin "1") (pinfunction "1_1") (pintype "passive"))
    )
    (net (code "4") (name "/PR_ALERT_N") (class "Default")
      (node (ref "IC51") (pin "L9") (pinfunction "~{ALERT}_L9") (pintype "passive"))
      (node (ref "IC52") (pin "L9") (pinfunction "~{ALERT}_L9") (pintype "passive"))
      (node (ref "IC53") (pin "L9") (pinfunction "~{ALERT}_L9") (pintype "passive"))
      (node (ref "IC54") (pin "L9") (pinfunction "~{ALERT}_L9") (pintype "passive"))
      (node (ref "IC55") (pin "L9") (pinfunction "~{ALERT}_L9") (pintype "passive"))
      (node (ref "IC56") (pin "L9") (pinfunction "~{ALERT}_L9") (pintype "passive"))
      (node (ref "IC57") (pin "L9") (pinfunction "~{ALERT}_L9") (pintype "passive"))
      (node (ref "IC58") (pin "L9") (pinfunction "~{ALERT}_L9") (pintype "passive"))
    )
    (net (code "5") (name "/PR_DDR4_A0") (class "Default")
      (node (ref "IC51") (pin "L3") (pinfunction "A0_L3") (pintype "passive"))
      (node (ref "IC52") (pin "L3") (pinfunction "A0_L3") (pintype "passive"))
      (node (ref "IC53") (pin "L3") (pinfunction "A0_L3") (pintype "passive"))
      (node (ref "IC54") (pin "L3") (pinfunction "A0_L3") (pintype "passive"))
      (node (ref "IC55") (pin "L3") (pinfunction "A0_L3") (pintype "passive"))
      (node (ref "IC56") (pin "L3") (pinfunction "A0_L3") (pintype "passive"))
      (node (ref "IC57") (pin "L3") (pinfunction "A0_L3") (pintype "passive"))
      (node (ref "IC58") (pin "L3") (pinfunction "A0_L3") (pintype "passive"))
      (node (ref "R465") (pin "1") (pinfunction "1_1") (pintype "passive"))
    )
    (net (code "6") (name "/PR_DDR4_A1") (class "Default")
      (node (ref "IC30") (pin "AA21") (pinfunction "D1_MA01_AA21") (pintype "passive"))
      (node (ref "IC51") (pin "L7") (pinfunction "A1_L7") (pintype "passive"))
      (node (ref "IC52") (pin "L7") (pinfunction "A1_L7") (pintype "passive"))
      (node (ref "IC53") (pin "L7") (pinfunction "A1_L7") (pintype "passive"))
      (node (ref "IC54") (pin "L7") (pinfunction "A1_L7") (pintype "passive"))
      (node (ref "IC55") (pin "L7") (pinfunction "A1_L7") (pintype "passive"))
      (node (ref "IC56") (pin "L7") (pinfunction "A1_L7") (pintype "passive"))
      (node (ref "IC57") (pin "L7") (pinfunction "A1_L7") (pintype "passive"))
      (node (ref "IC58") (pin "L7") (pinfunction "A1_L7") (pintype "passive"))
      (node (ref "R466") (pin "1") (pinfunction "1_1") (pintype "passive"))
    )
    (net (code "7") (name "/PR_DDR4_A2") (class "Default")
      (node (ref "IC30") (pin "V23") (pinfunction "D1_MA02_V23") (pintype "passive"))
      (node (ref "IC51") (pin "M3") (pinfunction "A2_M3") (pintype "passive"))
      (node (ref "IC52") (pin "M3") (pinfunction "A2_M3") (pintype "passive"))
      (node (ref "IC53") (pin "M3") (pinfunction "A2_M3") (pintype "passive"))
      (node (ref "IC54") (pin "M3") (pinfunction "A2_M3") (pintype "passive"))
      (node (ref "IC55") (pin "M3") (pinfunction "A2_M3") (pintype "passive"))
      (node (ref "IC56") (pin "M3") (pinfunction "A2_M3") (pintype "passive"))
      (node (ref "IC57") (pin "M3") (pinfunction "A2_M3") (pintype "passive"))
      (node (ref "IC58") (pin "M3") (pinfunction "A2_M3") (pintype "passive"))
      (node (ref "R467") (pin "1") (pinfunction "1_1") (pintype "passive"))
    )
    (net (code "8") (name "/PR_DDR4_A3") (class "Default")
      (node (ref "IC30") (pin "AD23") (pinfunction "D1_MA03_AD23") (pintype "passive"))
      (node (ref "IC51") (pin "K7") (pinfunction "A3_K7") (pintype "passive"))
      (node (ref "IC52") (pin "K7") (pinfunction "A3_K7") (pintype "passive"))
      (node (ref "IC53") (pin "K7") (pinfunction "A3_K7") (pintype "passive"))
      (node (ref "IC54") (pin "K7") (pinfunction "A3_K7") (pintype "passive"))
      (node (ref "IC55") (pin "K7") (pinfunction "A3_K7") (pintype "passive"))
      (node (ref "IC56") (pin "K7") (pinfunction "A3_K7") (pintype "passive"))
      (node (ref "IC57") (pin "K7") (pinfunction "A3_K7") (pintype "passive"))
      (node (ref "IC58") (pin "K7") (pinfunction "A3_K7") (pintype "passive"))
      (node (ref "R468") (pin "1") (pinfunction "1_1") (pintype "passive"))
    )
    (net (code "9") (name "/PR_DDR4_A4") (class "Default")
      (node (ref "IC30") (pin "AA23") (pinfunction "D1_MA04_AA23") (pintype "passive"))
      (node (ref "IC51") (pin "K3") (pinfunction "A4_K3") (pintype "passive"))
      (node (ref "IC52") (pin "K3") (pinfunction "A4_K3") (pintype "passive"))
      (node (ref "IC53") (pin "K3") (pinfunction "A4_K3") (pintype "passive"))
      (node (ref "IC54") (pin "K3") (pinfunction "A4_K3") (pintype "passive"))
      (node (ref "IC55") (pin "K3") (pinfunction "A4_K3") (pintype "passive"))
      (node (ref "IC56") (pin "K3") (pinfunction "A4_K3") (pintype "passive"))
      (node (ref "IC57") (pin "K3") (pinfunction "A4_K3") (pintype "passive"))
      (node (ref "IC58") (pin "K3") (pinfunction "A4_K3") (pintype "passive"))
      (node (ref "R469") (pin "1") (pinfunction "1_1") (pintype "passive"))
    )
    (net (code "10") (name "/PR_DDR4_A5") (class "Default")
      (node (ref "IC30") (pin "W23") (pinfunction "D1_MA05_W23") (pintype "passive"))
      (node (ref "IC51") (pin "L8") (pinfunction "A5_L8") (pintype "passive"))
      (node (ref "IC52") (pin "L8") (pinfunction "A5_L8") (pintype "passive"))
      (node (ref "IC53") (pin "L8") (pinfunction "A5_L8") (pintype "passive"))
      (node (ref "IC54") (pin "L8") (pinfunction "A5_L8") (pintype "passive"))
      (node (ref "IC55") (pin "L8") (pinfunction "A5_L8") (pintype "passive"))
      (node (ref "IC56") (pin "L8") (pinfunction "A5_L8") (pintype "passive"))
      (node (ref "IC57") (pin "L8") (pinfunction "A5_L8") (pintype "passive"))
      (node (ref "IC58") (pin "L8") (pinfunction "A5_L8") (pintype "passive"))
      (node (ref "R470") (pin "1") (pinfunction "1_1") (pintype "passive"))
    )
    (net (code "11") (name "/PR_DDR4_A6") (class "Default")
      (node (ref "IC30") (pin "AC24") (pinfunction "D1_MA06_AC24") (pintype "passive"))
      (node (ref "IC51") (pin "L2") (pinfunction "A6_L2") (pintype "passive"))
      (node (ref "IC52") (pin "L2") (pinfunction "A6_L2") (pintype "passive"))
      (node (ref "IC53") (pin "L2") (pinfunction "A6_L2") (pintype "passive"))
      (node (ref "IC54") (pin "L2") (pinfunction "A6_L2") (pintype "passive"))
      (node (ref "IC55") (pin "L2") (pinfunction "A6_L2") (pintype "passive"))
      (node (ref "IC56") (pin "L2") (pinfunction "A6_L2") (pintype "passive"))
      (node (ref "IC57") (pin "L2") (pinfunction "A6_L2") (pintype "passive"))
      (node (ref "IC58") (pin "L2") (pinfunction "A6_L2") (pintype "passive"))
      (node (ref "R471") (pin "1") (pinfunction "1_1") (pintype "passive"))
    )
    (net (code "12") (name "/PR_DDR4_A7") (class "Default")
      (node (ref "IC30") (pin "U24") (pinfunction "D1_MA07_U24") (pintype "passive"))
      (node (ref "IC51") (pin "M8") (pinfunction "A7_M8") (pintype "passive"))
      (node (ref "IC52") (pin "M8") (pinfunction "A7_M8") (pintype "passive"))
      (node (ref "IC53") (pin "M8") (pinfunction "A7_M8") (pintype "passive"))
      (node (ref "IC54") (pin "M8") (pinfunction "A7_M8") (pintype "passive"))
      (node (ref "IC55") (pin "M8") (pinfunction "A7_M8") (pintype "passive"))
      (node (ref "IC56") (pin "M8") (pinfunction "A7_M8") (pintype "passive"))
      (node (ref "IC57") (pin "M8") (pinfunction "A7_M8") (pintype "passive"))
      (node (ref "IC58") (pin "M8") (pinfunction "A7_M8") (pintype "passive"))
      (node (ref "R472") (pin "1") (pinfunction "1_1") (pintype "passive"))
    )
    (net (code "13") (name "/PR_DDR4_A8") (class "Default")
      (node (ref "IC30") (pin "R22") (pinfunction "D1_MA08_R22") (pintype "passive"))
      (node (ref "IC51") (pin "M2") (pinfunction "A8_M2") (pintype "passive"))
      (node (ref "IC52") (pin "M2") (pinfunction "A8_M2") (pintype "passive"))
      (node (ref "IC53") (pin "M2") (pinfunction "A8_M2") (pintype "passive"))
      (node (ref "IC54") (pin "M2") (pinfunction "A8_M2") (pintype "passive"))
      (node (ref "IC55") (pin "M2") (pinfunction "A8_M2") (pintype "passive"))
      (node (ref "IC56") (pin "M2") (pinfunction "A8_M2") (pintype "passive"))
      (node (ref "IC57") (pin "M2") (pinfunction "A8_M2") (pintype "passive"))
      (node (ref "IC58") (pin "M2") (pinfunction "A8_M2") (pintype "passive"))
      (node (ref "R473") (pin "1") (pinfunction "1_1") (pintype "passive"))
    )
    (net (code "14") (name "/PR_DDR4_A9") (class "Default")
      (node (ref "IC30") (pin "W22") (pinfunction "D1_MA09_W22") (pintype "passive"))
      (node (ref "IC51") (pin "M7") (pinfunction "A9_M7") (pintype "passive"))
      (node (ref "IC52") (pin "M7") (pinfunction "A9_M7") (pintype "passive"))
      (node (ref "IC53") (pin "M7") (pinfunction "A9_M7") (pintype "passive"))
      (node (ref "IC54") (pin "M7") (pinfunction "A9_M7") (pintype "passive"))
      (node (ref "IC55") (pin "M7") (pinfunction "A9_M7") (pintype "passive"))
      (node (ref "IC56") (pin "M7") (pinfunction "A9_M7") (pintype "passive"))
      (node (ref "IC57") (pin "M7") (pinfunction "A9_M7") (pintype "passive"))
      (node (ref "IC58") (pin "M7") (pinfunction "A9_M7") (pintype "passive"))
      (node (ref "R474") (pin "1") (pinfunction "1_1") (pintype "passive"))
    )
    (net (code "15") (name "/PR_DDR4_A10") (class "Default")
      (node (ref "IC30") (pin "AB23") (pinfunction "D1_MA10_AB23") (pintype "passive"))
      (node (ref "IC51") (pin "J3") (pinfunction "A10/AP_J3") (pintype "passive"))
      (node (ref "IC52") (pin "J3") (pinfunction "A10/AP_J3") (pintype "passive"))
      (node (ref "IC53") (pin "J3") (pinfunction "A10/AP_J3") (pintype "passive"))
      (node (ref "IC54") (pin "J3") (pinfunction "A10/AP_J3") (pintype "passive"))
      (node (ref "IC55") (pin "J3") (pinfunction "A10/AP_J3") (pintype "passive"))
      (node (ref "IC56") (pin "J3") (pinfunction "A10/AP_J3") (pintype "passive"))
      (node (ref "IC57") (pin "J3") (pinfunction "A10/AP_J3") (pintype "passive"))
      (node (ref "IC58") (pin "J3") (pinfunction "A10/AP_J3") (pintype "passive"))
      (node (ref "R475") (pin "1") (pinfunction "1_1") (pintype "passive"))
    )
    (net (code "16") (name "/PR_DDR4_A11") (class "Default")
      (node (ref "IC30") (pin "T23") (pinfunction "D1_MA11_T23") (pintype "passive"))
      (node (ref "IC51") (pin "N2") (pinfunction "A11_N2") (pintype "passive"))
      (node (ref "IC52") (pin "N2") (pinfunction "A11_N2") (pintype "passive"))
      (node (ref "IC53") (pin "N2") (pinfunction "A11_N2") (pintype "passive"))
      (node (ref "IC54") (pin "N2") (pinfunction "A11_N2") (pintype "passive"))
      (node (ref "IC55") (pin "N2") (pinfunction "A11_N2") (pintype "passive"))
      (node (ref "IC56") (pin "N2") (pinfunction "A11_N2") (pintype "passive"))
      (node (ref "IC57") (pin "N2") (pinfunction "A11_N2") (pintype "passive"))
      (node (ref "IC58") (pin "N2") (pinfunction "A11_N2") (pintype "passive"))
      (node (ref "R476") (pin "1") (pinfunction "1_1") (pintype "passive"))
    )
    (net (code "17") (name "/PR_DDR4_A12") (class "Default")
      (node (ref "IC30") (pin "AC23") (pinfunction "D1_MA12_AC23") (pintype "passive"))
      (node (ref "IC51") (pin "J7") (pinfunction "A12/~{BC}_J7") (pintype "passive"))
      (node (ref "IC52") (pin "J7") (pinfunction "A12/~{BC}_J7") (pintype "passive"))
      (node (ref "IC53") (pin "J7") (pinfunction "A12/~{BC}_J7") (pintype "passive"))
      (node (ref "IC54") (pin "J7") (pinfunction "A12/~{BC}_J7") (pintype "passive"))
      (node (ref "IC55") (pin "J7") (pinfunction "A12/~{BC}_J7") (pintype "passive"))
      (node (ref "IC56") (pin "J7") (pinfunction "A12/~{BC}_J7") (pintype "passive"))
      (node (ref "IC57") (pin "J7") (pinfunction "A12/~{BC}_J7") (pintype "passive"))
      (node (ref "IC58") (pin "J7") (pinfunction "A12/~{BC}_J7") (pintype "passive"))
      (node (ref "R477") (pin "1") (pinfunction "1_1") (pintype "passive"))
    )
    (net (code "18") (name "/PR_DDR4_A13") (class "Default")
      (node (ref "IC30") (pin "T25") (pinfunction "D1_MA13_T25") (pintype "passive"))
      (node (ref "IC51") (pin "N8") (pinfunction "A13_N8") (pintype "passive"))
      (node (ref "IC52") (pin "N8") (pinfunction "A13_N8") (pintype "passive"))
      (node (ref "IC53") (pin "N8") (pinfunction "A13_N8") (pintype "passive"))
      (node (ref "IC54") (pin "N8") (pinfunction "A13_N8") (pintype "passive"))
      (node (ref "IC55") (pin "N8") (pinfunction "A13_N8") (pintype "passive"))
      (node (ref "IC56") (pin "N8") (pinfunction "A13_N8") (pintype "passive"))
      (node (ref "IC57") (pin "N8") (pinfunction "A13_N8") (pintype "passive"))
      (node (ref "IC58") (pin "N8") (pinfunction "A13_N8") (pintype "passive"))
    )
    (net (code "19") (name "/PR_DDR4_A14") (class "Default")
      (node (ref "IC30") (pin "AE22") (pinfunction "D1_MA14_AE22") (pintype "passive"))
      (node (ref "IC51") (pin "J8") (pinfunction "BG1_J8") (pintype "passive"))
      (node (ref "IC52") (pin "J8") (pinfunction "BG1_J8") (pintype "passive"))
      (node (ref "IC53") (pin "J8") (pinfunction "BG1_J8") (pintype "passive"))
      (node (ref "IC54") (pin "J8") (pinfunction "BG1_J8") (pintype "passive"))
      (node (ref "IC55") (pin "J8") (pinfunction "BG1_J8") (pintype "passive"))
      (node (ref "IC56") (pin "J8") (pinfunction "BG1_J8") (pintype "passive"))
      (node (ref "IC57") (pin "J8") (pinfunction "BG1_J8") (pintype "passive"))
      (node (ref "IC58") (pin "J8") (pinfunction "BG1_J8") (pintype "passive"))
      (node (ref "R478") (pin "1") (pinfunction "1_1") (pintype "passive"))
      (node (ref "R479") (pin "1") (pinfunction "1_1") (pintype "passive"))
    )
    (net (code "20") (name "/PR_DDR4_A15") (class "Default")
      (node (ref "IC30") (pin "U21") (pinfunction "D1_MA15_U21") (pintype "passive"))
      (node (ref "IC51") (pin "H3") (pinfunction "~{ACT}_H3") (pintype "passive"))
      (node (ref "IC52") (pin "H3") (pinfunction "~{ACT}_H3") (pintype "passive"))
      (node (ref "IC53") (pin "H3") (pinfunction "~{ACT}_H3") (pintype "passive"))
      (node (ref "IC54") (pin "H3") (pinfunction "~{ACT}_H3") (pintype "passive"))
      (node (ref "IC55") (pin "H3") (pinfunction "~{ACT}_H3") (pintype "passive"))
      (node (ref "IC56") (pin "H3") (pinfunction "~{ACT}_H3") (pintype "passive"))
      (node (ref "IC57") (pin "H3") (pinfunction "~{ACT}_H3") (pintype "passive"))
      (node (ref "IC58") (pin "H3") (pinfunction "~{ACT}_H3") (pintype "passive"))
      (node (ref "R480") (pin "1") (pinfunction "1_1") (pintype "passive"))
    )
    (net (code "21") (name "/PR_DDR4_ARAS_B") (class "Default")
      (node (ref "IC30") (pin "AB25") (pinfunction "D1_MRAS#_AB25") (pintype "passive"))
    )
    (net (code "22") (name "/PR_DDR4_BA0") (class "Default")
      (node (ref "IC30") (pin "AC21") (pinfunction "D1_MBA0_AC21") (pintype "passive"))
      (node (ref "IC51") (pin "K2") (pinfunction "BA0_K2") (pintype "passive"))
      (node (ref "IC52") (pin "K2") (pinfunction "BA0_K2") (pintype "passive"))
      (node (ref "IC53") (pin "K2") (pinfunction "BA0_K2") (pintype "passive"))
      (node (ref "IC54") (pin "K2") (pinfunction "BA0_K2") (pintype "passive"))
      (node (ref "IC55") (pin "K2") (pinfunction "BA0_K2") (pintype "passive"))
      (node (ref "IC56") (pin "K2") (pinfunction "BA0_K2") (pintype "passive"))
      (node (ref "IC57") (pin "K2") (pinfunction "BA0_K2") (pintype "passive"))
      (node (ref "IC58") (pin "K2") (pinfunction "BA0_K2") (pintype "passive"))
      (node (ref "R462") (pin "1") (pinfunction "1_1") (pintype "passive"))
    )
    (net (code "23") (name "/PR_DDR4_BA1") (class "Default")
      (node (ref "IC30") (pin "Y23") (pinfunction "D1_MBA1_Y23") (pintype "passive"))
      (node (ref "IC51") (pin "K8") (pinfunction "BA1_K8") (pintype "passive"))
      (node (ref "IC52") (pin "K8") (pinfunction "BA1_K8") (pintype "passive"))
      (node (ref "IC53") (pin "K8") (pinfunction "BA1_K8") (pintype "passive"))
      (node (ref "IC54") (pin "K8") (pinfunction "BA1_K8") (pintype "passive"))
      (node (ref "IC55") (pin "K8") (pinfunction "BA1_K8") (pintype "passive"))
      (node (ref "IC56") (pin "K8") (pinfunction "BA1_K8") (pintype "passive"))
      (node (ref "IC57") (pin "K8") (pinfunction "BA1_K8") (pintype "passive"))
      (node (ref "IC58") (pin "K8") (pinfunction "BA1_K8") (pintype "passive"))
      (node (ref "R463") (pin "1") (pinfunction "1_1") (pintype "passive"))
    )
    (net (code "24") (name "/PR_DDR4_BA2") (class "Default")
      (node (ref "IC51") (pin "J2") (pinfunction "BG0_J2") (pintype "passive"))
      (node (ref "IC52") (pin "J2") (pinfunction "BG0_J2") (pintype "passive"))
      (node (ref "IC53") (pin "J2") (pinfunction "BG0_J2") (pintype "passive"))
      (node (ref "IC54") (pin "J2") (pinfunction "BG0_J2") (pintype "passive"))
      (node (ref "IC55") (pin "J2") (pinfunction "BG0_J2") (pintype "passive"))
      (node (ref "IC56") (pin "J2") (pinfunction "BG0_J2") (pintype "passive"))
      (node (ref "IC57") (pin "J2") (pinfunction "BG0_J2") (pintype "passive"))
      (node (ref "IC58") (pin "J2") (pinfunction "BG0_J2") (pintype "passive"))
      (node (ref "R464") (pin "1") (pinfunction "1_1") (pintype "passive"))
    )
    (net (code "26") (name "/PR_DDR4_CAS_B") (class "Default")
      (node (ref "IC30") (pin "AC22") (pinfunction "D1_MCAS#_AC22") (pintype "passive"))
      (node (ref "IC51") (pin "H7") (pinfunction "~{CAS}/A15_H7") (pintype "passive"))
      (node (ref "IC52") (pin "H7") (pinfunction "~{CAS}/A15_H7") (pintype "passive"))
      (node (ref "IC53") (pin "H7") (pinfunction "~{CAS}/A15_H7") (pintype "passive"))
      (node (ref "IC54") (pin "H7") (pinfunction "~{CAS}/A15_H7") (pintype "passive"))
      (node (ref "IC55") (pin "H7") (pinfunction "~{CAS}/A15_H7") (pintype "passive"))
      (node (ref "IC56") (pin "H7") (pinfunction "~{CAS}/A15_H7") (pintype "passive"))
      (node (ref "IC57") (pin "H7") (pinfunction "~{CAS}/A15_H7") (pintype "passive"))
      (node (ref "IC58") (pin "H7") (pinfunction "~{CAS}/A15_H7") (pintype "passive"))
      (node (ref "R482") (pin "1") (pinfunction "1_1") (pintype "passive"))
    )
    (net (code "27") (name "/PR_DDR4_CKE0") (class "Default")
      (node (ref "IC30") (pin "W21") (pinfunction "D1_MCKE0_W21") (pintype "passive"))
      (node (ref "IC51") (pin "G3") (pinfunction "CKE_G3") (pintype "passive"))
      (node (ref "IC52") (pin "G3") (pinfunction "CKE_G3") (pintype "passive"))
      (node (ref "IC53") (pin "G3") (pinfunction "CKE_G3") (pintype "passive"))
      (node (ref "IC54") (pin "G3") (pinfunction "CKE_G3") (pintype "passive"))
      (node (ref "IC55") (pin "G3") (pinfunction "CKE_G3") (pintype "passive"))
      (node (ref "IC56") (pin "G3") (pinfunction "CKE_G3") (pintype "passive"))
      (node (ref "IC57") (pin "G3") (pinfunction "CKE_G3") (pintype "passive"))
      (node (ref "IC58") (pin "G3") (pinfunction "CKE_G3") (pintype "passive"))
      (node (ref "R485") (pin "1") (pinfunction "1_1") (pintype "passive"))
    )
    (net (code "28") (name "/PR_DDR4_CKE1") (class "Default")
      (node (ref "IC30") (pin "AB21") (pinfunction "D1_MCKE1_AB21") (pintype "passive"))
      (node (ref "IC51") (pin "G2") (pinfunction "C0/CKE1_G2") (pintype "passive"))
      (node (ref "IC52") (pin "G2") (pinfunction "C0/CKE1_G2") (pintype "passive"))
      (node (ref "IC53") (pin "G2") (pinfunction "C0/CKE1_G2") (pintype "passive"))
      (node (ref "IC54") (pin "G2") (pinfunction "C0/CKE1_G2") (pintype "passive"))
      (node (ref "IC55") (pin "G2") (pinfunction "C0/CKE1_G2") (pintype "passive"))
      (node (ref "IC56") (pin "G2") (pinfunction "C0/CKE1_G2") (pintype "passive"))
      (node (ref "IC57") (pin "G2") (pinfunction "C0/CKE1_G2") (pintype "passive"))
      (node (ref "IC58") (pin "G2") (pinfunction "C0/CKE1_G2") (pintype "passive"))
      (node (ref "R488") (pin "1") (pinfunction "1_1") (pintype "passive"))
    )
    (net (code "29") (name "/PR_DDR4_CLK") (class "Default")
      (node (ref "IC30") (pin "AA24") (pinfunction "D1_MCK0_AA24") (pintype "passive"))
      (node (ref "IC51") (pin "F7") (pinfunction "CK_T_F7") (pintype "passive"))
      (node (ref "IC52") (pin "F7") (pinfunction "CK_T_F7") (pintype "passive"))
      (node (ref "IC53") (pin "F7") (pinfunction "CK_T_F7") (pintype "passive"))
      (node (ref "IC54") (pin "F7") (pinfunction "CK_T_F7") (pintype "passive"))
      (node (ref "IC55") (pin "F7") (pinfunction "CK_T_F7") (pintype "passive"))
      (node (ref "IC56") (pin "F7") (pinfunction "CK_T_F7") (pintype "passive"))
      (node (ref "IC57") (pin "F7") (pinfunction "CK_T_F7") (pintype "passive"))
      (node (ref "IC58") (pin "F7") (pinfunction "CK_T_F7") (pintype "passive"))
      (node (ref "R442") (pin "1") (pinfunction "1_1") (pintype "passive"))
      (node (ref "R455") (pin "1") (pinfunction "1_1") (pintype "passive"))
    )
    (net (code "30") (name "/PR_DDR4_CLK_B") (class "Default")
      (node (ref "IC30") (pin "AA25") (pinfunction "D1_MCK0#_AA25") (pintype "passive"))
      (node (ref "IC51") (pin "F8") (pinfunction "CK_C_F8") (pintype "passive"))
      (node (ref "IC52") (pin "F8") (pinfunction "CK_C_F8") (pintype "passive"))
      (node (ref "IC53") (pin "F8") (pinfunction "CK_C_F8") (pintype "passive"))
      (node (ref "IC54") (pin "F8") (pinfunction "CK_C_F8") (pintype "passive"))
      (node (ref "IC55") (pin "F8") (pinfunction "CK_C_F8") (pintype "passive"))
      (node (ref "IC56") (pin "F8") (pinfunction "CK_C_F8") (pintype "passive"))
      (node (ref "IC57") (pin "F8") (pinfunction "CK_C_F8") (pintype "passive"))
      (node (ref "IC58") (pin "F8") (pinfunction "CK_C_F8") (pintype "passive"))
      (node (ref "R443") (pin "1") (pinfunction "1_1") (pintype "passive"))
      (node (ref "R456") (pin "1") (pinfunction "1_1") (pintype "passive"))
    )
    (net (code "31") (name "/PR_DDR4_CS0_B") (class "Default")
      (node (ref "IC30") (pin "U23") (pinfunction "D1_MCS0#_U23") (pintype "passive"))
      (node (ref "IC51") (pin "G7") (pinfunction "~{CS}_G7") (pintype "passive"))
      (node (ref "IC52") (pin "G7") (pinfunction "~{CS}_G7") (pintype "passive"))
      (node (ref "IC53") (pin "G7") (pinfunction "~{CS}_G7") (pintype "passive"))
      (node (ref "IC54") (pin "G7") (pinfunction "~{CS}_G7") (pintype "passive"))
      (node (ref "IC55") (pin "G7") (pinfunction "~{CS}_G7") (pintype "passive"))
      (node (ref "IC56") (pin "G7") (pinfunction "~{CS}_G7") (pintype "passive"))
      (node (ref "IC57") (pin "G7") (pinfunction "~{CS}_G7") (pintype "passive"))
      (node (ref "IC58") (pin "G7") (pinfunction "~{CS}_G7") (pintype "passive"))
      (node (ref "R484") (pin "1") (pinfunction "1_1") (pintype "passive"))
    )
    (net (code "32") (name "/PR_DDR4_CS1_B") (class "Default")
      (node (ref "IC30") (pin "V21") (pinfunction "D1_MCS1#_V21") (pintype "passive"))
      (node (ref "IC51") (pin "G8") (pinfunction "C1/~{CS1}_G8") (pintype "passive"))
      (node (ref "IC52") (pin "G8") (pinfunction "C1/~{CS1}_G8") (pintype "passive"))
      (node (ref "IC53") (pin "G8") (pinfunction "C1/~{CS1}_G8") (pintype "passive"))
      (node (ref "IC54") (pin "G8") (pinfunction "C1/~{CS1}_G8") (pintype "passive"))
      (node (ref "IC55") (pin "G8") (pinfunction "C1/~{CS1}_G8") (pintype "passive"))
      (node (ref "IC56") (pin "G8") (pinfunction "C1/~{CS1}_G8") (pintype "passive"))
      (node (ref "IC57") (pin "G8") (pinfunction "C1/~{CS1}_G8") (pintype "passive"))
      (node (ref "IC58") (pin "G8") (pinfunction "C1/~{CS1}_G8") (pintype "passive"))
      (node (ref "R487") (pin "1") (pinfunction "1_1") (pintype "passive"))
    )
    (net (code "33") (name "/PR_DDR4_DM0_B") (class "Default")
      (node (ref "IC51") (pin "A7") (pinfunction "NF/~{DM}/~{DBI}/TDQS_T_A7") (pintype "passive"))
      (node (ref "IC52") (pin "A7") (pinfunction "NF/~{DM}/~{DBI}/TDQS_T_A7") (pintype "passive"))
      (node (ref "IC53") (pin "A7") (pinfunction "NF/~{DM}/~{DBI}/TDQS_T_A7") (pintype "passive"))
      (node (ref "IC54") (pin "A7") (pinfunction "NF/~{DM}/~{DBI}/TDQS_T_A7") (pintype "passive"))
      (node (ref "IC55") (pin "A7") (pinfunction "NF/~{DM}/~{DBI}/TDQS_T_A7") (pintype "passive"))
      (node (ref "IC56") (pin "A7") (pinfunction "NF/~{DM}/~{DBI}/TDQS_T_A7") (pintype "passive"))
      (node (ref "IC57") (pin "A7") (pinfunction "NF/~{DM}/~{DBI}/TDQS_T_A7") (pintype "passive"))
      (node (ref "IC58") (pin "A7") (pinfunction "NF/~{DM}/~{DBI}/TDQS_T_A7") (pintype "passive"))
    )
    (net (code "37") (name "/PR_DDR4_DM8_B") (class "Default")
      (node (ref "IC30") (pin "B22") (pinfunction "D1_MDM8_B22") (pintype "passive"))
    )
    (net (code "38") (name "/PR_DDR4_DQ0") (class "Default")
      (node (ref "IC30") (pin "N24") (pinfunction "D1_MDQ02_N24") (pintype "passive"))
      (node (ref "IC51") (pin "C2") (pinfunction "DQ0_C2") (pintype "passive"))
      (node (ref "IC52") (pin "C2") (pinfunction "DQ0_C2") (pintype "passive"))
      (node (ref "IC53") (pin "C2") (pinfunction "DQ0_C2") (pintype "passive"))
      (node (ref "IC54") (pin "C2") (pinfunction "DQ0_C2") (pintype "passive"))
      (node (ref "IC55") (pin "C2") (pinfunction "DQ0_C2") (pintype "passive"))
      (node (ref "IC56") (pin "C2") (pinfunction "DQ0_C2") (pintype "passive"))
      (node (ref "IC57") (pin "C2") (pinfunction "DQ0_C2") (pintype "passive"))
      (node (ref "IC58") (pin "C2") (pinfunction "DQ0_C2") (pintype "passive"))
    )
    (net (code "39") (name "/PR_DDR4_DQ1") (class "Default")
      (node (ref "IC30") (pin "K24") (pinfunction "D1_MDQ01_K24") (pintype "passive"))
      (node (ref "IC51") (pin "B7") (pinfunction "DQ1_B7") (pintype "passive"))
      (node (ref "IC52") (pin "B7") (pinfunction "DQ1_B7") (pintype "passive"))
      (node (ref "IC53") (pin "B7") (pinfunction "DQ1_B7") (pintype "passive"))
      (node (ref "IC54") (pin "B7") (pinfunction "DQ1_B7") (pintype "passive"))
      (node (ref "IC55") (pin "B7") (pinfunction "DQ1_B7") (pintype "passive"))
      (node (ref "IC56") (pin "B7") (pinfunction "DQ1_B7") (pintype "passive"))
      (node (ref "IC57") (pin "B7") (pinfunction "DQ1_B7") (pintype "passive"))
      (node (ref "IC58") (pin "B7") (pinfunction "DQ1_B7") (pintype "passive"))
    )
    (net (code "40") (name "/PR_DDR4_DQ2") (class "Default")
      (node (ref "IC30") (pin "R24") (pinfunction "D1_MDQ03_R24") (pintype "passive"))
      (node (ref "IC51") (pin "D3") (pinfunction "DQ2_D3") (pintype "passive"))
      (node (ref "IC52") (pin "D3") (pinfunction "DQ2_D3") (pintype "passive"))
      (node (ref "IC53") (pin "D3") (pinfunction "DQ2_D3") (pintype "passive"))
      (node (ref "IC54") (pin "D3") (pinfunction "DQ2_D3") (pintype "passive"))
      (node (ref "IC55") (pin "D3") (pinfunction "DQ2_D3") (pintype "passive"))
      (node (ref "IC56") (pin "D3") (pinfunction "DQ2_D3") (pintype "passive"))
      (node (ref "IC57") (pin "D3") (pinfunction "DQ2_D3") (pintype "passive"))
      (node (ref "IC58") (pin "D3") (pinfunction "DQ2_D3") (pintype "passive"))
    )
    (net (code "41") (name "/PR_DDR4_DQ3") (class "Default")
      (node (ref "IC30") (pin "J25") (pinfunction "D1_MDQ00_J25") (pintype "passive"))
      (node (ref "IC51") (pin "D7") (pinfunction "DQ3_D7") (pintype "passive"))
      (node (ref "IC52") (pin "D7") (pinfunction "DQ3_D7") (pintype "passive"))
      (node (ref "IC53") (pin "D7") (pinfunction "DQ3_D7") (pintype "passive"))
      (node (ref "IC54") (pin "D7") (pinfunction "DQ3_D7") (pintype "passive"))
      (node (ref "IC55") (pin "D7") (pinfunction "DQ3_D7") (pintype "passive"))
      (node (ref "IC56") (pin "D7") (pinfunction "DQ3_D7") (pintype "passive"))
      (node (ref "IC57") (pin "D7") (pinfunction "DQ3_D7") (pintype "passive"))
      (node (ref "IC58") (pin "D7") (pinfunction "DQ3_D7") (pintype "passive"))
    )
    (net (code "42") (name "/PR_DDR4_DQ4") (class "Default")
      (node (ref "IC30") (pin "P25") (pinfunction "D1_MDQ07_P25") (pintype "passive"))
      (node (ref "IC51") (pin "D2") (pinfunction "DQ4/NC_D2") (pintype "passive"))
      (node (ref "IC52") (pin "D2") (pinfunction "DQ4/NC_D2") (pintype "passive"))
      (node (ref "IC53") (pin "D2") (pinfunction "DQ4/NC_D2") (pintype "passive"))
      (node (ref "IC54") (pin "D2") (pinfunction "DQ4/NC_D2") (pintype "passive"))
      (node (ref "IC55") (pin "D2") (pinfunction "DQ4/NC_D2") (pintype "passive"))
      (node (ref "IC56") (pin "D2") (pinfunction "DQ4/NC_D2") (pintype "passive"))
      (node (ref "IC57") (pin "D2") (pinfunction "DQ4/NC_D2") (pintype "passive"))
      (node (ref "IC58") (pin "D2") (pinfunction "DQ4/NC_D2") (pintype "passive"))
    )
    (net (code "43") (name "/PR_DDR4_DQ5") (class "Default")
      (node (ref "IC30") (pin "K25") (pinfunction "D1_MDQ05_K25") (pintype "passive"))
      (node (ref "IC51") (pin "D8") (pinfunction "DQ5/NC_D8") (pintype "passive"))
      (node (ref "IC52") (pin "D8") (pinfunction "DQ5/NC_D8") (pintype "passive"))
      (node (ref "IC53") (pin "D8") (pinfunction "DQ5/NC_D8") (pintype "passive"))
      (node (ref "IC54") (pin "D8") (pinfunction "DQ5/NC_D8") (pintype "passive"))
      (node (ref "IC55") (pin "D8") (pinfunction "DQ5/NC_D8") (pintype "passive"))
      (node (ref "IC56") (pin "D8") (pinfunction "DQ5/NC_D8") (pintype "passive"))
      (node (ref "IC57") (pin "D8") (pinfunction "DQ5/NC_D8") (pintype "passive"))
      (node (ref "IC58") (pin "D8") (pinfunction "DQ5/NC_D8") (pintype "passive"))
    )
    (net (code "44") (name "/PR_DDR4_DQ6") (class "Default")
      (node (ref "IC30") (pin "N25") (pinfunction "D1_MDQ06_N25") (pintype "passive"))
      (node (ref "IC51") (pin "E3") (pinfunction "DQ6/NC_E3") (pintype "passive"))
      (node (ref "IC52") (pin "E3") (pinfunction "DQ6/NC_E3") (pintype "passive"))
      (node (ref "IC53") (pin "E3") (pinfunction "DQ6/NC_E3") (pintype "passive"))
      (node (ref "IC54") (pin "E3") (pinfunction "DQ6/NC_E3") (pintype "passive"))
      (node (ref "IC55") (pin "E3") (pinfunction "DQ6/NC_E3") (pintype "passive"))
      (node (ref "IC56") (pin "E3") (pinfunction "DQ6/NC_E3") (pintype "passive"))
      (node (ref "IC57") (pin "E3") (pinfunction "DQ6/NC_E3") (pintype "passive"))
      (node (ref "IC58") (pin "E3") (pinfunction "DQ6/NC_E3") (pintype "passive"))
    )
    (net (code "45") (name "/PR_DDR4_DQ7") (class "Default")
      (node (ref "IC30") (pin "H24") (pinfunction "D1_MDQ04_H24") (pintype "passive"))
      (node (ref "IC51") (pin "E7") (pinfunction "DQ7/NC_E7") (pintype "passive"))
      (node (ref "IC52") (pin "E7") (pinfunction "DQ7/NC_E7") (pintype "passive"))
      (node (ref "IC53") (pin "E7") (pinfunction "DQ7/NC_E7") (pintype "passive"))
      (node (ref "IC54") (pin "E7") (pinfunction "DQ7/NC_E7") (pintype "passive"))
      (node (ref "IC55") (pin "E7") (pinfunction "DQ7/NC_E7") (pintype "passive"))
      (node (ref "IC56") (pin "E7") (pinfunction "DQ7/NC_E7") (pintype "passive"))
      (node (ref "IC57") (pin "E7") (pinfunction "DQ7/NC_E7") (pintype "passive"))
      (node (ref "IC58") (pin "E7") (pinfunction "DQ7/NC_E7") (pintype "passive"))
    )
    (net (code "46") (name "/PR_DDR4_DQ8") (class "Default")
      (node (ref "IC30") (pin "N21") (pinfunction "D1_MDQ10_N21") (pintype "passive"))
    )
    (net (code "47") (name "/PR_DDR4_DQ9") (class "Default")
      (node (ref "IC30") (pin "M23") (pinfunction "D1_MDQ09_M23") (pintype "passive"))
    )
    (net (code "48") (name "/PR_DDR4_DQ10") (class "Default")
      (node (ref "IC30") (pin "P21") (pinfunction "D1_MDQ11_P21") (pintype "passive"))
    )
    (net (code "49") (name "/PR_DDR4_DQ11") (class "Default")
      (node (ref "IC30") (pin "L23") (pinfunction "D1_MDQ08_L23") (pintype "passive"))
    )
    (net (code "50") (name "/PR_DDR4_DQ12") (class "Default")
      (node (ref "IC30") (pin "M21") (pinfunction "D1_MDQ14_M21") (pintype "passive"))
    )
    (net (code "51") (name "/PR_DDR4_DQ13") (class "Default")
      (node (ref "IC30") (pin "L22") (pinfunction "D1_MDQ13_L22") (pintype "passive"))
    )
    (net (code "52") (name "/PR_DDR4_DQ14") (class "Default")
      (node (ref "IC30") (pin "P23") (pinfunction "D1_MDQ15_P23") (pintype "passive"))
    )
    (net (code "53") (name "/PR_DDR4_DQ15") (class "Default")
      (node (ref "IC30") (pin "K21") (pinfunction "D1_MDQ12_K21") (pintype "passive"))
    )
    (net (code "54") (name "/PR_DDR4_DQ16") (class "Default")
      (node (ref "IC30") (pin "F24") (pinfunction "D1_MDQ18_F24") (pintype "passive"))
    )
    (net (code "55") (name "/PR_DDR4_DQ17") (class "Default")
      (node (ref "IC30") (pin "C25") (pinfunction "D1_MDQ17_C25") (pintype "passive"))
    )
    (net (code "56") (name "/PR_DDR4_DQ18") (class "Default")
      (node (ref "IC30") (pin "H25") (pinfunction "D1_MDQ19_H25") (pintype "passive"))
    )
    (net (code "57") (name "/PR_DDR4_DQ19") (class "Default")
      (node (ref "IC30") (pin "C24") (pinfunction "D1_MDQ16_C24") (pintype "passive"))
    )
    (net (code "58") (name "/PR_DDR4_DQ20") (class "Default")
      (node (ref "IC30") (pin "G25") (pinfunction "D1_MDQ23_G25") (pintype "passive"))
    )
    (net (code "59") (name "/PR_DDR4_DQ21") (class "Default")
      (node (ref "IC30") (pin "D24") (pinfunction "D1_MDQ21_D24") (pintype "passive"))
    )
    (net (code "60") (name "/PR_DDR4_DQ22") (class "Default")
      (node (ref "IC30") (pin "F25") (pinfunction "D1_MDQ22_F25") (pintype "passive"))
    )
    (net (code "61") (name "/PR_DDR4_DQ23") (class "Default")
      (node (ref "IC30") (pin "B24") (pinfunction "D1_MDQ20_B24") (pintype "passive"))
    )
    (net (code "62") (name "/PR_DDR4_DQ24") (class "Default")
      (node (ref "IC30") (pin "K23") (pinfunction "D1_MDQ27_K23") (pintype "passive"))
    )
    (net (code "63") (name "/PR_DDR4_DQ25") (class "Default")
      (node (ref "IC30") (pin "H21") (pinfunction "D1_MDQ25_H21") (pintype "passive"))
    )
    (net (code "64") (name "/PR_DDR4_DQ26") (class "Default")
      (node (ref "IC30") (pin "J23") (pinfunction "D1_MDQ26_J23") (pintype "passive"))
    )
    (net (code "65") (name "/PR_DDR4_DQ27") (class "Default")
      (node (ref "IC30") (pin "F22") (pinfunction "D1_MDQ24_F22") (pintype "passive"))
    )
    (net (code "66") (name "/PR_DDR4_DQ28") (class "Default")
      (node (ref "IC30") (pin "J22") (pinfunction "D1_MDQ31_J22") (pintype "passive"))
    )
    (net (code "67") (name "/PR_DDR4_DQ29") (class "Default")
      (node (ref "IC30") (pin "F23") (pinfunction "D1_MDQ29_F23") (pintype "passive"))
    )
    (net (code "68") (name "/PR_DDR4_DQ30") (class "Default")
      (node (ref "IC30") (pin "J21") (pinfunction "D1_MDQ30_J21") (pintype "passive"))
    )
    (net (code "69") (name "/PR_DDR4_DQ31") (class "Default")
      (node (ref "IC30") (pin "G21") (pinfunction "D1_MDQ28_G21") (pintype "passive"))
    )
    (net (code "70") (name "/PR_DDR4_DQS0") (class "Default")
      (node (ref "IC30") (pin "M24") (pinfunction "D1_MDQS0_M24") (pintype "passive"))
      (node (ref "IC51") (pin "C3") (pinfunction "DQS_T_C3") (pintype "passive"))
      (node (ref "IC52") (pin "C3") (pinfunction "DQS_T_C3") (pintype "passive"))
      (node (ref "IC53") (pin "C3") (pinfunction "DQS_T_C3") (pintype "passive"))
      (node (ref "IC54") (pin "C3") (pinfunction "DQS_T_C3") (pintype "passive"))
      (node (ref "IC55") (pin "C3") (pinfunction "DQS_T_C3") (pintype "passive"))
      (node (ref "IC56") (pin "C3") (pinfunction "DQS_T_C3") (pintype "passive"))
      (node (ref "IC57") (pin "C3") (pinfunction "DQS_T_C3") (pintype "passive"))
      (node (ref "IC58") (pin "C3") (pinfunction "DQS_T_C3") (pintype "passive"))
    )
    (net (code "71") (name "/PR_DDR4_DQS0_B") (class "Default")
      (node (ref "IC51") (pin "B3") (pinfunction "DQS_S_B3") (pintype "passive"))
      (node (ref "IC52") (pin "B3") (pinfunction "DQS_S_B3") (pintype "passive"))
      (node (ref "IC53") (pin "B3") (pinfunction "DQS_S_B3") (pintype "passive"))
      (node (ref "IC54") (pin "B3") (pinfunction "DQS_S_B3") (pintype "passive"))
      (node (ref "IC55") (pin "B3") (pinfunction "DQS_S_B3") (pintype "passive"))
      (node (ref "IC56") (pin "B3") (pinfunction "DQS_S_B3") (pintype "passive"))
      (node (ref "IC57") (pin "B3") (pinfunction "DQS_S_B3") (pintype "passive"))
      (node (ref "IC58") (pin "B3") (pinfunction "DQS_S_B3") (pintype "passive"))
    )
    (net (code "72") (name "/PR_DDR4_DQS1") (class "Default")
      (node (ref "IC30") (pin "N22") (pinfunction "D1_MDQS1_N22") (pintype "passive"))
    )
    (net (code "73") (name "/PR_DDR4_DQS1_B") (class "Default")
      (node (ref "IC30") (pin "N23") (pinfunction "D1_MDQS1#_N23") (pintype "passive"))
    )
    (net (code "75") (name "/PR_DDR4_DQS2_B") (class "Default")
      (node (ref "IC30") (pin "D25") (pinfunction "D1_MDQS2#_D25") (pintype "passive"))
    )
    (net (code "76") (name "/PR_DDR4_DQS3") (class "Default")
      (node (ref "IC30") (pin "H23") (pinfunction "D1_MDQS3_H23") (pintype "passive"))
    )
    (net (code "77") (name "/PR_DDR4_DQS3_B") (class "Default")
      (node (ref "IC30") (pin "H22") (pinfunction "D1_MDQS3#_H22") (pintype "passive"))
    )
    (net (code "78") (name "/PR_DDR4_DQS8") (class "Default")
      (node (ref "IC30") (pin "B23") (pinfunction "D1_MDQS8_B23") (pintype "passive"))
    )
    (net (code "79") (name "/PR_DDR4_DQS8_B") (class "Default")
      (node (ref "IC30") (pin "A23") (pinfunction "D1_MDQS8#_A23") (pintype "passive"))
    )
    (net (code "80") (name "/PR_DDR4_MECC0") (class "Default")
      (node (ref "IC30") (pin "C22") (pinfunction "D1_MECC0_C22") (pintype "passive"))
    )
    (net (code "81") (name "/PR_DDR4_MECC1") (class "Default")
      (node (ref "IC30") (pin "A22") (pinfunction "D1_MECC1_A22") (pintype "passive"))
    )
    (net (code "82") (name "/PR_DDR4_MECC2") (class "Default")
      (node (ref "IC30") (pin "D22") (pinfunction "D1_MECC2_D22") (pintype "passive"))
    )
    (net (code "83") (name "/PR_DDR4_MECC3") (class "Default")
      (node (ref "IC30") (pin "D23") (pinfunction "D1_MECC3_D23") (pintype "passive"))
    )
    (net (code "84") (name "/PR_DDR4_OD1") (class "Default")
      (node (ref "IC30") (pin "T21") (pinfunction "D1_MODT1_T21") (pintype "passive"))
    )
    (net (code "85") (name "/PR_DDR4_ODT0") (class "Default")
      (node (ref "IC30") (pin "U22") (pinfunction "D1_MODT0_U22") (pintype "passive"))
      (node (ref "IC51") (pin "F3") (pinfunction "ODT_F3") (pintype "passive"))
      (node (ref "IC52") (pin "F3") (pinfunction "ODT_F3") (pintype "passive"))
      (node (ref "IC53") (pin "F3") (pinfunction "ODT_F3") (pintype "passive"))
      (node (ref "IC54") (pin "F3") (pinfunction "ODT_F3") (pintype "passive"))
      (node (ref "IC55") (pin "F3") (pinfunction "ODT_F3") (pintype "passive"))
      (node (ref "IC56") (pin "F3") (pinfunction "ODT_F3") (pintype "passive"))
      (node (ref "IC57") (pin "F3") (pinfunction "ODT_F3") (pintype "passive"))
      (node (ref "IC58") (pin "F3") (pinfunction "ODT_F3") (pintype "passive"))
      (node (ref "R486") (pin "1") (pinfunction "1_1") (pintype "passive"))
    )
    (net (code "86") (name "/PR_DDR4_ODT1") (class "Default")
      (node (ref "IC51") (pin "F2") (pinfunction "ODT1_F2") (pintype "passive"))
      (node (ref "IC52") (pin "F2") (pinfunction "ODT1_F2") (pintype "passive"))
      (node (ref "IC53") (pin "F2") (pinfunction "ODT1_F2") (pintype "passive"))
      (node (ref "IC54") (pin "F2") (pinfunction "ODT1_F2") (pintype "passive"))
      (node (ref "IC55") (pin "F2") (pinfunction "ODT1_F2") (pintype "passive"))
      (node (ref "IC56") (pin "F2") (pinfunction "ODT1_F2") (pintype "passive"))
      (node (ref "IC57") (pin "F2") (pinfunction "ODT1_F2") (pintype "passive"))
      (node (ref "IC58") (pin "F2") (pinfunction "ODT1_F2") (pintype "passive"))
      (node (ref "R489") (pin "1") (pinfunction "1_1") (pintype "passive"))
    )
    (net (code "87") (name "/PR_DDR4_PAR") (class "Default")
      (node (ref "IC51") (pin "N3") (pinfunction "PAR_N3") (pintype "passive"))
      (node (ref "IC52") (pin "N3") (pinfunction "PAR_N3") (pintype "passive"))
      (node (ref "IC53") (pin "N3") (pinfunction "PAR_N3") (pintype "passive"))
      (node (ref "IC54") (pin "N3") (pinfunction "PAR_N3") (pintype "passive"))
      (node (ref "IC55") (pin "N3") (pinfunction "PAR_N3") (pintype "passive"))
      (node (ref "IC56") (pin "N3") (pinfunction "PAR_N3") (pintype "passive"))
      (node (ref "IC57") (pin "N3") (pinfunction "PAR_N3") (pintype "passive"))
      (node (ref "IC58") (pin "N3") (pinfunction "PAR_N3") (pintype "passive"))
      (node (ref "R490") (pin "1") (pinfunction "1_1") (pintype "passive"))
    )
    (net (code "88") (name "/PR_DDR4_RAS_B") (class "Default")
      (node (ref "IC51") (pin "H8") (pinfunction "~{RAS}/A16/NC_H8") (pintype "passive"))
      (node (ref "IC52") (pin "H8") (pinfunction "~{RAS}/A16/NC_H8") (pintype "passive"))
      (node (ref "IC53") (pin "H8") (pinfunction "~{RAS}/A16/NC_H8") (pintype "passive"))
      (node (ref "IC54") (pin "H8") (pinfunction "~{RAS}/A16/NC_H8") (pintype "passive"))
      (node (ref "IC55") (pin "H8") (pinfunction "~{RAS}/A16/NC_H8") (pintype "passive"))
      (node (ref "IC56") (pin "H8") (pinfunction "~{RAS}/A16/NC_H8") (pintype "passive"))
      (node (ref "IC57") (pin "H8") (pinfunction "~{RAS}/A16/NC_H8") (pintype "passive"))
      (node (ref "IC58") (pin "H8") (pinfunction "~{RAS}/A16/NC_H8") (pintype "passive"))
      (node (ref "R481") (pin "1") (pinfunction "1_1") (pintype "passive"))
    )
    (net (code "89") (name "/PR_DDR4_RST_B") (class "Default")
      (node (ref "IC51") (pin "L1") (pinfunction "~{RESET}_L1") (pintype "passive"))
      (node (ref "IC52") (pin "L1") (pinfunction "~{RESET}_L1") (pintype "passive"))
      (node (ref "IC53") (pin "L1") (pinfunction "~{RESET}_L1") (pintype "passive"))
      (node (ref "IC54") (pin "L1") (pinfunction "~{RESET}_L1") (pintype "passive"))
      (node (ref "IC55") (pin "L1") (pinfunction "~{RESET}_L1") (pintype "passive"))
      (node (ref "IC56") (pin "L1") (pinfunction "~{RESET}_L1") (pintype "passive"))
      (node (ref "IC57") (pin "L1") (pinfunction "~{RESET}_L1") (pintype "passive"))
      (node (ref "IC58") (pin "L1") (pinfunction "~{RESET}_L1") (pintype "passive"))
    )
    (net (code "90") (name "/PR_DDR4_TEN") (class "Default")
      (node (ref "IC51") (pin "G9") (pinfunction "RUF/TEN_G9") (pintype "passive"))
      (node (ref "IC52") (pin "G9") (pinfunction "RUF/TEN_G9") (pintype "passive"))
      (node (ref "IC53") (pin "G9") (pinfunction "RUF/TEN_G9") (pintype "passive"))
      (node (ref "IC54") (pin "G9") (pinfunction "RUF/TEN_G9") (pintype "passive"))
      (node (ref "IC55") (pin "G9") (pinfunction "RUF/TEN_G9") (pintype "passive"))
      (node (ref "IC56") (pin "G9") (pinfunction "RUF/TEN_G9") (pintype "passive"))
      (node (ref "IC57") (pin "G9") (pinfunction "RUF/TEN_G9") (pintype "passive"))
      (node (ref "IC58") (pin "G9") (pinfunction "RUF/TEN_G9") (pintype "passive"))
      (node (ref "R454") (pin "1") (pinfunction "1_1") (pintype "passive"))
    )
    (net (code "91") (name "/PR_DDR4_WE_B") (class "Default")
      (node (ref "IC51") (pin "H2") (pinfunction "~{WE}/A14_H2") (pintype "passive"))
      (node (ref "IC52") (pin "H2") (pinfunction "~{WE}/A14_H2") (pintype "passive"))
      (node (ref "IC53") (pin "H2") (pinfunction "~{WE}/A14_H2") (pintype "passive"))
      (node (ref "IC54") (pin "H2") (pinfunction "~{WE}/A14_H2") (pintype "passive"))
      (node (ref "IC55") (pin "H2") (pinfunction "~{WE}/A14_H2") (pintype "passive"))
      (node (ref "IC56") (pin "H2") (pinfunction "~{WE}/A14_H2") (pintype "passive"))
      (node (ref "IC57") (pin "H2") (pinfunction "~{WE}/A14_H2") (pintype "passive"))
      (node (ref "IC58") (pin "H2") (pinfunction "~{WE}/A14_H2") (pintype "passive"))
      (node (ref "R483") (pin "1") (pinfunction "1_1") (pintype "passive"))
    )
    (net (code "92") (name "/PR_DDR4_ZQ_0") (class "Default")
      (node (ref "IC51") (pin "B9") (pinfunction "ZQ_B9") (pintype "passive"))
      (node (ref "IC52") (pin "B9") (pinfunction "ZQ_B9") (pintype "passive"))
      (node (ref "IC53") (pin "B9") (pinfunction "ZQ_B9") (pintype "passive"))
      (node (ref "IC54") (pin "B9") (pinfunction "ZQ_B9") (pintype "passive"))
      (node (ref "IC55") (pin "B9") (pinfunction "ZQ_B9") (pintype "passive"))
      (node (ref "IC56") (pin "B9") (pinfunction "ZQ_B9") (pintype "passive"))
      (node (ref "IC57") (pin "B9") (pinfunction "ZQ_B9") (pintype "passive"))
      (node (ref "IC58") (pin "B9") (pinfunction "ZQ_B9") (pintype "passive"))
      (node (ref "R444") (pin "2") (pinfunction "2_2") (pintype "passive"))
      (node (ref "R445") (pin "2") (pinfunction "2_2") (pintype "passive"))
      (node (ref "R446") (pin "2") (pinfunction "2_2") (pintype "passive"))
      (node (ref "R447") (pin "2") (pinfunction "2_2") (pintype "passive"))
      (node (ref "R457") (pin "2") (pinfunction "2_2") (pintype "passive"))
      (node (ref "R458") (pin "2") (pinfunction "2_2") (pintype "passive"))
      (node (ref "R460") (pin "2") (pinfunction "2_2") (pintype "passive"))
      (node (ref "R461") (pin "2") (pinfunction "2_2") (pintype "passive"))
    )
    (net (code "93") (name "/PR_DDR_RST_B") (class "Default")
      (node (ref "R453") (pin "2") (pinfunction "2_2") (pintype "passive"))
    )
    (net (code "94") (name "/PU_I2C1_SCL") (class "Default")
      (node (ref "IC59") (pin "6") (pinfunction "SCL_6") (pintype "passive"))
    )
    (net (code "95") (name "/PU_I2C1_SDA") (class "Default")
      (node (ref "IC59") (pin "5") (pinfunction "SDA_5") (pintype "passive"))
    )
    (net (code "96") (name "/P_ALERT_N") (class "Default")
      (node (ref "R451") (pin "2") (pinfunction "2_2") (pintype "passive"))
    )
    (net (code "97") (name "/P_DDR4_PAR") (class "Default")
      (node (ref "IC30") (pin "U25") (pinfunction "D1_MAPAR_OUT_U25") (pintype "passive"))
    )
    (net (code "98") (name "DDR_VREF") (class "Default")
      (node (ref "C725") (pin "2") (pinfunction "2_2") (pintype "passive"))
      (node (ref "C726") (pin "2") (pinfunction "2_2") (pintype "passive"))
      (node (ref "C727") (pin "2") (pinfunction "2_2") (pintype "passive"))
      (node (ref "C728") (pin "2") (pinfunction "2_2") (pintype "passive"))
      (node (ref "C729") (pin "2") (pinfunction "2_2") (pintype "passive"))
      (node (ref "C730") (pin "2") (pinfunction "2_2") (pintype "passive"))
      (node (ref "C731") (pin "2") (pinfunction "2_2") (pintype "passive"))
      (node (ref "C732") (pin "2") (pinfunction "2_2") (pintype "passive"))
      (node (ref "C743") (pin "2") (pinfunction "2_2") (pintype "passive"))
      (node (ref "C744") (pin "2") (pinfunction "2_2") (pintype "passive"))
      (node (ref "C745") (pin "2") (pinfunction "2_2") (pintype "passive"))
      (node (ref "C746") (pin "2") (pinfunction "2_2") (pintype "passive"))
      (node (ref "C747") (pin "2") (pinfunction "2_2") (pintype "passive"))
      (node (ref "C748") (pin "2") (pinfunction "2_2") (pintype "passive"))
      (node (ref "C749") (pin "2") (pinfunction "2_2") (pintype "passive"))
      (node (ref "C750") (pin "2") (pinfunction "2_2") (pintype "passive"))
      (node (ref "IC51") (pin "J1") (pinfunction "VREFCA_J1") (pintype "passive"))
      (node (ref "IC52") (pin "J1") (pinfunction "VREFCA_J1") (pintype "passive"))
      (node (ref "IC53") (pin "J1") (pinfunction "VREFCA_J1") (pintype "passive"))
      (node (ref "IC54") (pin "J1") (pinfunction "VREFCA_J1") (pintype "passive"))
      (node (ref "IC55") (pin "J1") (pinfunction "VREFCA_J1") (pintype "passive"))
      (node (ref "IC56") (pin "J1") (pinfunction "VREFCA_J1") (pintype "passive"))
      (node (ref "IC57") (pin "J1") (pinfunction "VREFCA_J1") (pintype "passive"))
      (node (ref "IC58") (pin "J1") (pinfunction "VREFCA_J1") (pintype "passive"))
    )
    (net (code "99") (name "DDR_VTT") (class "Default")
      (node (ref "C791") (pin "2") (pinfunction "2_2") (pintype "passive"))
      (node (ref "C792") (pin "2") (pinfunction "2_2") (pintype "passive"))
      (node (ref "C793") (pin "2") (pinfunction "2_2") (pintype "passive"))
      (node (ref "C794") (pin "2") (pinfunction "2_2") (pintype "passive"))
      (node (ref "C795") (pin "2") (pinfunction "2_2") (pintype "passive"))
      (node (ref "C796") (pin "2") (pinfunction "2_2") (pintype "passive"))
      (node (ref "C817") (pin "2") (pinfunction "2_2") (pintype "passive"))
      (node (ref "C818") (pin "2") (pinfunction "2_2") (pintype "passive"))
      (node (ref "C819") (pin "2") (pinfunction "2_2") (pintype "passive"))
      (node (ref "C820") (pin "2") (pinfunction "2_2") (pintype "passive"))
      (node (ref "C821") (pin "2") (pinfunction "2_2") (pintype "passive"))
      (node (ref "C822") (pin "2") (pinfunction "2_2") (pintype "passive"))
      (node (ref "C843") (pin "2") (pinfunction "2_2") (pintype "passive"))
      (node (ref "C844") (pin "2") (pinfunction "2_2") (pintype "passive"))
      (node (ref "C845") (pin "2") (pinfunction "2_2") (pintype "passive"))
      (node (ref "C846") (pin "2") (pinfunction "2_2") (pintype "passive"))
      (node (ref "C847") (pin "1") (pinfunction "1_1") (pintype "passive"))
      (node (ref "C848") (pin "1") (pinfunction "1_1") (pintype "passive"))
      (node (ref "R462") (pin "2") (pinfunction "2_2") (pintype "passive"))
      (node (ref "R463") (pin "2") (pinfunction "2_2") (pintype "passive"))
      (node (ref "R464") (pin "2") (pinfunction "2_2") (pintype "passive"))
      (node (ref "R465") (pin "2") (pinfunction "2_2") (pintype "passive"))
      (node (ref "R466") (pin "2") (pinfunction "2_2") (pintype "passive"))
      (node (ref "R467") (pin "2") (pinfunction "2_2") (pintype "passive"))
      (node (ref "R468") (pin "2") (pinfunction "2_2") (pintype "passive"))
      (node (ref "R469") (pin "2") (pinfunction "2_2") (pintype "passive"))
      (node (ref "R470") (pin "2") (pinfunction "2_2") (pintype "passive"))
      (node (ref "R471") (pin "2") (pinfunction "2_2") (pintype "passive"))
      (node (ref "R472") (pin "2") (pinfunction "2_2") (pintype "passive"))
      (node (ref "R473") (pin "2") (pinfunction "2_2") (pintype "passive"))
      (node (ref "R474") (pin "2") (pinfunction "2_2") (pintype "passive"))
      (node (ref "R475") (pin "2") (pinfunction "2_2") (pintype "passive"))
      (node (ref "R476") (pin "2") (pinfunction "2_2") (pintype "passive"))
      (node (ref "R477") (pin "2") (pinfunction "2_2") (pintype "passive"))
      (node (ref "R478") (pin "2") (pinfunction "2_2") (pintype "passive"))
      (node (ref "R479") (pin "2") (pinfunction "2_2") (pintype "passive"))
      (node (ref "R480") (pin "2") (pinfunction "2_2") (pintype "passive"))
      (node (ref "R481") (pin "2") (pinfunction "2_2") (pintype "passive"))
      (node (ref "R482") (pin "2") (pinfunction "2_2") (pintype "passive"))
      (node (ref "R483") (pin "2") (pinfunction "2_2") (pintype "passive"))
      (node (ref "R484") (pin "2") (pinfunction "2_2") (pintype "passive"))
      (node (ref "R485") (pin "2") (pinfunction "2_2") (pintype "passive"))
      (node (ref "R486") (pin "2") (pinfunction "2_2") (pintype "passive"))
      (node (ref "R487") (pin "2") (pinfunction "2_2") (pintype "passive"))
      (node (ref "R488") (pin "2") (pinfunction "2_2") (pintype "passive"))
      (node (ref "R489") (pin "2") (pinfunction "2_2") (pintype "passive"))
      (node (ref "R490") (pin "2") (pinfunction "2_2") (pintype "passive"))
    )
    (net (code "100") (name "GND") (class "Default")
      (node (ref "C716") (pin "2") (pinfunction "2_2") (pintype "passive"))
      (node (ref "C717") (pin "2") (pinfunction "2_2") (pintype "passive"))
      (node (ref "C718") (pin "2") (pinfunction "2_2") (pintype "passive"))
      (node (ref "C719") (pin "2") (pinfunction "2_2") (pintype "passive"))
      (node (ref "C720") (pin "2") (pinfunction "2_2") (pintype "passive"))
      (node (ref "C721") (pin "2") (pinfunction "2_2") (pintype "passive"))
      (node (ref "C722") (pin "2") (pinfunction "2_2") (pintype "passive"))
      (node (ref "C723") (pin "2") (pinfunction "2_2") (pintype "passive"))
      (node (ref "C724") (pin "2") (pinfunction "2_2") (pintype "passive"))
      (node (ref "C725") (pin "1") (pinfunction "1_1") (pintype "passive"))
      (node (ref "C726") (pin "1") (pinfunction "1_1") (pintype "passive"))
      (node (ref "C727") (pin "1") (pinfunction "1_1") (pintype "passive"))
      (node (ref "C728") (pin "1") (pinfunction "1_1") (pintype "passive"))
      (node (ref "C729") (pin "1") (pinfunction "1_1") (pintype "passive"))
      (node (ref "C730") (pin "1") (pinfunction "1_1") (pintype "passive"))
      (node (ref "C731") (pin "1") (pinfunction "1_1") (pintype "passive"))
      (node (ref "C732") (pin "1") (pinfunction "1_1") (pintype "passive"))
      (node (ref "C733") (pin "2") (pinfunction "2_2") (pintype "passive"))
      (node (ref "C734") (pin "2") (pinfunction "2_2") (pintype "passive"))
      (node (ref "C735") (pin "2") (pinfunction "2_2") (pintype "passive"))
      (node (ref "C736") (pin "2") (pinfunction "2_2") (pintype "passive"))
      (node (ref "C737") (pin "2") (pinfunction "2_2") (pintype "passive"))
      (node (ref "C738") (pin "2") (pinfunction "2_2") (pintype "passive"))
      (node (ref "C739") (pin "2") (pinfunction "2_2") (pintype "passive"))
      (node (ref "C740") (pin "2") (pinfunction "2_2") (pintype "passive"))
      (node (ref "C741") (pin "2") (pinfunction "2_2") (pintype "passive"))
      (node (ref "C742") (pin "2") (pinfunction "2_2") (pintype "passive"))
      (node (ref "C743") (pin "1") (pinfunction "1_1") (pintype "passive"))
      (node (ref "C744") (pin "1") (pinfunction "1_1") (pintype "passive"))
      (node (ref "C745") (pin "1") (pinfunction "1_1") (pintype "passive"))
      (node (ref "C746") (pin "1") (pinfunction "1_1") (pintype "passive"))
      (node (ref "C747") (pin "1") (pinfunction "1_1") (pintype "passive"))
      (node (ref "C748") (pin "1") (pinfunction "1_1") (pintype "passive"))
      (node (ref "C749") (pin "1") (pinfunction "1_1") (pintype "passive"))
      (node (ref "C750") (pin "1") (pinfunction "1_1") (pintype "passive"))
      (node (ref "C751") (pin "1") (pinfunction "1_1") (pintype "passive"))
      (node (ref "C752") (pin "1") (pinfunction "1_1") (pintype "passive"))
      (node (ref "C753") (pin "1") (pinfunction "1_1") (pintype "passive"))
      (node (ref "C754") (pin "1") (pinfunction "1_1") (pintype "passive"))
      (node (ref "C755") (pin "1") (pinfunction "1_1") (pintype "passive"))
      (node (ref "C756") (pin "1") (pinfunction "1_1") (pintype "passive"))
      (node (ref "C757") (pin "1") (pinfunction "1_1") (pintype "passive"))
      (node (ref "C758") (pin "1") (pinfunction "1_1") (pintype "passive"))
      (node (ref "C759") (pin "2") (pinfunction "2_2") (pintype "passive"))
      (node (ref "C760") (pin "2") (pinfunction "2_2") (pintype "passive"))
      (node (ref "C761") (pin "1") (pinfunction "1_1") (pintype "passive"))
      (node (ref "C762") (pin "1") (pinfunction "1_1") (pintype "passive"))
      (node (ref "C763") (pin "1") (pinfunction "1_1") (pintype "passive"))
      (node (ref "C764") (pin "1") (pinfunction "1_1") (pintype "passive"))
      (node (ref "C765") (pin "1") (pinfunction "1_1") (pintype "passive"))
      (node (ref "C766") (pin "1") (pinfunction "1_1") (pintype "passive"))
      (node (ref "C767") (pin "1") (pinfunction "1_1") (pintype "passive"))
      (node (ref "C768") (pin "1") (pinfunction "1_1") (pintype "passive"))
      (node (ref "C769") (pin "2") (pinfunction "2_2") (pintype "passive"))
      (node (ref "C770") (pin "2") (pinfunction "2_2") (pintype "passive"))
      (node (ref "C771") (pin "1") (pinfunction "1_1") (pintype "passive"))
      (node (ref "C772") (pin "1") (pinfunction "1_1") (pintype "passive"))
      (node (ref "C773") (pin "1") (pinfunction "1_1") (pintype "passive"))
      (node (ref "C774") (pin "1") (pinfunction "1_1") (pintype "passive"))
      (node (ref "C775") (pin "1") (pinfunction "1_1") (pintype "passive"))
      (node (ref "C776") (pin "1") (pinfunction "1_1") (pintype "passive"))
      (node (ref "C777") (pin "1") (pinfunction "1_1") (pintype "passive"))
      (node (ref "C778") (pin "1") (pinfunction "1_1") (pintype "passive"))
      (node (ref "C779") (pin "2") (pinfunction "2_2") (pintype "passive"))
      (node (ref "C780") (pin "2") (pinfunction "2_2") (pintype "passive"))
      (node (ref "C781") (pin "1") (pinfunction "1_1") (pintype "passive"))
      (node (ref "C782") (pin "1") (pinfunction "1_1") (pintype "passive"))
      (node (ref "C783") (pin "1") (pinfunction "1_1") (pintype "passive"))
      (node (ref "C784") (pin "1") (pinfunction "1_1") (pintype "passive"))
      (node (ref "C785") (pin "1") (pinfunction "1_1") (pintype "passive"))
      (node (ref "C786") (pin "1") (pinfunction "1_1") (pintype "passive"))
      (node (ref "C787") (pin "1") (pinfunction "1_1") (pintype "passive"))
      (node (ref "C788") (pin "1") (pinfunction "1_1") (pintype "passive"))
      (node (ref "C789") (pin "2") (pinfunction "2_2") (pintype "passive"))
      (node (ref "C790") (pin "2") (pinfunction "2_2") (pintype "passive"))
      (node (ref "C791") (pin "1") (pinfunction "1_1") (pintype "passive"))
      (node (ref "C792") (pin "1") (pinfunction "1_1") (pintype "passive"))
      (node (ref "C793") (pin "1") (pinfunction "1_1") (pintype "passive"))
      (node (ref "C794") (pin "1") (pinfunction "1_1") (pintype "passive"))
      (node (ref "C795") (pin "1") (pinfunction "1_1") (pintype "passive"))
      (node (ref "C796") (pin "1") (pinfunction "1_1") (pintype "passive"))
      (node (ref "C797") (pin "1") (pinfunction "1_1") (pintype "passive"))
      (node (ref "C798") (pin "1") (pinfunction "1_1") (pintype "passive"))
      (node (ref "C799") (pin "1") (pinfunction "1_1") (pintype "passive"))
      (node (ref "C800") (pin "1") (pinfunction "1_1") (pintype "passive"))
      (node (ref "C801") (pin "1") (pinfunction "1_1") (pintype "passive"))
      (node (ref "C802") (pin "1") (pinfunction "1_1") (pintype "passive"))
      (node (ref "C803") (pin "1") (pinfunction "1_1") (pintype "passive"))
      (node (ref "C804") (pin "1") (pinfunction "1_1") (pintype "passive"))
      (node (ref "C805") (pin "2") (pinfunction "2_2") (pintype "passive"))
      (node (ref "C806") (pin "2") (pinfunction "2_2") (pintype "passive"))
      (node (ref "C807") (pin "1") (pinfunction "1_1") (pintype "passive"))
      (node (ref "C808") (pin "1") (pinfunction "1_1") (pintype "passive"))
      (node (ref "C809") (pin "1") (pinfunction "1_1") (pintype "passive"))
      (node (ref "C810") (pin "1") (pinfunction "1_1") (pintype "passive"))
      (node (ref "C811") (pin "1") (pinfunction "1_1") (pintype "passive"))
      (node (ref "C812") (pin "1") (pinfunction "1_1") (pintype "passive"))
      (node (ref "C813") (pin "1") (pinfunction "1_1") (pintype "passive"))
      (node (ref "C814") (pin "1") (pinfunction "1_1") (pintype "passive"))
      (node (ref "C815") (pin "2") (pinfunction "2_2") (pintype "passive"))
      (node (ref "C816") (pin "2") (pinfunction "2_2") (pintype "passive"))
      (node (ref "C817") (pin "1") (pinfunction "1_1") (pintype "passive"))
      (node (ref "C818") (pin "1") (pinfunction "1_1") (pintype "passive"))
      (node (ref "C819") (pin "1") (pinfunction "1_1") (pintype "passive"))
      (node (ref "C820") (pin "1") (pinfunction "1_1") (pintype "passive"))
      (node (ref "C821") (pin "1") (pinfunction "1_1") (pintype "passive"))
      (node (ref "C822") (pin "1") (pinfunction "1_1") (pintype "passive"))
      (node (ref "C823") (pin "1") (pinfunction "1_1") (pintype "passive"))
      (node (ref "C824") (pin "1") (pinfunction "1_1") (pintype "passive"))
      (node (ref "C825") (pin "1") (pinfunction "1_1") (pintype "passive"))
      (node (ref "C826") (pin "1") (pinfunction "1_1") (pintype "passive"))
      (node (ref "C827") (pin "1") (pinfunction "1_1") (pintype "passive"))
      (node (ref "C828") (pin "1") (pinfunction "1_1") (pintype "passive"))
      (node (ref "C829") (pin "1") (pinfunction "1_1") (pintype "passive"))
      (node (ref "C830") (pin "1") (pinfunction "1_1") (pintype "passive"))
      (node (ref "C831") (pin "2") (pinfunction "2_2") (pintype "passive"))
      (node (ref "C832") (pin "2") (pinfunction "2_2") (pintype "passive"))
      (node (ref "C833") (pin "1") (pinfunction "1_1") (pintype "passive"))
      (node (ref "C834") (pin "1") (pinfunction "1_1") (pintype "passive"))
      (node (ref "C835") (pin "1") (pinfunction "1_1") (pintype "passive"))
      (node (ref "C836") (pin "1") (pinfunction "1_1") (pintype "passive"))
      (node (ref "C837") (pin "1") (pinfunction "1_1") (pintype "passive"))
      (node (ref "C838") (pin "1") (pinfunction "1_1") (pintype "passive"))
      (node (ref "C839") (pin "1") (pinfunction "1_1") (pintype "passive"))
      (node (ref "C840") (pin "1") (pinfunction "1_1") (pintype "passive"))
      (node (ref "C841") (pin "2") (pinfunction "2_2") (pintype "passive"))
      (node (ref "C842") (pin "2") (pinfunction "2_2") (pintype "passive"))
      (node (ref "C843") (pin "1") (pinfunction "1_1") (pintype "passive"))
      (node (ref "C844") (pin "1") (pinfunction "1_1") (pintype "passive"))
      (node (ref "C845") (pin "1") (pinfunction "1_1") (pintype "passive"))
      (node (ref "C846") (pin "1") (pinfunction "1_1") (pintype "passive"))
      (node (ref "C847") (pin "2") (pinfunction "2_2") (pintype "passive"))
      (node (ref "C848") (pin "2") (pinfunction "2_2") (pintype "passive"))
      (node (ref "IC30") (pin "W24") (pinfunction "D1_MCK1_W24") (pintype "passive"))
      (node (ref "IC30") (pin "W25") (pinfunction "D1_MCK1#_W25") (pintype "passive"))
      (node (ref "IC51") (pin "A2") (pinfunction "VSSQ1_A2") (pintype "passive"))
      (node (ref "IC51") (pin "A8") (pinfunction "VSSQ2_A8") (pintype "passive"))
      (node (ref "IC51") (pin "A9") (pinfunction "VSS1_A9") (pintype "passive"))
      (node (ref "IC51") (pin "C8") (pinfunction "VSS2_C8") (pintype "passive"))
      (node (ref "IC51") (pin "D1") (pinfunction "VSSQ3_D1") (pintype "passive"))
      (node (ref "IC51") (pin "D9") (pinfunction "VSSQ4_D9") (pintype "passive"))
      (node (ref "IC51") (pin "E1") (pinfunction "VSS3_E1") (pintype "passive"))
      (node (ref "IC51") (pin "E9") (pinfunction "VSS4_E9") (pintype "passive"))
      (node (ref "IC51") (pin "G1") (pinfunction "VSS5_G1") (pintype "passive"))
      (node (ref "IC51") (pin "H9") (pinfunction "VSS6_H9") (pintype "passive"))
      (node (ref "IC51") (pin "K1") (pinfunction "VSS7_K1") (pintype "passive"))
      (node (ref "IC51") (pin "K9") (pinfunction "VSS8_K9") (pintype "passive"))
      (node (ref "IC51") (pin "N1") (pinfunction "VSS9_N1") (pintype "passive"))
      (node (ref "IC52") (pin "A2") (pinfunction "VSSQ1_A2") (pintype "passive"))
      (node (ref "IC52") (pin "A8") (pinfunction "VSSQ2_A8") (pintype "passive"))
      (node (ref "IC52") (pin "A9") (pinfunction "VSS1_A9") (pintype "passive"))
      (node (ref "IC52") (pin "C8") (pinfunction "VSS2_C8") (pintype "passive"))
      (node (ref "IC52") (pin "D1") (pinfunction "VSSQ3_D1") (pintype "passive"))
      (node (ref "IC52") (pin "D9") (pinfunction "VSSQ4_D9") (pintype "passive"))
      (node (ref "IC52") (pin "E1") (pinfunction "VSS3_E1") (pintype "passive"))
      (node (ref "IC52") (pin "E9") (pinfunction "VSS4_E9") (pintype "passive"))
      (node (ref "IC52") (pin "G1") (pinfunction "VSS5_G1") (pintype "passive"))
      (node (ref "IC52") (pin "H9") (pinfunction "VSS6_H9") (pintype "passive"))
      (node (ref "IC52") (pin "K1") (pinfunction "VSS7_K1") (pintype "passive"))
      (node (ref "IC52") (pin "K9") (pinfunction "VSS8_K9") (pintype "passive"))
      (node (ref "IC52") (pin "N1") (pinfunction "VSS9_N1") (pintype "passive"))
      (node (ref "IC53") (pin "A2") (pinfunction "VSSQ1_A2") (pintype "passive"))
      (node (ref "IC53") (pin "A8") (pinfunction "VSSQ2_A8") (pintype "passive"))
      (node (ref "IC53") (pin "A9") (pinfunction "VSS1_A9") (pintype "passive"))
      (node (ref "IC53") (pin "C8") (pinfunction "VSS2_C8") (pintype "passive"))
      (node (ref "IC53") (pin "D1") (pinfunction "VSSQ3_D1") (pintype "passive"))
      (node (ref "IC53") (pin "D9") (pinfunction "VSSQ4_D9") (pintype "passive"))
      (node (ref "IC53") (pin "E1") (pinfunction "VSS3_E1") (pintype "passive"))
      (node (ref "IC53") (pin "E9") (pinfunction "VSS4_E9") (pintype "passive"))
      (node (ref "IC53") (pin "G1") (pinfunction "VSS5_G1") (pintype "passive"))
      (node (ref "IC53") (pin "H9") (pinfunction "VSS6_H9") (pintype "passive"))
      (node (ref "IC53") (pin "K1") (pinfunction "VSS7_K1") (pintype "passive"))
      (node (ref "IC53") (pin "K9") (pinfunction "VSS8_K9") (pintype "passive"))
      (node (ref "IC53") (pin "N1") (pinfunction "VSS9_N1") (pintype "passive"))
      (node (ref "IC54") (pin "A2") (pinfunction "VSSQ1_A2") (pintype "passive"))
      (node (ref "IC54") (pin "A8") (pinfunction "VSSQ2_A8") (pintype "passive"))
      (node (ref "IC54") (pin "A9") (pinfunction "VSS1_A9") (pintype "passive"))
      (node (ref "IC54") (pin "C8") (pinfunction "VSS2_C8") (pintype "passive"))
      (node (ref "IC54") (pin "D1") (pinfunction "VSSQ3_D1") (pintype "passive"))
      (node (ref "IC54") (pin "D9") (pinfunction "VSSQ4_D9") (pintype "passive"))
      (node (ref "IC54") (pin "E1") (pinfunction "VSS3_E1") (pintype "passive"))
      (node (ref "IC54") (pin "E9") (pinfunction "VSS4_E9") (pintype "passive"))
      (node (ref "IC54") (pin "G1") (pinfunction "VSS5_G1") (pintype "passive"))
      (node (ref "IC54") (pin "H9") (pinfunction "VSS6_H9") (pintype "passive"))
      (node (ref "IC54") (pin "K1") (pinfunction "VSS7_K1") (pintype "passive"))
      (node (ref "IC54") (pin "K9") (pinfunction "VSS8_K9") (pintype "passive"))
      (node (ref "IC54") (pin "N1") (pinfunction "VSS9_N1") (pintype "passive"))
      (node (ref "IC55") (pin "A2") (pinfunction "VSSQ1_A2") (pintype "passive"))
      (node (ref "IC55") (pin "A8") (pinfunction "VSSQ2_A8") (pintype "passive"))
      (node (ref "IC55") (pin "A9") (pinfunction "VSS1_A9") (pintype "passive"))
      (node (ref "IC55") (pin "C8") (pinfunction "VSS2_C8") (pintype "passive"))
      (node (ref "IC55") (pin "D1") (pinfunction "VSSQ3_D1") (pintype "passive"))
      (node (ref "IC55") (pin "D9") (pinfunction "VSSQ4_D9") (pintype "passive"))
      (node (ref "IC55") (pin "E1") (pinfunction "VSS3_E1") (pintype "passive"))
      (node (ref "IC55") (pin "E9") (pinfunction "VSS4_E9") (pintype "passive"))
      (node (ref "IC55") (pin "G1") (pinfunction "VSS5_G1") (pintype "passive"))
      (node (ref "IC55") (pin "H9") (pinfunction "VSS6_H9") (pintype "passive"))
      (node (ref "IC55") (pin "K1") (pinfunction "VSS7_K1") (pintype "passive"))
      (node (ref "IC55") (pin "K9") (pinfunction "VSS8_K9") (pintype "passive"))
      (node (ref "IC55") (pin "N1") (pinfunction "VSS9_N1") (pintype "passive"))
      (node (ref "IC56") (pin "A2") (pinfunction "VSSQ1_A2") (pintype "passive"))
      (node (ref "IC56") (pin "A8") (pinfunction "VSSQ2_A8") (pintype "passive"))
      (node (ref "IC56") (pin "A9") (pinfunction "VSS1_A9") (pintype "passive"))
      (node (ref "IC56") (pin "C8") (pinfunction "VSS2_C8") (pintype "passive"))
      (node (ref "IC56") (pin "D1") (pinfunction "VSSQ3_D1") (pintype "passive"))
      (node (ref "IC56") (pin "D9") (pinfunction "VSSQ4_D9") (pintype "passive"))
      (node (ref "IC56") (pin "E1") (pinfunction "VSS3_E1") (pintype "passive"))
      (node (ref "IC56") (pin "E9") (pinfunction "VSS4_E9") (pintype "passive"))
      (node (ref "IC56") (pin "G1") (pinfunction "VSS5_G1") (pintype "passive"))
      (node (ref "IC56") (pin "H9") (pinfunction "VSS6_H9") (pintype "passive"))
      (node (ref "IC56") (pin "K1") (pinfunction "VSS7_K1") (pintype "passive"))
      (node (ref "IC56") (pin "K9") (pinfunction "VSS8_K9") (pintype "passive"))
      (node (ref "IC56") (pin "N1") (pinfunction "VSS9_N1") (pintype "passive"))
      (node (ref "IC57") (pin "A2") (pinfunction "VSSQ1_A2") (pintype "passive"))
      (node (ref "IC57") (pin "A8") (pinfunction "VSSQ2_A8") (pintype "passive"))
      (node (ref "IC57") (pin "A9") (pinfunction "VSS1_A9") (pintype "passive"))
      (node (ref "IC57") (pin "C8") (pinfunction "VSS2_C8") (pintype "passive"))
      (node (ref "IC57") (pin "D1") (pinfunction "VSSQ3_D1") (pintype "passive"))
      (node (ref "IC57") (pin "D9") (pinfunction "VSSQ4_D9") (pintype "passive"))
      (node (ref "IC57") (pin "E1") (pinfunction "VSS3_E1") (pintype "passive"))
      (node (ref "IC57") (pin "E9") (pinfunction "VSS4_E9") (pintype "passive"))
      (node (ref "IC57") (pin "G1") (pinfunction "VSS5_G1") (pintype "passive"))
      (node (ref "IC57") (pin "H9") (pinfunction "VSS6_H9") (pintype "passive"))
      (node (ref "IC57") (pin "K1") (pinfunction "VSS7_K1") (pintype "passive"))
      (node (ref "IC57") (pin "K9") (pinfunction "VSS8_K9") (pintype "passive"))
      (node (ref "IC57") (pin "N1") (pinfunction "VSS9_N1") (pintype "passive"))
      (node (ref "IC58") (pin "A2") (pinfunction "VSSQ1_A2") (pintype "passive"))
      (node (ref "IC58") (pin "A8") (pinfunction "VSSQ2_A8") (pintype "passive"))
      (node (ref "IC58") (pin "A9") (pinfunction "VSS1_A9") (pintype "passive"))
      (node (ref "IC58") (pin "C8") (pinfunction "VSS2_C8") (pintype "passive"))
      (node (ref "IC58") (pin "D1") (pinfunction "VSSQ3_D1") (pintype "passive"))
      (node (ref "IC58") (pin "D9") (pinfunction "VSSQ4_D9") (pintype "passive"))
      (node (ref "IC58") (pin "E1") (pinfunction "VSS3_E1") (pintype "passive"))
      (node (ref "IC58") (pin "E9") (pinfunction "VSS4_E9") (pintype "passive"))
      (node (ref "IC58") (pin "G1") (pinfunction "VSS5_G1") (pintype "passive"))
      (node (ref "IC58") (pin "H9") (pinfunction "VSS6_H9") (pintype "passive"))
      (node (ref "IC58") (pin "K1") (pinfunction "VSS7_K1") (pintype "passive"))
      (node (ref "IC58") (pin "K9") (pinfunction "VSS8_K9") (pintype "passive"))
      (node (ref "IC58") (pin "N1") (pinfunction "VSS9_N1") (pintype "passive"))
      (node (ref "IC59") (pin "1") (pinfunction "NC_1") (pintype "passive"))
      (node (ref "IC59") (pin "3") (pinfunction "A2_3") (pintype "passive"))
      (node (ref "IC59") (pin "4") (pinfunction "GND_4") (pintype "passive"))
      (node (ref "R444") (pin "1") (pinfunction "1_1") (pintype "passive"))
      (node (ref "R445") (pin "1") (pinfunction "1_1") (pintype "passive"))
      (node (ref "R446") (pin "1") (pinfunction "1_1") (pintype "passive"))
      (node (ref "R447") (pin "1") (pinfunction "1_1") (pintype "passive"))
      (node (ref "R449") (pin "1") (pinfunction "1_1") (pintype "passive"))
      (node (ref "R452") (pin "1") (pinfunction "1_1") (pintype "passive"))
      (node (ref "R454") (pin "2") (pinfunction "2_2") (pintype "passive"))
      (node (ref "R457") (pin "1") (pinfunction "1_1") (pintype "passive"))
      (node (ref "R458") (pin "1") (pinfunction "1_1") (pintype "passive"))
      (node (ref "R459") (pin "1") (pinfunction "1_1") (pintype "passive"))
      (node (ref "R460") (pin "1") (pinfunction "1_1") (pintype "passive"))
      (node (ref "R461") (pin "1") (pinfunction "1_1") (pintype "passive"))
    )
    (net (code "101") (name "Net-(C724-Pad1)") (class "Default")
      (node (ref "C724") (pin "1") (pinfunction "1_1") (pintype "passive"))
      (node (ref "R442") (pin "2") (pinfunction "2_2") (pintype "passive"))
      (node (ref "R443") (pin "2") (pinfunction "2_2") (pintype "passive"))
    )
    (net (code "102") (name "Net-(C741-Pad1)") (class "Default")
      (node (ref "C741") (pin "1") (pinfunction "1_1") (pintype "passive"))
      (node (ref "R455") (pin "2") (pinfunction "2_2") (pintype "passive"))
      (node (ref "R456") (pin "2") (pinfunction "2_2") (pintype "passive"))
    )
    (net (code "103") (name "Net-(IC30A-D1_MAPAR_ERR#)") (class "Default")
      (node (ref "IC30") (pin "AD24") (pinfunction "D1_MAPAR_ERR#_AD24") (pintype "passive"))
      (node (ref "R450") (pin "1") (pinfunction "1_1") (pintype "passive"))
      (node (ref "R451") (pin "1") (pinfunction "1_1") (pintype "passive"))
    )
    (net (code "104") (name "Net-(IC30A-D1_MDIC0)") (class "Default")
      (node (ref "IC30") (pin "V25") (pinfunction "D1_MDIC0_V25") (pintype "passive"))
      (node (ref "R449") (pin "2") (pinfunction "2_2") (pintype "passive"))
    )
    (net (code "105") (name "Net-(IC30A-D1_MDIC1)") (class "Default")
      (node (ref "IC30") (pin "Y25") (pinfunction "D1_MDIC1_Y25") (pintype "passive"))
      (node (ref "R448") (pin "2") (pinfunction "2_2") (pintype "passive"))
    )
    (net (code "106") (name "Net-(IC59-WP)") (class "Default")
      (node (ref "IC59") (pin "7") (pinfunction "WP_7") (pintype "passive"))
      (node (ref "R459") (pin "2") (pinfunction "2_2") (pintype "passive"))
    )
    (net (code "107") (name "unconnected-(IC30A-D1_MA00-PadAC25)") (class "Default")
      (node (ref "IC30") (pin "AC25") (pinfunction "D1_MA00_AC25") (pintype "passive"))
    )
    (net (code "108") (name "unconnected-(IC30A-D1_MBA2-PadAE23)") (class "Default")
      (node (ref "IC30") (pin "AE23") (pinfunction "D1_MBA2_AE23") (pintype "passive"))
    )
    (net (code "109") (name "unconnected-(IC30A-D1_MCS2#-PadAB20)") (class "Default")
      (node (ref "IC30") (pin "AB20") (pinfunction "D1_MCS2#_AB20") (pintype "passive+no_connect"))
    )
    (net (code "110") (name "unconnected-(IC30A-D1_MCS3#-PadAA22)") (class "Default")
      (node (ref "IC30") (pin "AA22") (pinfunction "D1_MCS3#_AA22") (pintype "passive"))
    )
    (net (code "111") (name "unconnected-(IC30A-D1_MDM0-PadL25)") (class "Default")
      (node (ref "IC30") (pin "L25") (pinfunction "D1_MDM0_L25") (pintype "passive"))
    )
    (net (code "112") (name "unconnected-(IC30A-D1_MDM1-PadL21)") (class "Default")
      (node (ref "IC30") (pin "L21") (pinfunction "D1_MDM1_L21") (pintype "passive"))
    )
    (net (code "113") (name "unconnected-(IC30A-D1_MDM2-PadE23)") (class "Default")
      (node (ref "IC30") (pin "E23") (pinfunction "D1_MDM2_E23") (pintype "passive"))
    )
    (net (code "114") (name "unconnected-(IC30A-D1_MDM4-PadG23)") (class "Default")
      (node (ref "IC30") (pin "G23") (pinfunction "D1_MDM4_G23") (pintype "passive"))
    )
    (net (code "115") (name "unconnected-(IC30A-D1_MDQS0#-PadM25)") (class "Default")
      (node (ref "IC30") (pin "M25") (pinfunction "D1_MDQS0#_M25") (pintype "passive"))
    )
    (net (code "116") (name "unconnected-(IC30A-D1_MDQS2-PadE25)") (class "Default")
      (node (ref "IC30") (pin "E25") (pinfunction "D1_MDQS2_E25") (pintype "passive"))
    )
    (net (code "117") (name "unconnected-(IC30A-D1_MVREF-PadH19)") (class "Default")
      (node (ref "IC30") (pin "H19") (pinfunction "D1_MVREF_H19") (pintype "passive"))
    )
    (net (code "118") (name "unconnected-(IC30A-D1_MWE-PadY21)") (class "Default")
      (node (ref "IC30") (pin "Y21") (pinfunction "D1_MWE_Y21") (pintype "passive"))
    )
    (net (code "119") (name "unconnected-(IC30A-D1_TPA-PadD1)") (class "Default")
      (node (ref "IC30") (pin "D1") (pinfunction "D1_TPA_D1") (pintype "passive"))
    )
    (net (code "120") (name "unconnected-(IC51-A17{slash}NC-PadN7)") (class "Default")
      (node (ref "IC51") (pin "N7") (pinfunction "A17/NC_N7") (pintype "passive+no_connect"))
    )
    (net (code "121") (name "unconnected-(IC51-NF{slash}TDQS_C-PadA3)") (class "Default")
      (node (ref "IC51") (pin "A3") (pinfunction "NF/TDQS_C_A3") (pintype "passive+no_connect"))
    )
    (net (code "122") (name "unconnected-(IC52-A17{slash}NC-PadN7)") (class "Default")
      (node (ref "IC52") (pin "N7") (pinfunction "A17/NC_N7") (pintype "passive+no_connect"))
    )
    (net (code "123") (name "unconnected-(IC52-NF{slash}TDQS_C-PadA3)") (class "Default")
      (node (ref "IC52") (pin "A3") (pinfunction "NF/TDQS_C_A3") (pintype "passive+no_connect"))
    )
    (net (code "124") (name "unconnected-(IC53-A17{slash}NC-PadN7)") (class "Default")
      (node (ref "IC53") (pin "N7") (pinfunction "A17/NC_N7") (pintype "passive+no_connect"))
    )
    (net (code "125") (name "unconnected-(IC53-NF{slash}TDQS_C-PadA3)") (class "Default")
      (node (ref "IC53") (pin "A3") (pinfunction "NF/TDQS_C_A3") (pintype "passive+no_connect"))
    )
    (net (code "126") (name "unconnected-(IC54-A17{slash}NC-PadN7)") (class "Default")
      (node (ref "IC54") (pin "N7") (pinfunction "A17/NC_N7") (pintype "passive+no_connect"))
    )
    (net (code "127") (name "unconnected-(IC54-NF{slash}TDQS_C-PadA3)") (class "Default")
      (node (ref "IC54") (pin "A3") (pinfunction "NF/TDQS_C_A3") (pintype "passive+no_connect"))
    )
    (net (code "128") (name "unconnected-(IC55-A17{slash}NC-PadN7)") (class "Default")
      (node (ref "IC55") (pin "N7") (pinfunction "A17/NC_N7") (pintype "passive+no_connect"))
    )
    (net (code "129") (name "unconnected-(IC55-NF{slash}TDQS_C-PadA3)") (class "Default")
      (node (ref "IC55") (pin "A3") (pinfunction "NF/TDQS_C_A3") (pintype "passive+no_connect"))
    )
    (net (code "130") (name "unconnected-(IC56-A17{slash}NC-PadN7)") (class "Default")
      (node (ref "IC56") (pin "N7") (pinfunction "A17/NC_N7") (pintype "passive+no_connect"))
    )
    (net (code "131") (name "unconnected-(IC56-NF{slash}TDQS_C-PadA3)") (class "Default")
      (node (ref "IC56") (pin "A3") (pinfunction "NF/TDQS_C_A3") (pintype "passive+no_connect"))
    )
    (net (code "132") (name "unconnected-(IC57-A17{slash}NC-PadN7)") (class "Default")
      (node (ref "IC57") (pin "N7") (pinfunction "A17/NC_N7") (pintype "passive+no_connect"))
    )
    (net (code "133") (name "unconnected-(IC57-NF{slash}TDQS_C-PadA3)") (class "Default")
      (node (ref "IC57") (pin "A3") (pinfunction "NF/TDQS_C_A3") (pintype "passive+no_connect"))
    )
    (net (code "134") (name "unconnected-(IC58-A17{slash}NC-PadN7)") (class "Default")
      (node (ref "IC58") (pin "N7") (pinfunction "A17/NC_N7") (pintype "passive+no_connect"))
    )
    (net (code "135") (name "unconnected-(IC58-NF{slash}TDQS_C-PadA3)") (class "Default")
      (node (ref "IC58") (pin "A3") (pinfunction "NF/TDQS_C_A3") (pintype "passive+no_connect"))
    )
    (net (code "136") (name "unconnected-(R452-Pad2)") (class "Default")
      (node (ref "R452") (pin "2") (pinfunction "2_2") (pintype "passive"))
    )
  )
)
